# Cubesat_Potencia-rev1.net
KiCad netlist of a schematic drawn in EAGLE
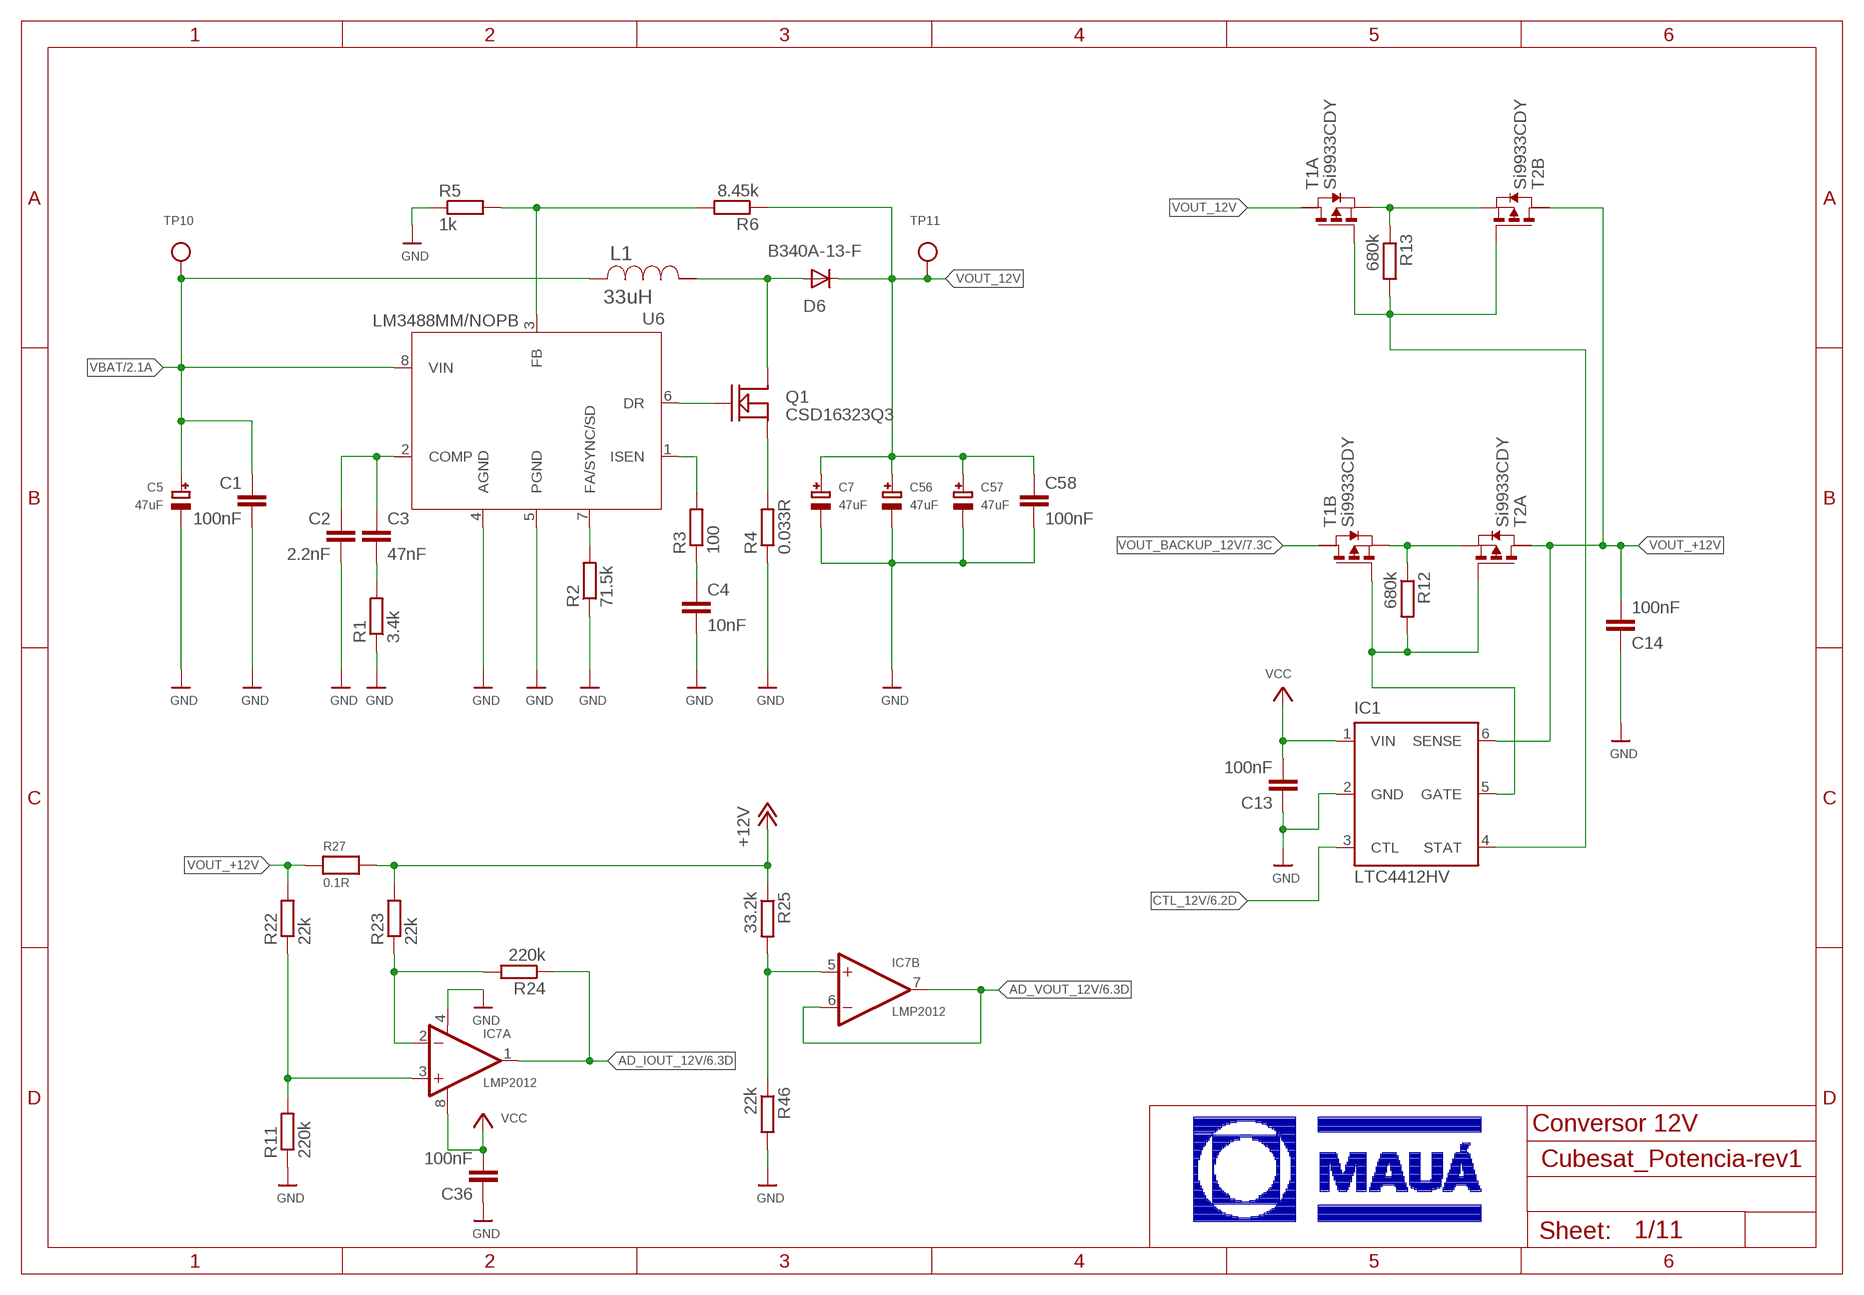
[diagram p0: schematic, sheet 1]
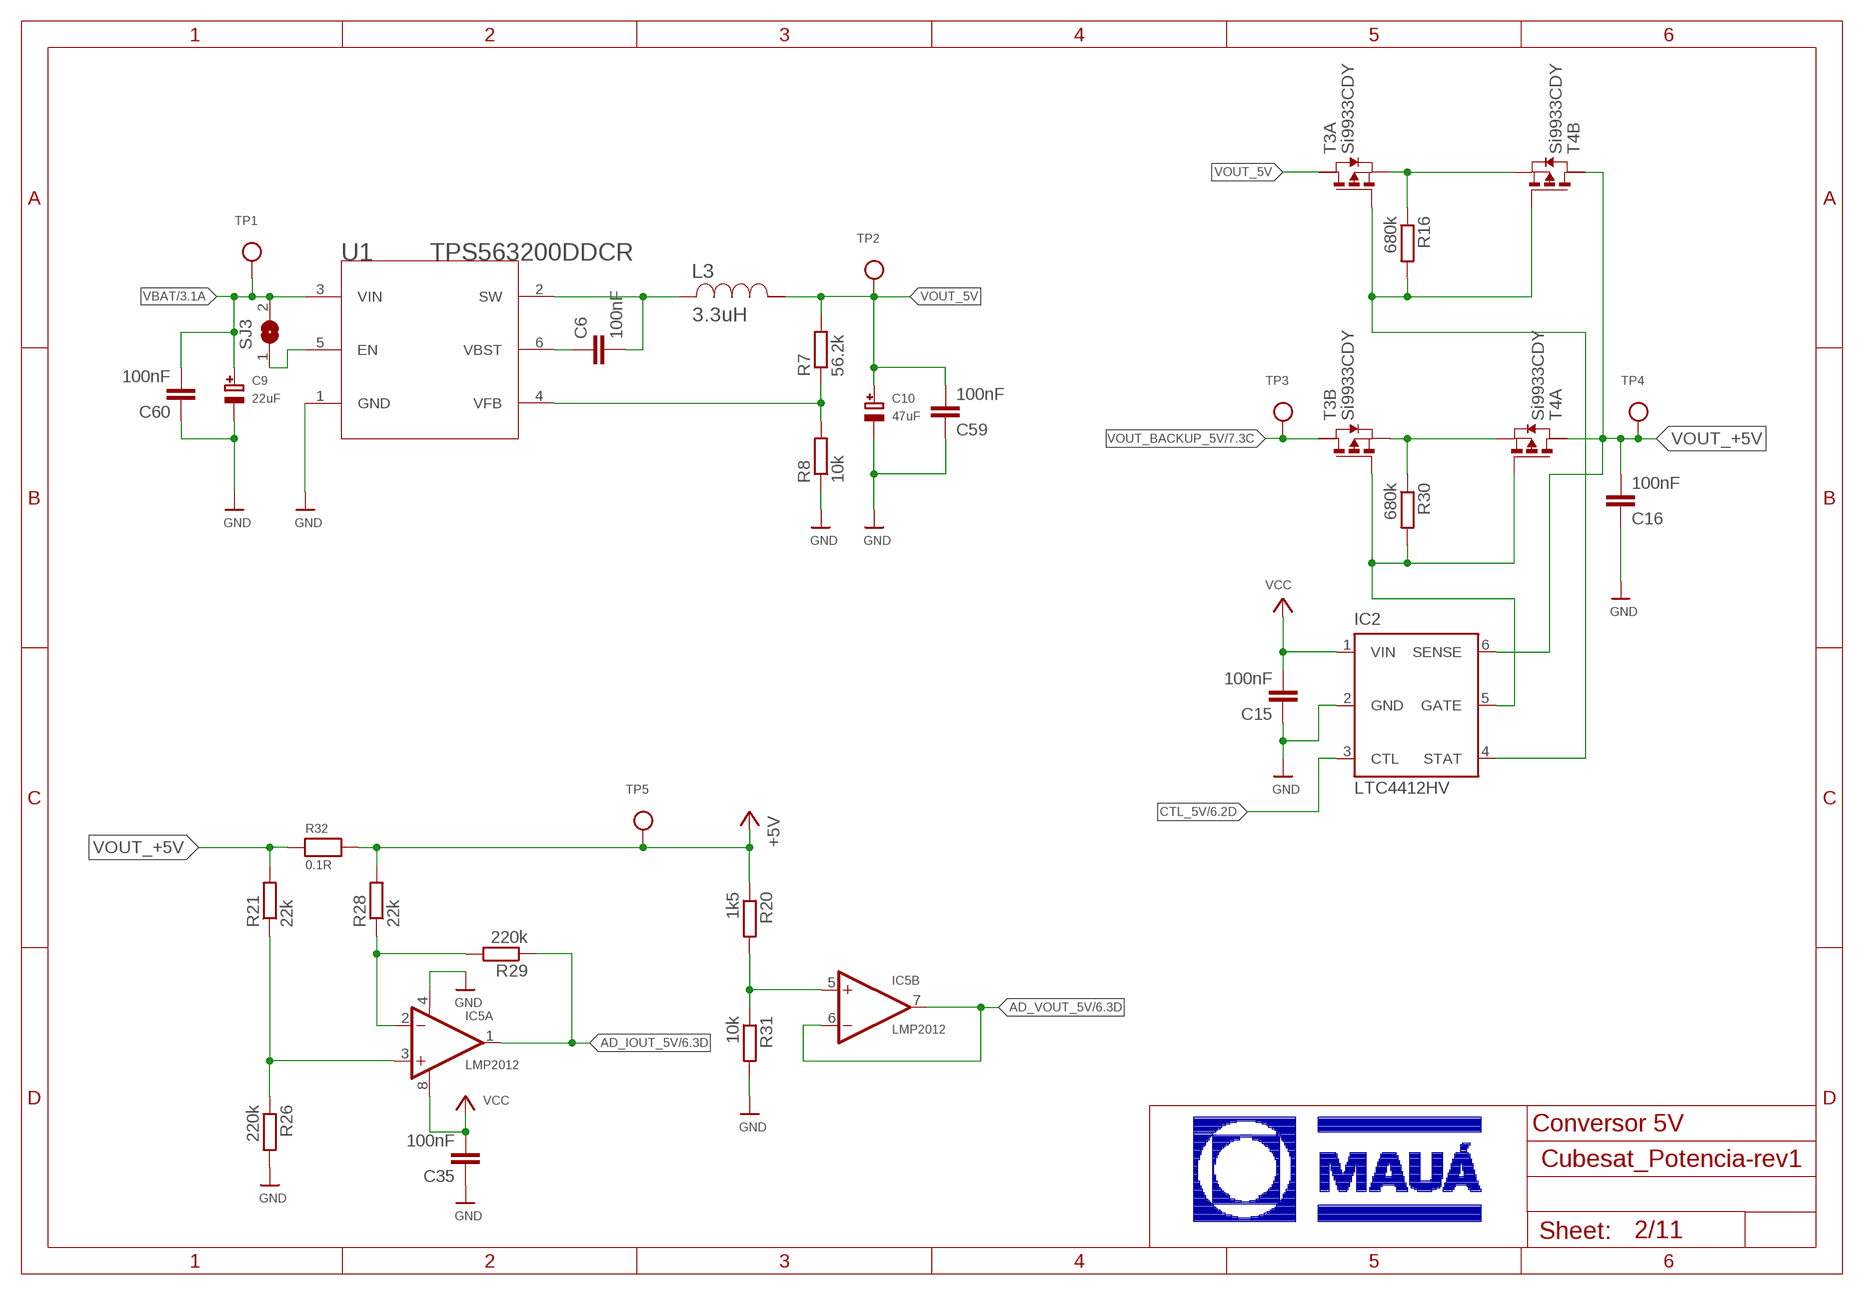
[diagram p1: schematic, sheet 2]
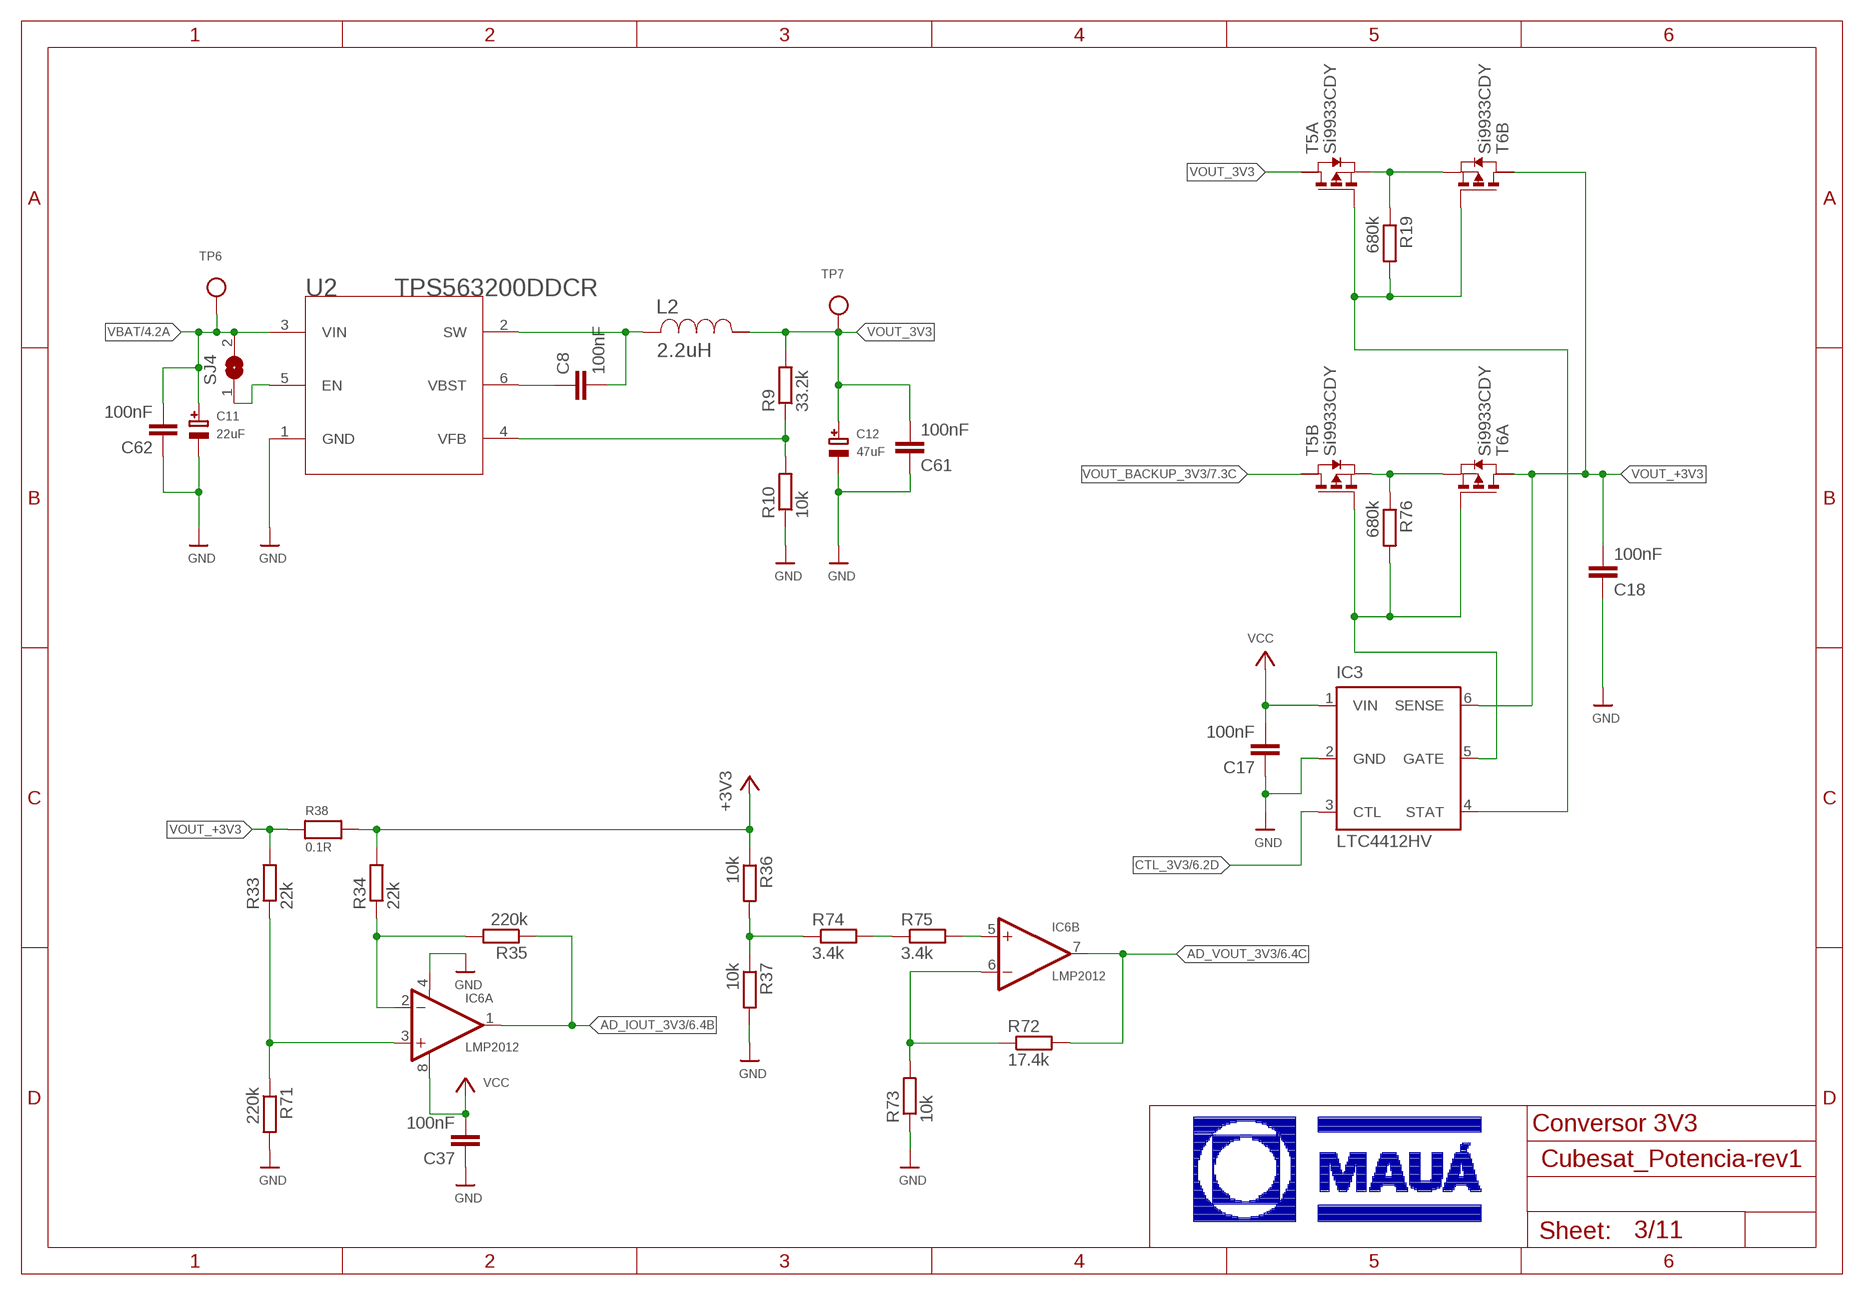
[diagram p2: schematic, sheet 3]
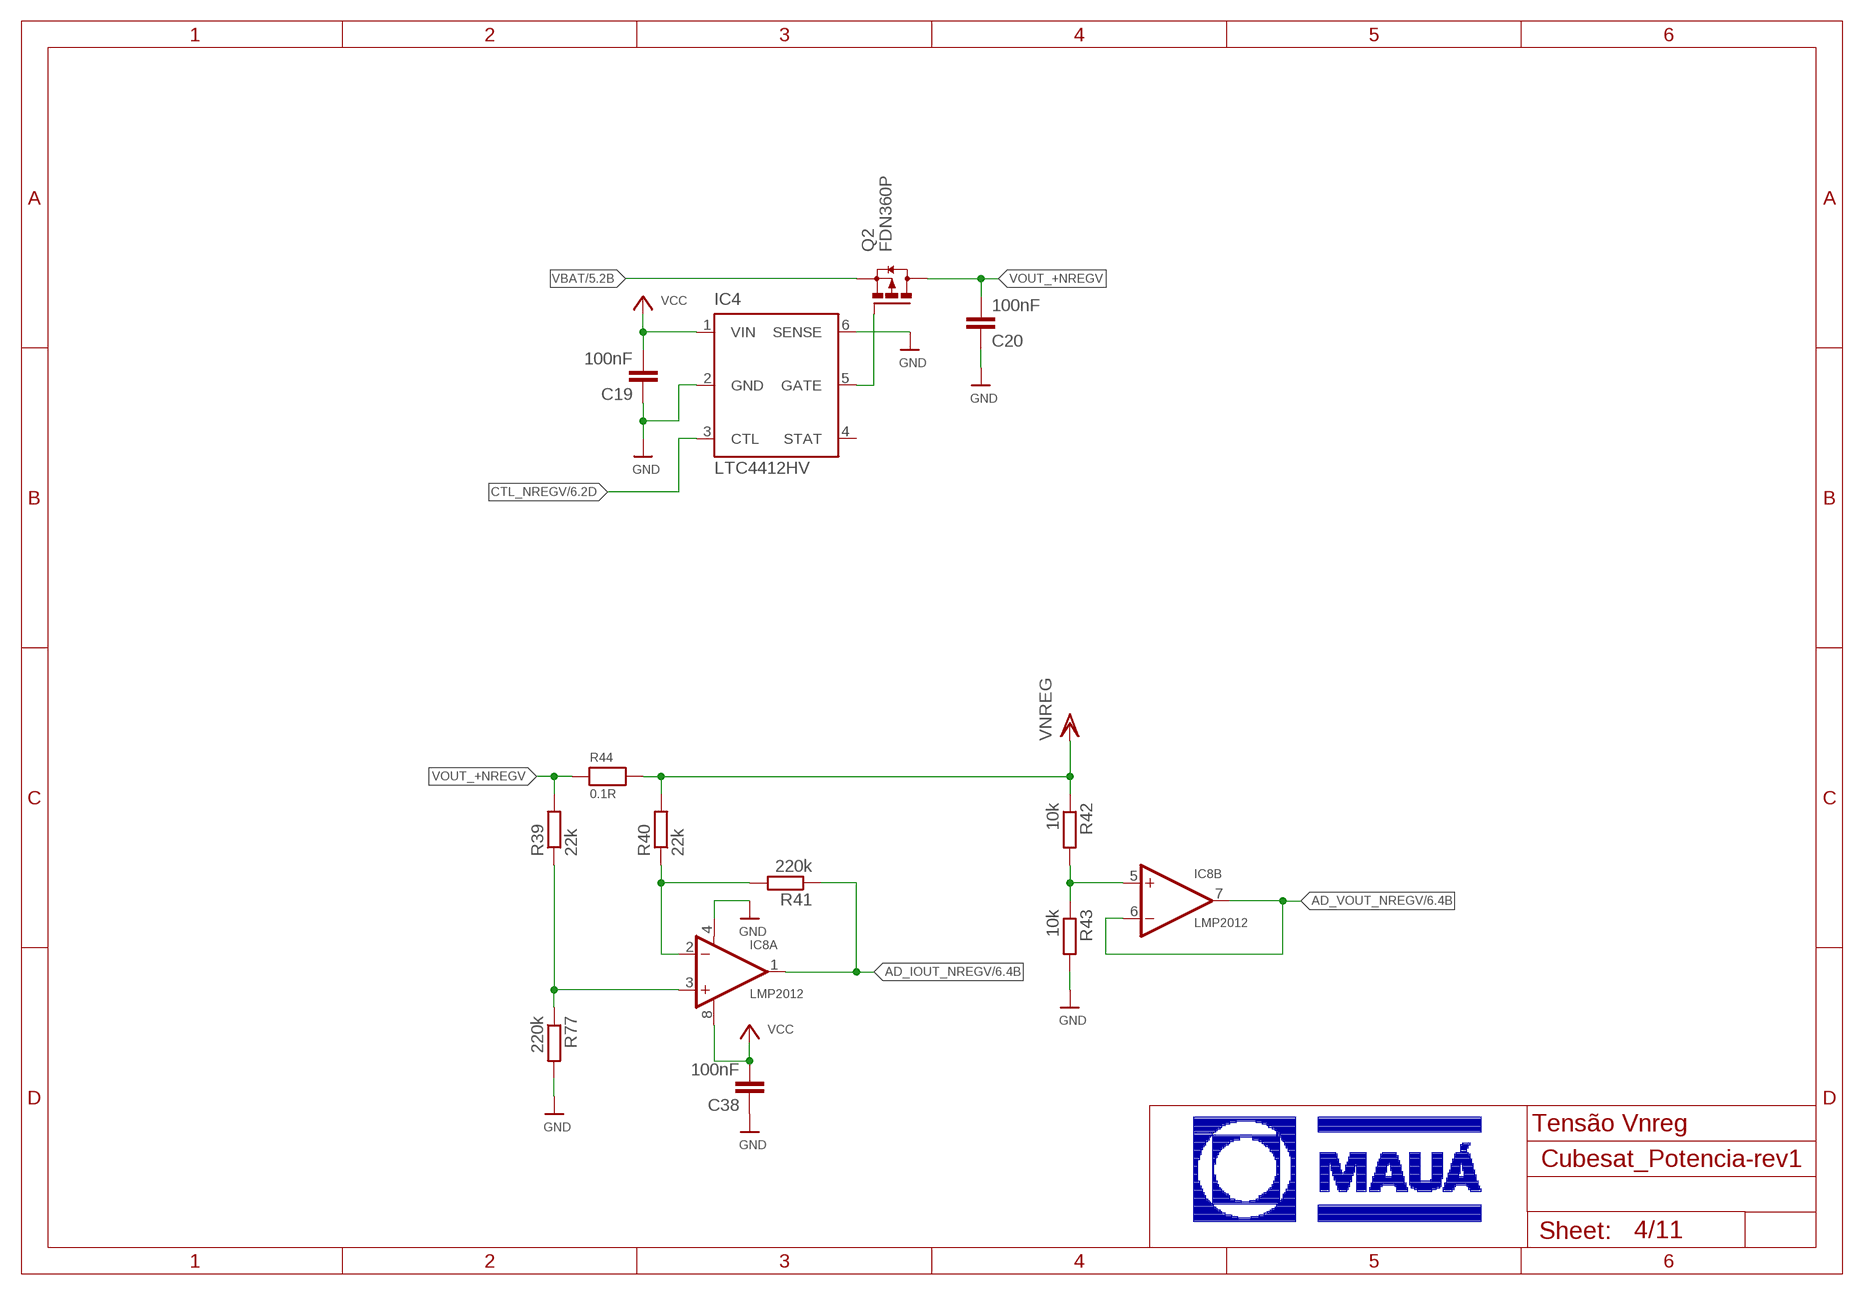
[diagram p3: schematic, sheet 4]
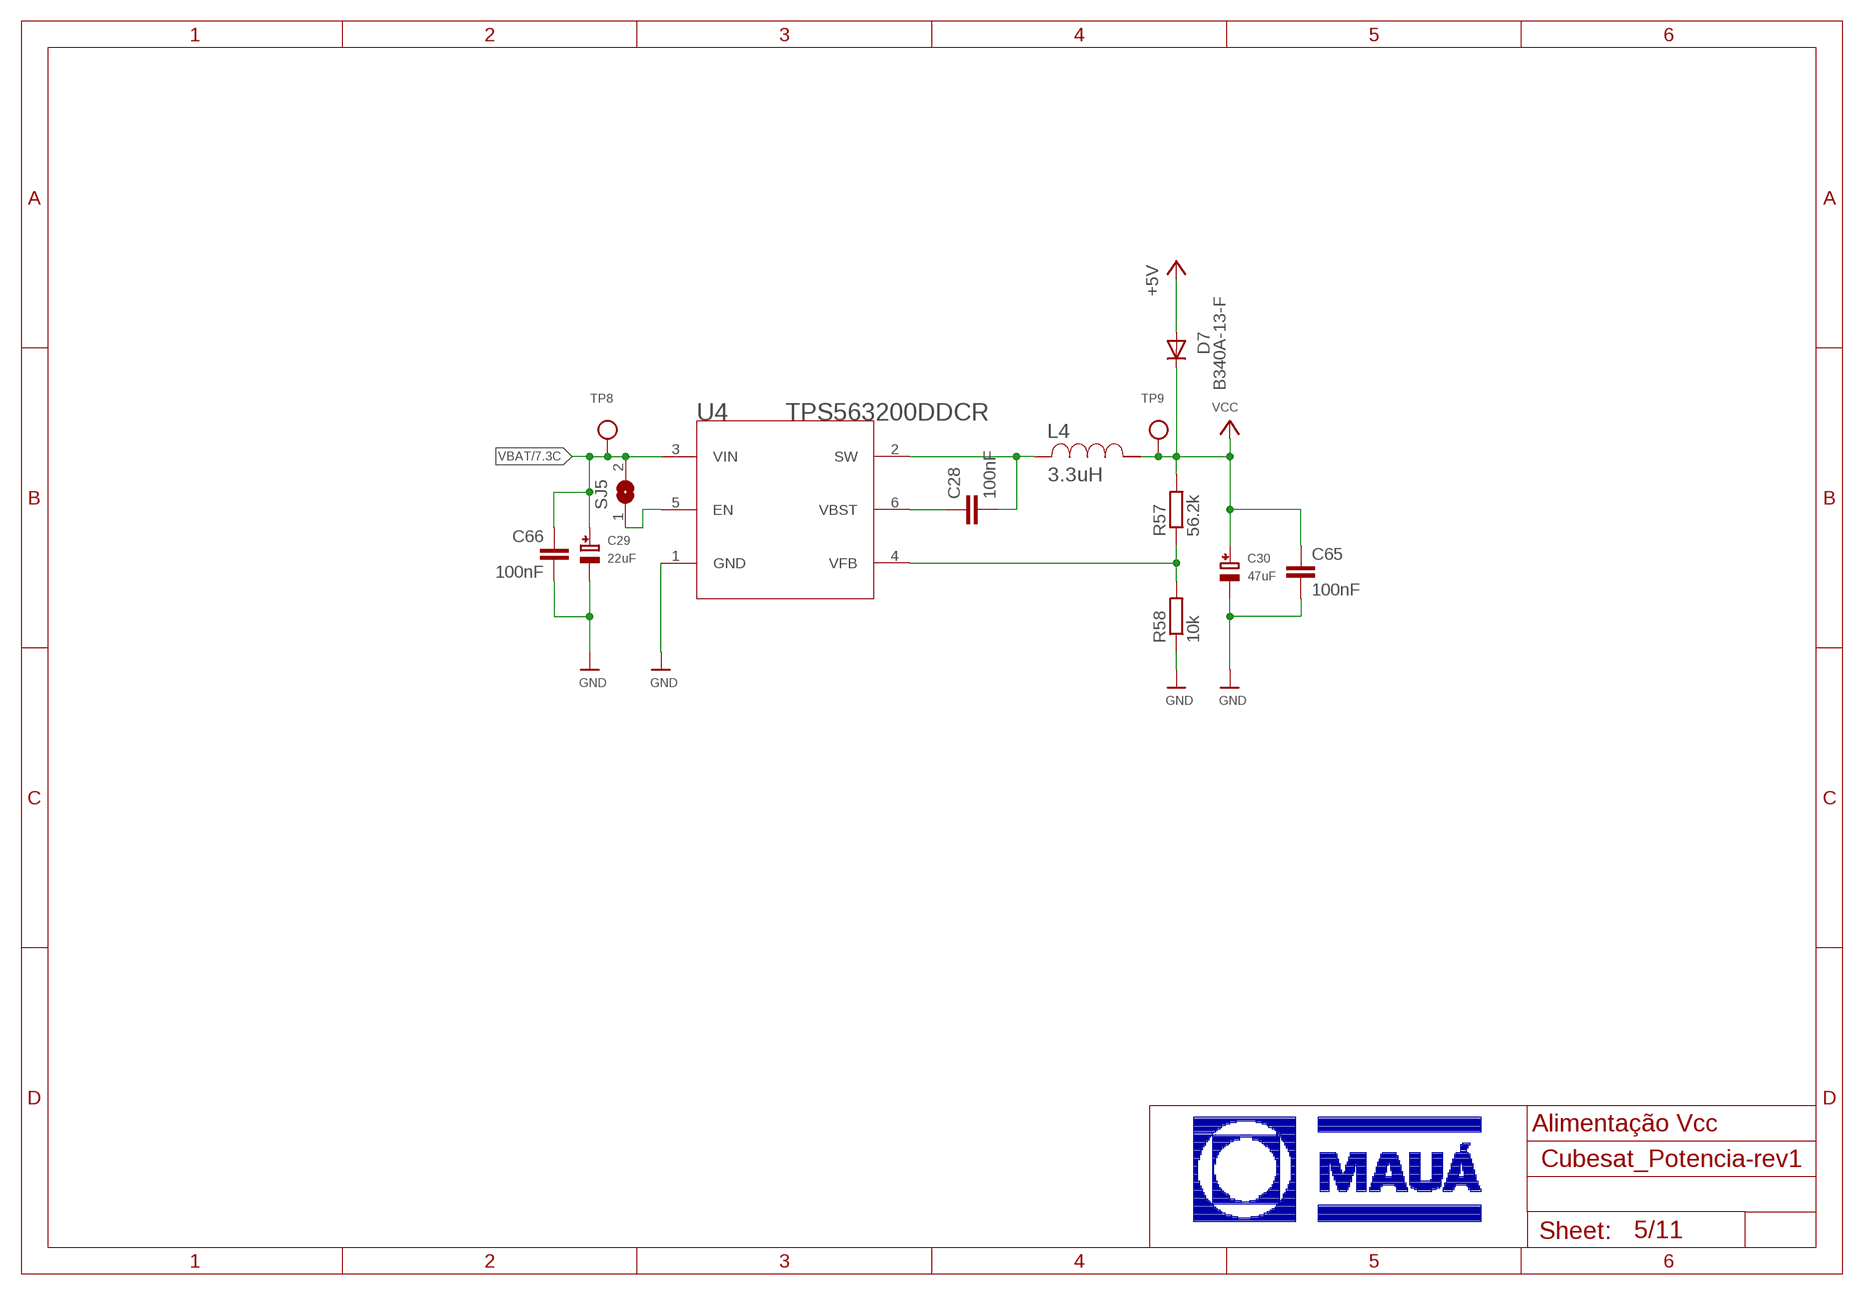
[diagram p4: schematic, sheet 5]
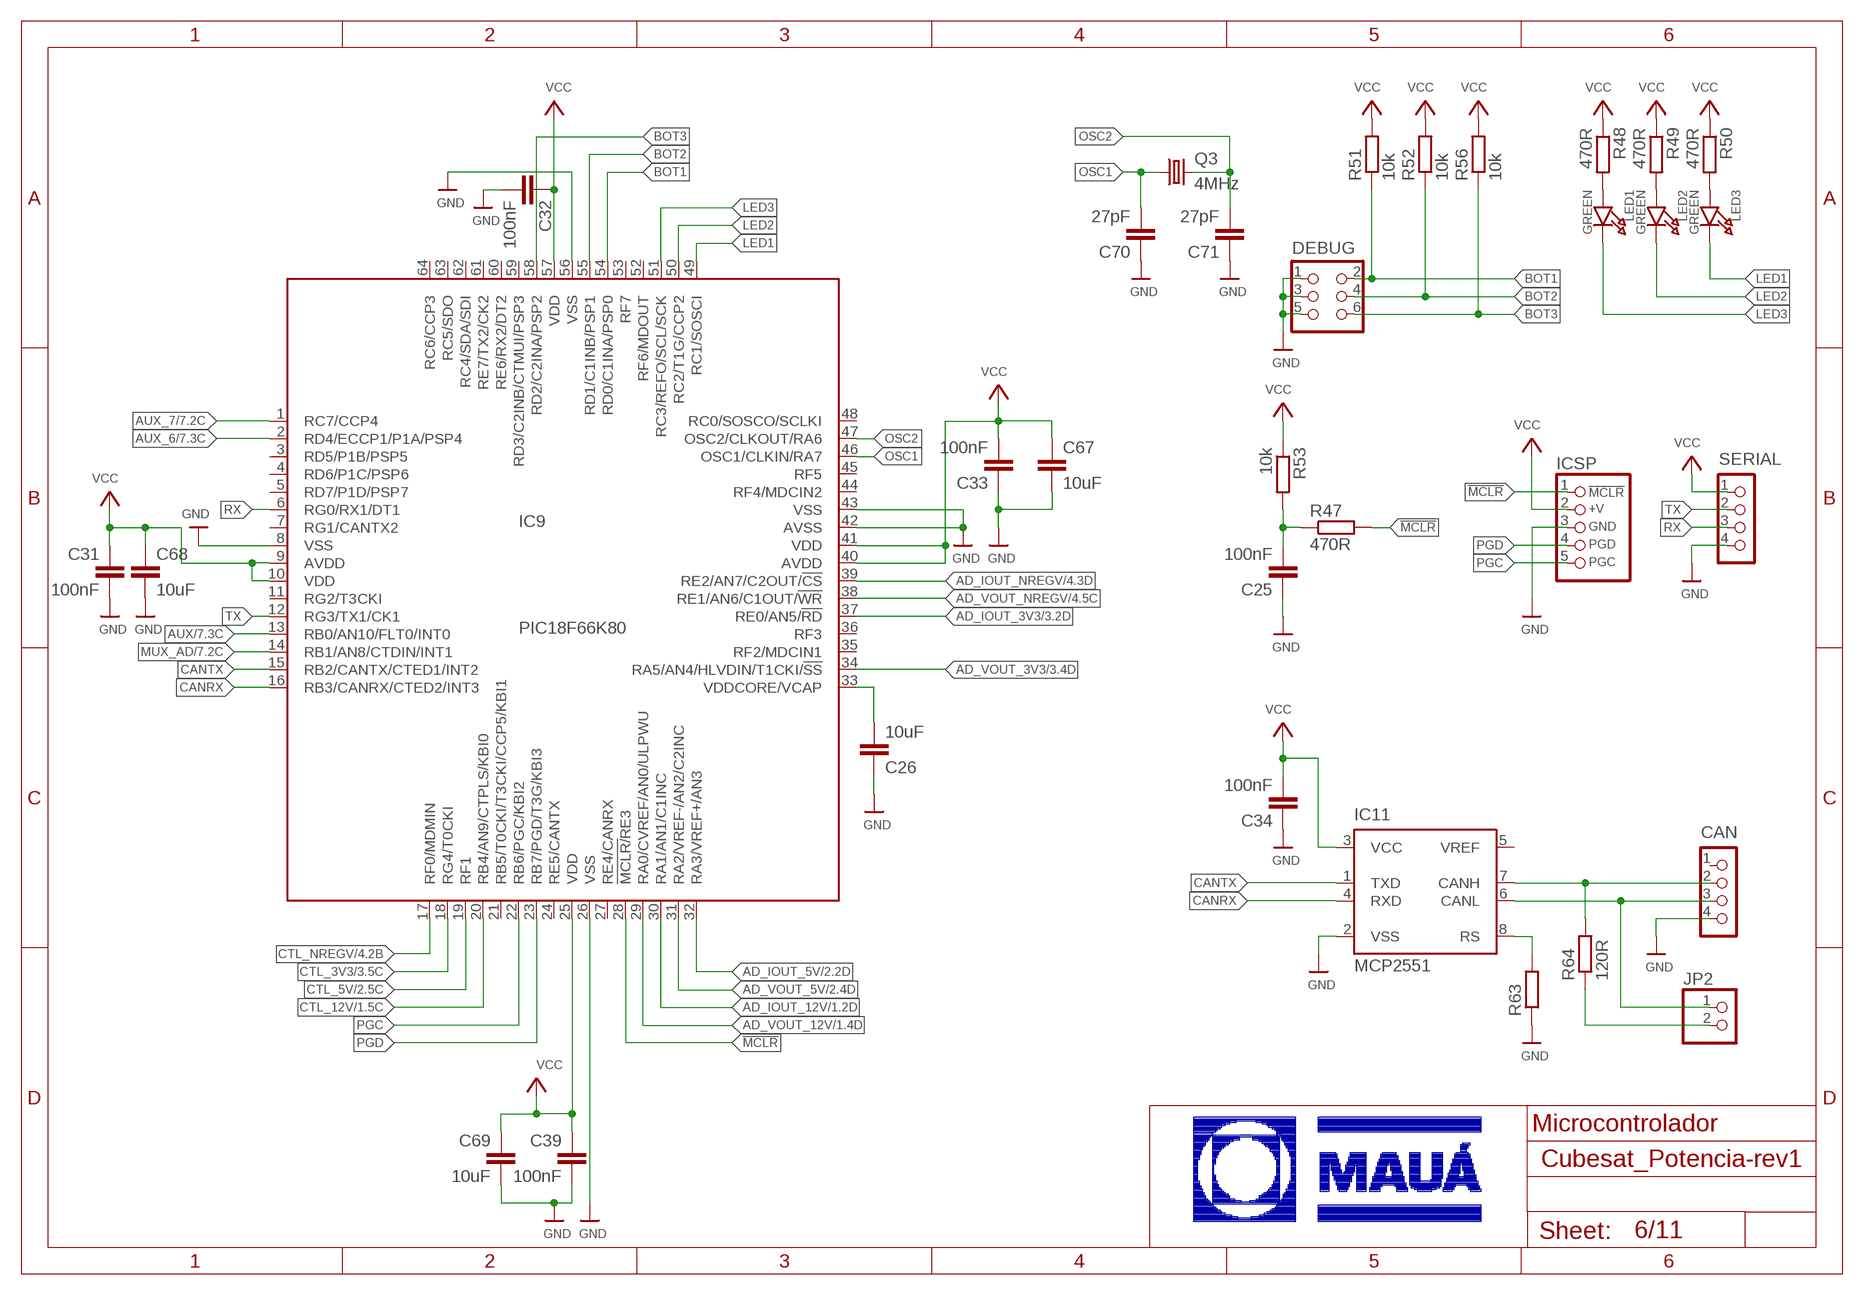
[diagram p5: schematic, sheet 6]
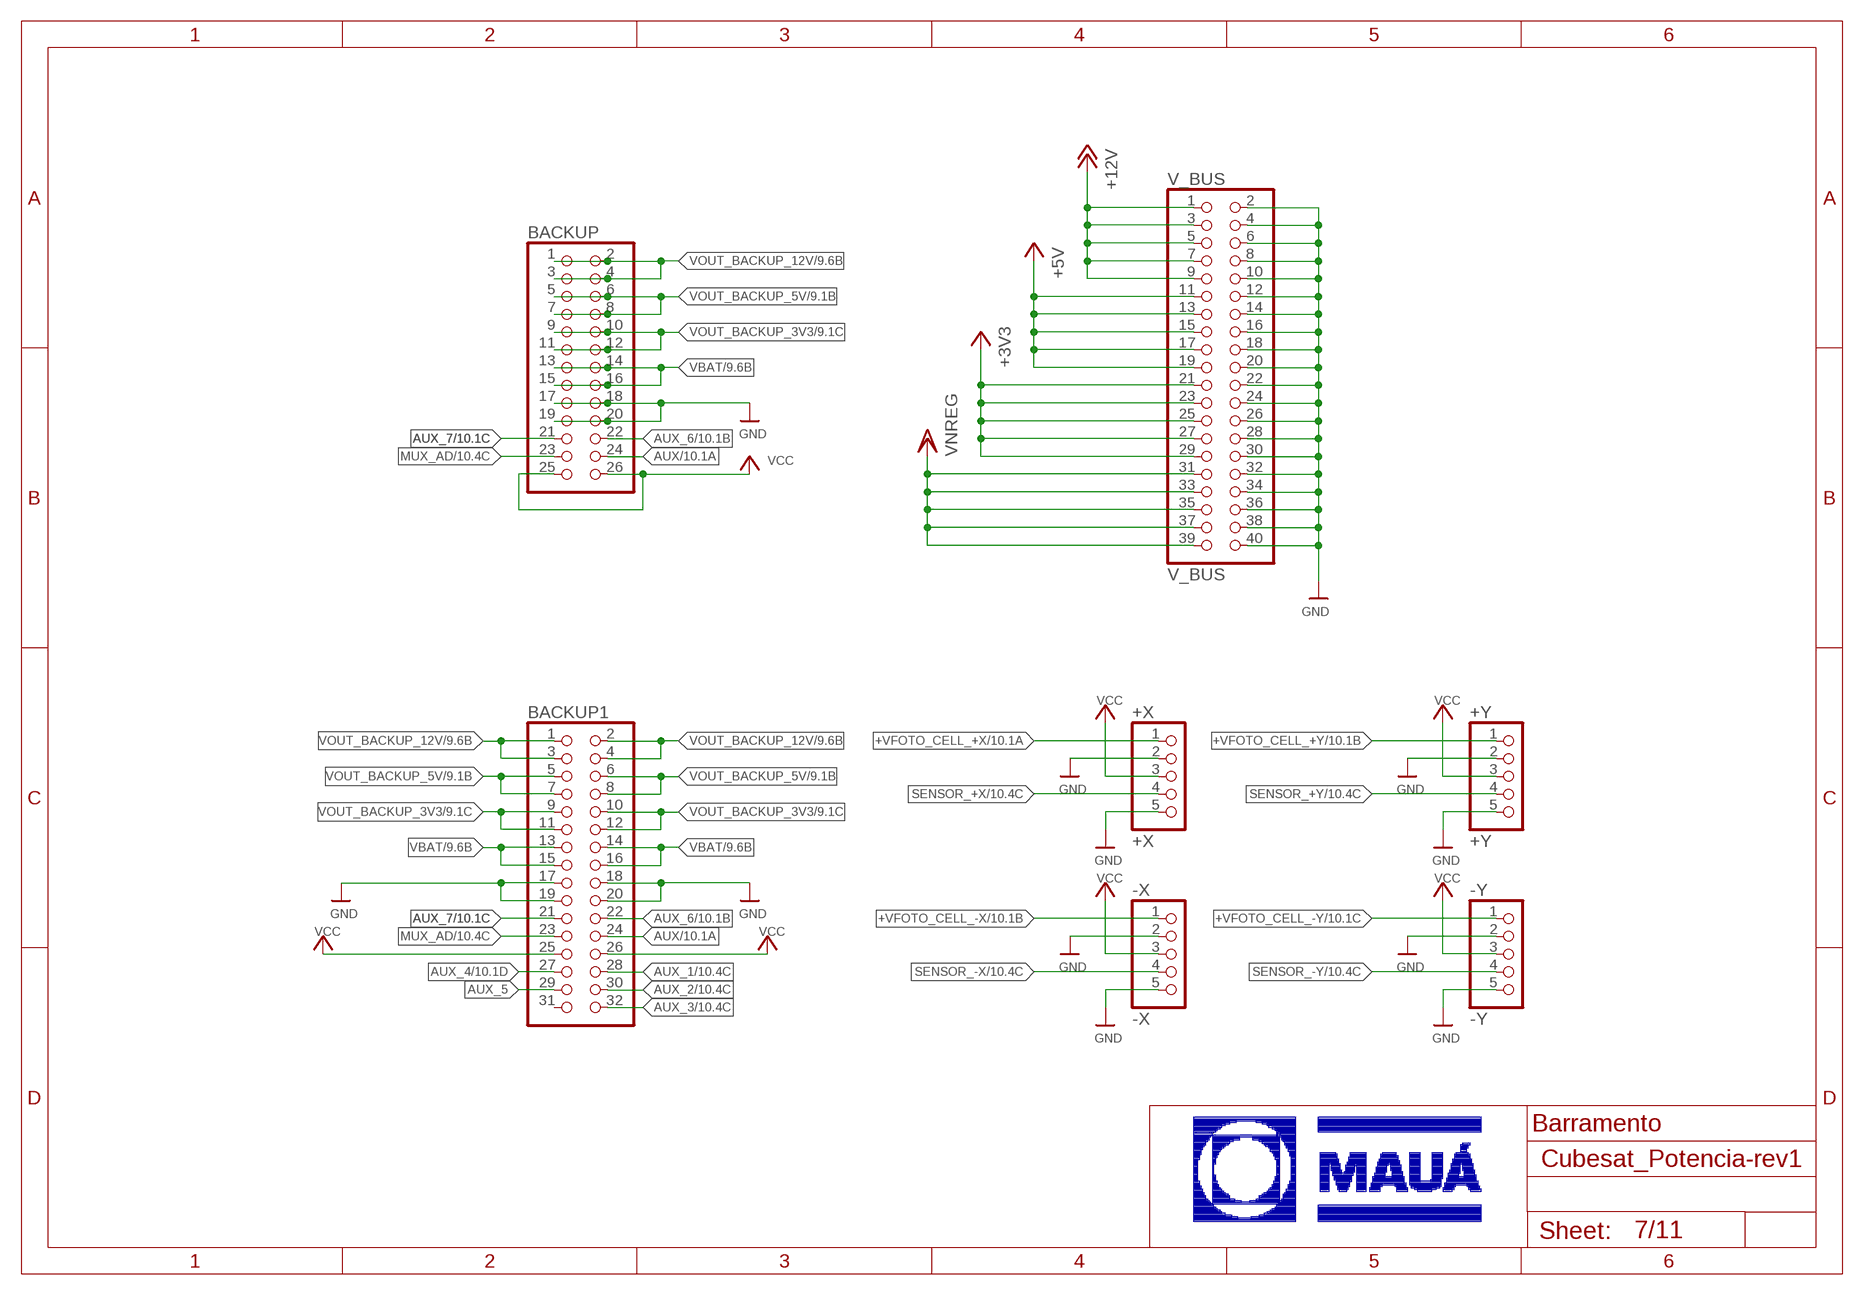
[diagram p6: schematic, sheet 7]
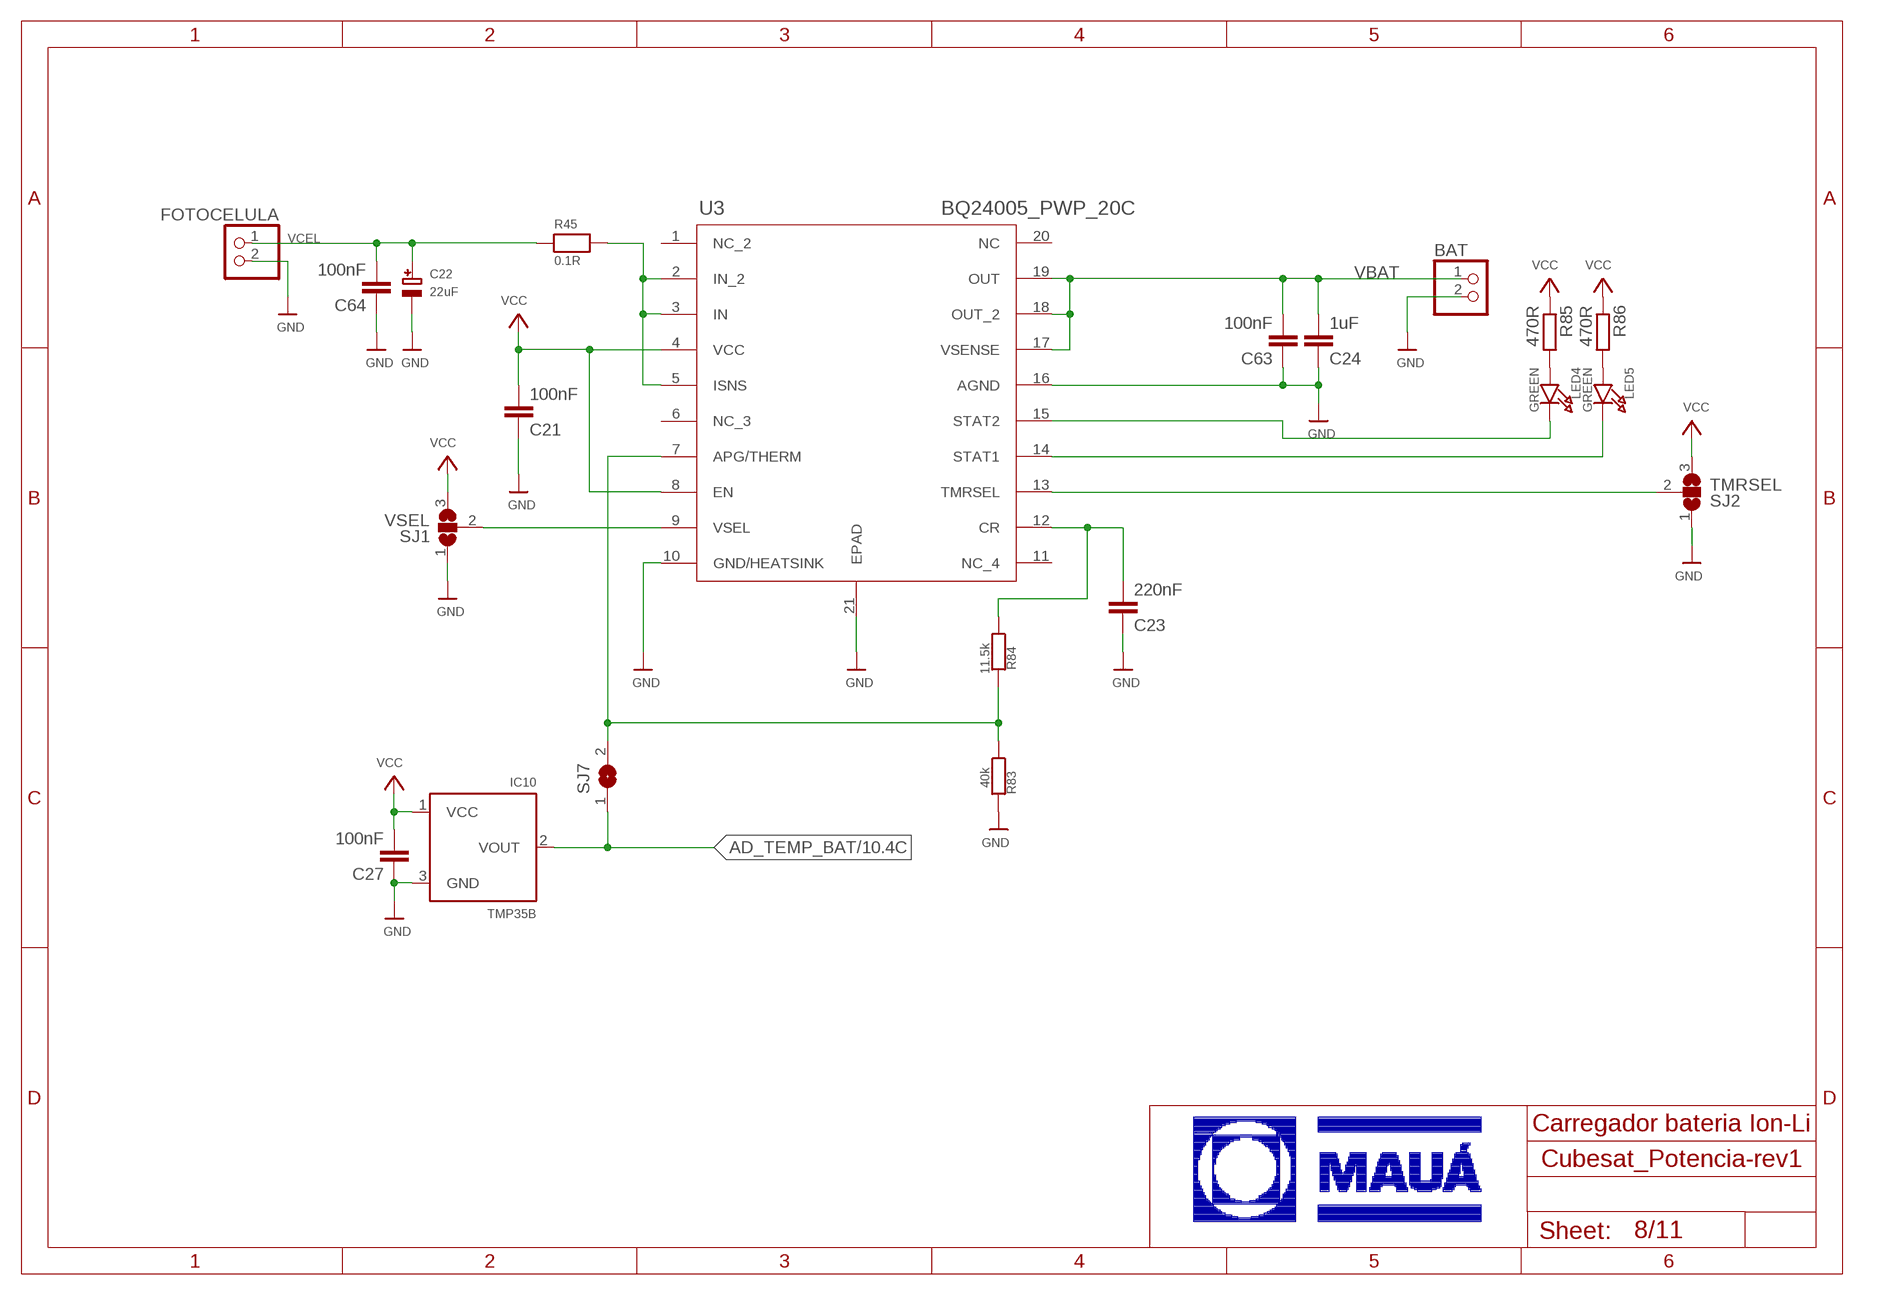
[diagram p7: schematic, sheet 8]
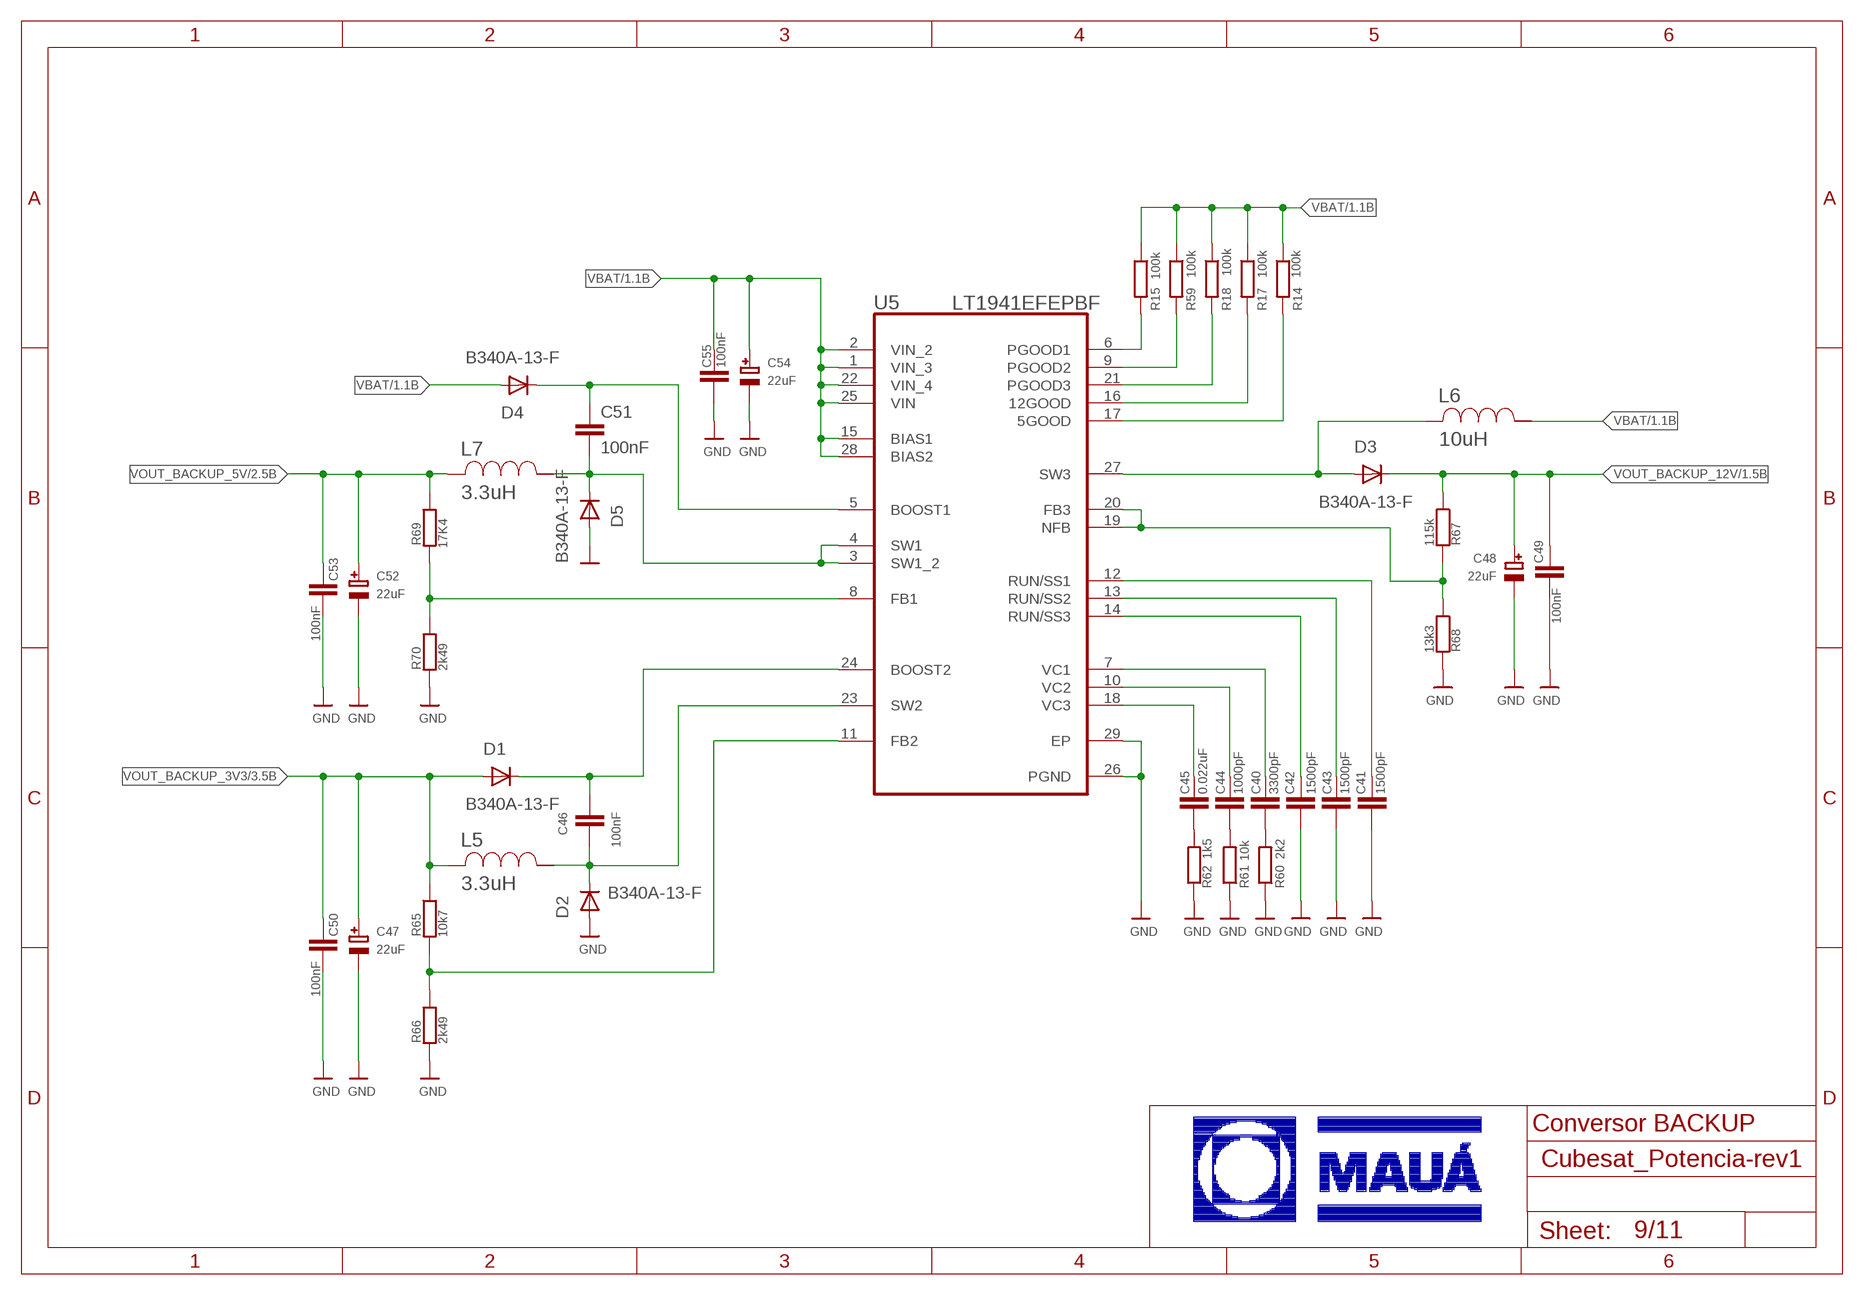
[diagram p8: schematic, sheet 9]
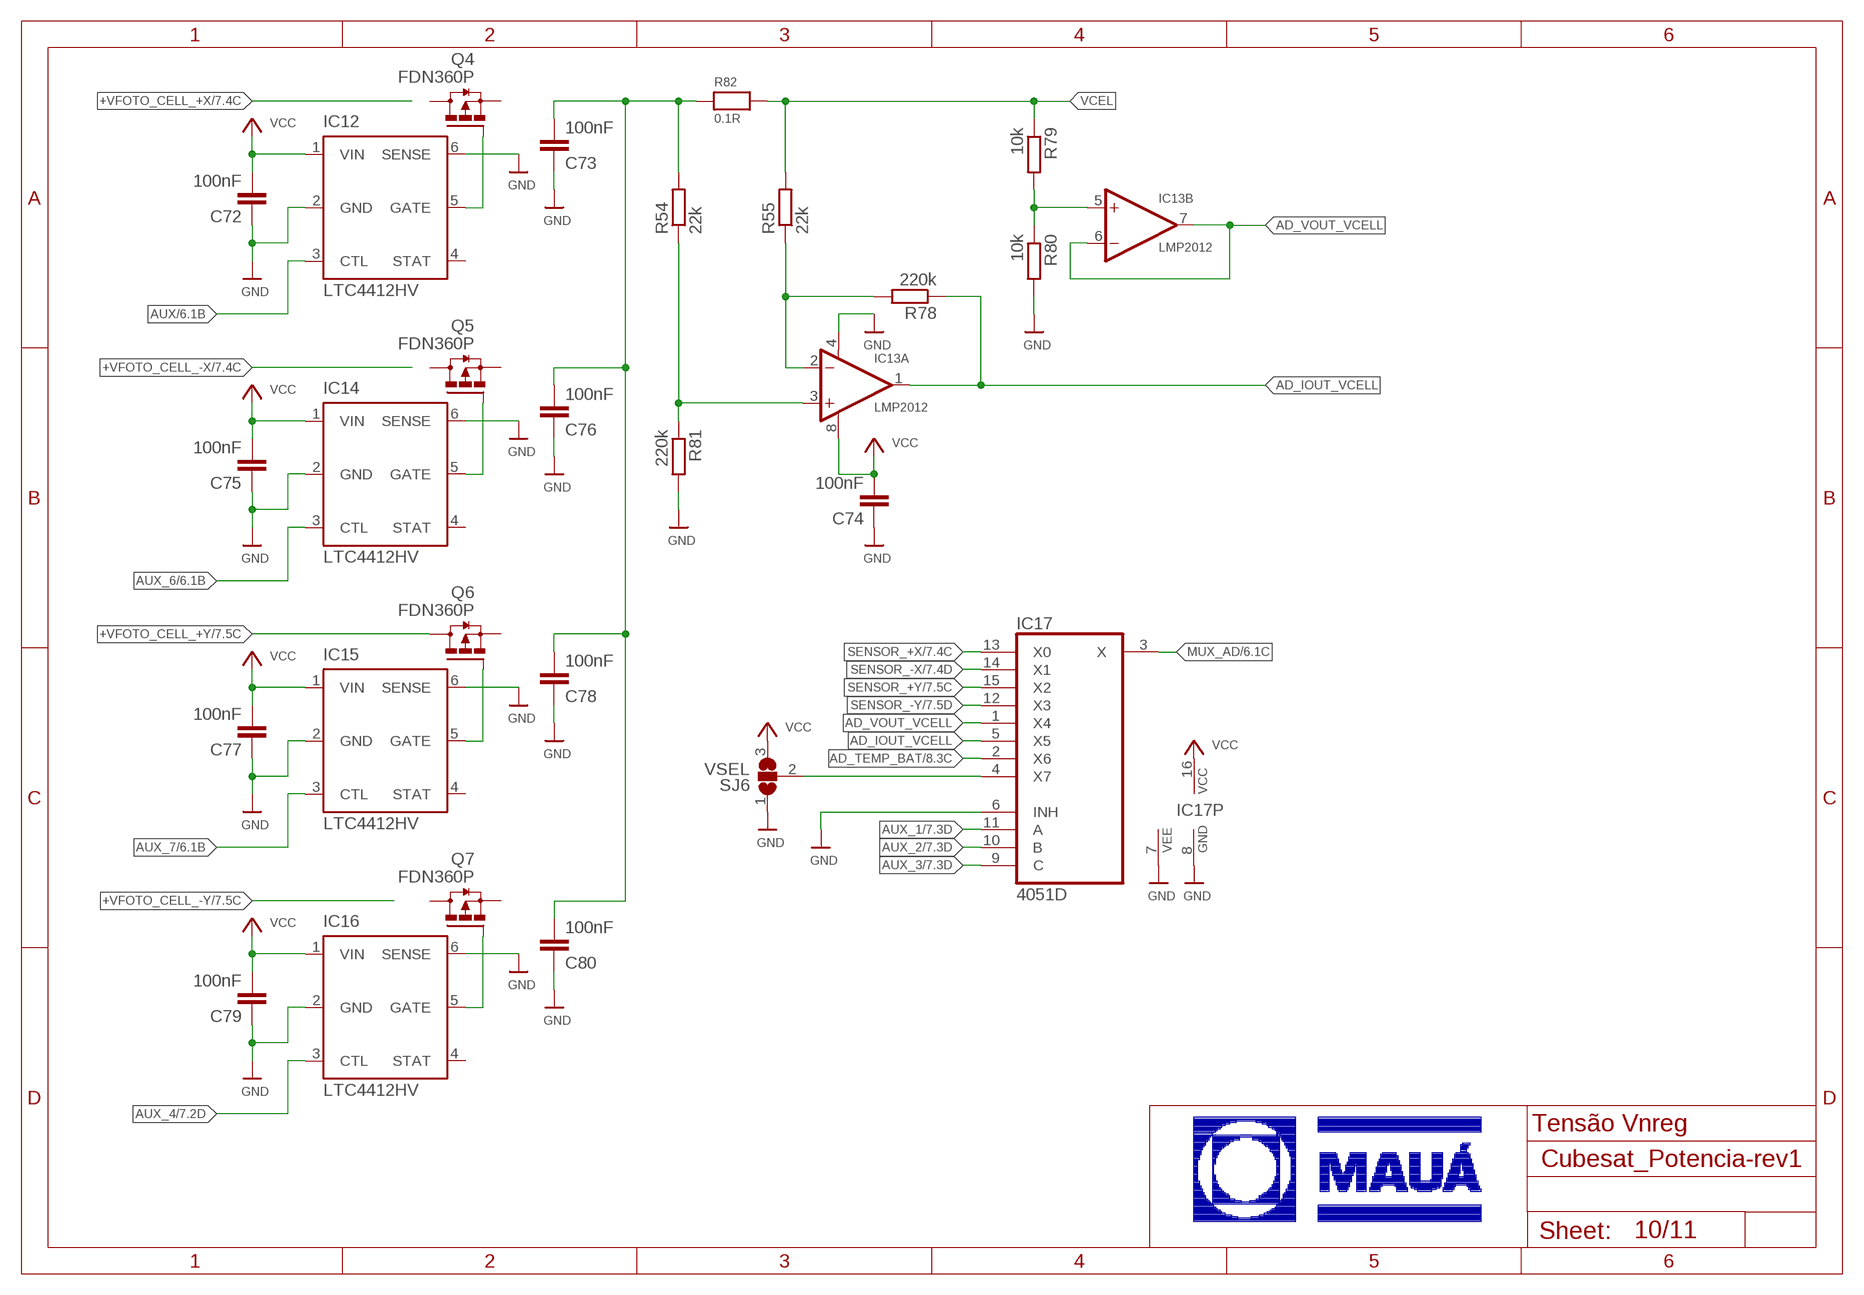
[diagram p9: schematic, sheet 10]
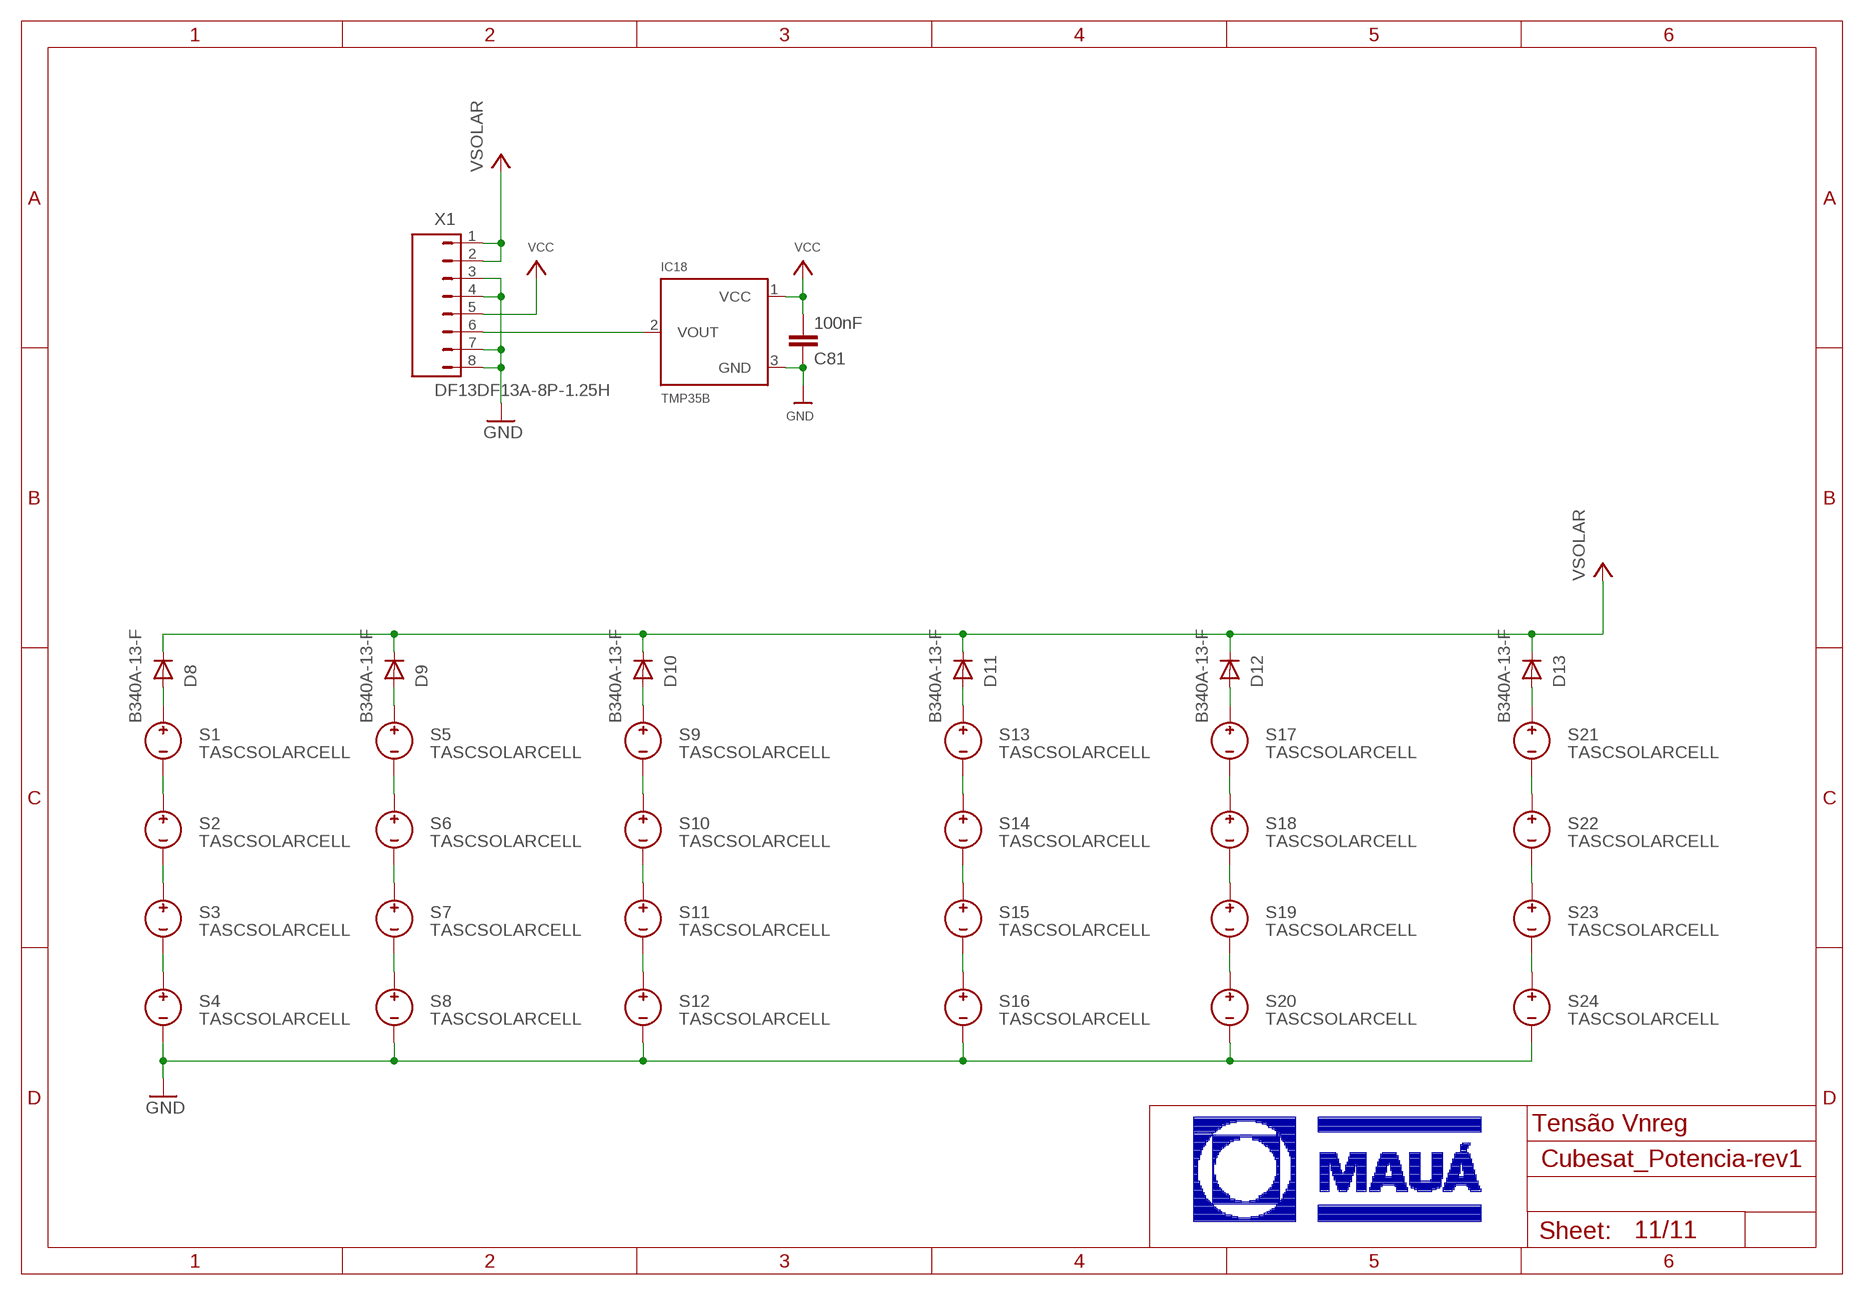
[diagram p10: schematic, sheet 11]

(export (version "E")
  (design (tool "Eeschema 10.0.6"))
  (components
    (comp (ref "BAT")
      (value "HEADER-1X2")
      (footprint "eagle-import:1X02_OVAL")
      (libsource (lib "eagle-import") (part "HEADER-1X2"))
    )
    (comp (ref "C21")
      (value "100nF")
      (footprint "eagle-import:C0805")
      (libsource (lib "eagle-import") (part "C-EUC0805"))
    )
    (comp (ref "C22")
      (value "22uF")
      (footprint "eagle-import:EIA6032-28_C-R")
      (libsource (lib "eagle-import") (part "CAP_TANTALUMC/6032_REFLOW"))
    )
    (comp (ref "C23")
      (value "220nF")
      (footprint "eagle-import:C0805")
      (libsource (lib "eagle-import") (part "C-EUC0805"))
    )
    (comp (ref "C24")
      (value "1uF")
      (footprint "eagle-import:C0805")
      (libsource (lib "eagle-import") (part "C-EUC0805"))
    )
    (comp (ref "C27")
      (value "100nF")
      (footprint "eagle-import:C0805")
      (libsource (lib "eagle-import") (part "C-EUC0805"))
    )
    (comp (ref "C63")
      (value "100nF")
      (footprint "eagle-import:C0805")
      (libsource (lib "eagle-import") (part "C-EUC0805"))
    )
    (comp (ref "C64")
      (value "100nF")
      (footprint "eagle-import:C0805")
      (libsource (lib "eagle-import") (part "C-EUC0805"))
    )
    (comp (ref "FOTOCELULA")
      (value "HEADER-1X2")
      (footprint "eagle-import:1X02_OVAL")
      (libsource (lib "eagle-import") (part "HEADER-1X2"))
    )
    (comp (ref "IC10")
      (value "TMP35B")
      (footprint "eagle-import:TO92-LINE")
      (libsource (lib "eagle-import") (part "TMP35B"))
    )
    (comp (ref "LED4")
      (value "GREEN")
      (footprint "eagle-import:CHIPLED_0805")
      (libsource (lib "eagle-import") (part "LED0805"))
    )
    (comp (ref "LED5")
      (value "GREEN")
      (footprint "eagle-import:CHIPLED_0805")
      (libsource (lib "eagle-import") (part "LED0805"))
    )
    (comp (ref "R45")
      (value "0.1R")
      (footprint "eagle-import:_2818")
      (libsource (lib "eagle-import") (part "RESISTOR2818"))
    )
    (comp (ref "R83")
      (value "40k")
      (footprint "eagle-import:M0805")
      (libsource (lib "eagle-import") (part "R-EU_M0805"))
    )
    (comp (ref "R84")
      (value "11.5k")
      (footprint "eagle-import:M0805")
      (libsource (lib "eagle-import") (part "R-EU_M0805"))
    )
    (comp (ref "R85")
      (value "470R")
      (footprint "eagle-import:M0805")
      (libsource (lib "eagle-import") (part "R-EU_M0805"))
    )
    (comp (ref "R86")
      (value "470R")
      (footprint "eagle-import:M0805")
      (libsource (lib "eagle-import") (part "R-EU_M0805"))
    )
    (comp (ref "SJ1")
      (value "VSEL")
      (footprint "eagle-import:SJ_2")
      (libsource (lib "eagle-import") (part "SJ2W"))
    )
    (comp (ref "SJ2")
      (value "TMRSEL")
      (footprint "eagle-import:SJ_2")
      (libsource (lib "eagle-import") (part "SJ2W"))
    )
    (comp (ref "SJ7")
      (value "SOLDERJUMPER")
      (footprint "eagle-import:SOLDERJUMPER_ARROW_NOPASTE")
      (libsource (lib "eagle-import") (part "SOLDERJUMPER"))
    )
    (comp (ref "U3")
      (value "BQ24005_PWP_20C")
      (footprint "eagle-import:PWP20_2P4X3P4-M")
      (libsource (lib "eagle-import") (part "BQ24005_PWP_20C"))
    )
    (comp (ref "C8")
      (value "100nF")
      (footprint "eagle-import:C0805")
      (libsource (lib "eagle-import") (part "C-EUC0805"))
    )
    (comp (ref "C11")
      (value "22uF")
      (footprint "eagle-import:EIA6032-28_C-R")
      (libsource (lib "eagle-import") (part "CAP_TANTALUMC/6032_REFLOW"))
    )
    (comp (ref "C12")
      (value "47uF")
      (footprint "eagle-import:EIA6032-28_C-R")
      (libsource (lib "eagle-import") (part "CAP_TANTALUMC/6032_REFLOW"))
    )
    (comp (ref "C17")
      (value "100nF")
      (footprint "eagle-import:C0805")
      (libsource (lib "eagle-import") (part "C-EUC0805"))
    )
    (comp (ref "C18")
      (value "100nF")
      (footprint "eagle-import:C0805")
      (libsource (lib "eagle-import") (part "C-EUC0805"))
    )
    (comp (ref "C37")
      (value "100nF")
      (footprint "eagle-import:C0805")
      (libsource (lib "eagle-import") (part "C-EUC0805"))
    )
    (comp (ref "C61")
      (value "100nF")
      (footprint "eagle-import:C0805")
      (libsource (lib "eagle-import") (part "C-EUC0805"))
    )
    (comp (ref "C62")
      (value "100nF")
      (footprint "eagle-import:C0805")
      (libsource (lib "eagle-import") (part "C-EUC0805"))
    )
    (comp (ref "IC3")
      (value "LTC4412HV")
      (footprint "eagle-import:TSOT23-6")
      (libsource (lib "eagle-import") (part "LTC4412HV"))
    )
    (comp (ref "IC6")
      (value "LMP2012")
      (footprint "eagle-import:MSOP08")
      (fields
        (field (name "MF") "TEXAS INSTRUMENTS")
        (field (name "MPN") "OPA2237EA/250")
        (field (name "MPN_1") "OPA2237EA/250")
        (field (name "OC_FARNELL") "1470365")
        (field (name "OC_NEWARK") "35C1853")
      )
      (libsource (lib "eagle-import") (part "OPA2237E"))
    )
    (comp (ref "L2")
      (value "2.2uH")
      (footprint "eagle-import:SRR6038")
      (fields (field (name "MANUFACTURER_PART_NUMBER") "SRR6038-3R3Y"))
      (libsource (lib "eagle-import") (part "SRR6038-3R3Y"))
    )
    (comp (ref "R9")
      (value "33.2k")
      (footprint "eagle-import:M0805")
      (libsource (lib "eagle-import") (part "R-EU_M0805"))
    )
    (comp (ref "R10")
      (value "10k")
      (footprint "eagle-import:M0805")
      (libsource (lib "eagle-import") (part "R-EU_M0805"))
    )
    (comp (ref "R19")
      (value "680k")
      (footprint "eagle-import:M0805")
      (libsource (lib "eagle-import") (part "R-EU_M0805"))
    )
    (comp (ref "R33")
      (value "22k")
      (footprint "eagle-import:M0805")
      (libsource (lib "eagle-import") (part "R-EU_M0805"))
    )
    (comp (ref "R34")
      (value "22k")
      (footprint "eagle-import:M0805")
      (libsource (lib "eagle-import") (part "R-EU_M0805"))
    )
    (comp (ref "R35")
      (value "220k")
      (footprint "eagle-import:M0805")
      (libsource (lib "eagle-import") (part "R-EU_M0805"))
    )
    (comp (ref "R36")
      (value "10k")
      (footprint "eagle-import:M0805")
      (libsource (lib "eagle-import") (part "R-EU_M0805"))
    )
    (comp (ref "R37")
      (value "10k")
      (footprint "eagle-import:M0805")
      (libsource (lib "eagle-import") (part "R-EU_M0805"))
    )
    (comp (ref "R38")
      (value "0.1R")
      (footprint "eagle-import:_2818")
      (libsource (lib "eagle-import") (part "RESISTOR2818"))
    )
    (comp (ref "R71")
      (value "220k")
      (footprint "eagle-import:M0805")
      (libsource (lib "eagle-import") (part "R-EU_M0805"))
    )
    (comp (ref "R72")
      (value "17.4k")
      (footprint "eagle-import:M0805")
      (libsource (lib "eagle-import") (part "R-EU_M0805"))
    )
    (comp (ref "R73")
      (value "10k")
      (footprint "eagle-import:M0805")
      (libsource (lib "eagle-import") (part "R-EU_M0805"))
    )
    (comp (ref "R74")
      (value "3.4k")
      (footprint "eagle-import:M0805")
      (libsource (lib "eagle-import") (part "R-EU_M0805"))
    )
    (comp (ref "R75")
      (value "3.4k")
      (footprint "eagle-import:M0805")
      (libsource (lib "eagle-import") (part "R-EU_M0805"))
    )
    (comp (ref "R76")
      (value "680k")
      (footprint "eagle-import:M0805")
      (libsource (lib "eagle-import") (part "R-EU_M0805"))
    )
    (comp (ref "SJ4")
      (value "SOLDERJUMPER")
      (footprint "eagle-import:SOLDERJUMPER_ARROW_NOPASTE")
      (libsource (lib "eagle-import") (part "SOLDERJUMPER"))
    )
    (comp (ref "T5")
      (value "Si9933CDY")
      (footprint "eagle-import:SO8")
      (libsource (lib "eagle-import") (part "PMOS2SO8"))
    )
    (comp (ref "T6")
      (value "Si9933CDY")
      (footprint "eagle-import:SO8")
      (libsource (lib "eagle-import") (part "PMOS2SO8"))
    )
    (comp (ref "TP6")
      (value "TESTPOINT0.1\"")
      (footprint "eagle-import:1X01_ROUND")
      (libsource (lib "eagle-import") (part "TESTPOINT0.1{dblquote}"))
    )
    (comp (ref "TP7")
      (value "TESTPOINT0.1\"")
      (footprint "eagle-import:1X01_ROUND")
      (fields (field (name "BOM") "EXCLUDE"))
      (libsource (lib "eagle-import") (part "TESTPOINT0.1{dblquote}"))
    )
    (comp (ref "U2")
      (value "TPS563200DDCR")
      (footprint "eagle-import:DDC0006A")
      (fields
        (field (name "MANUFACTURER") "Texas Instruments")
        (field (name "PARTNUMBER") "TPS563200DDC")
        (field (name "APPROVEDBY") "Not shown in title block")
        (field (name "AUTHOR") "Not shown in title block")
        (field (name "CHECKEDBY") "Not shown in title block")
        (field (name "ENGINEER") "Not shown in title block")
        (field (name "MODIFIEDDATE") "Not shown in title block")
        (field (name "PUBLISHER") "Texas Instruments")
        (field (name "SYMBOLCREATOR") "a0411947")
      )
      (libsource (lib "eagle-import") (part "TPS563200DDCR"))
    )
    (comp (ref "+X")
      (value "+X")
      (footprint "eagle-import:1X05")
      (libsource (lib "eagle-import") (part "PINHD-1X5"))
    )
    (comp (ref "+Y")
      (value "+Y")
      (footprint "eagle-import:1X05")
      (libsource (lib "eagle-import") (part "PINHD-1X5"))
    )
    (comp (ref "-X")
      (value "-X")
      (footprint "eagle-import:1X05")
      (libsource (lib "eagle-import") (part "PINHD-1X5"))
    )
    (comp (ref "-Y")
      (value "-Y")
      (footprint "eagle-import:1X05")
      (libsource (lib "eagle-import") (part "PINHD-1X5"))
    )
    (comp (ref "BACKUP")
      (value "HEADER-2X13")
      (footprint "eagle-import:2X13")
      (libsource (lib "eagle-import") (part "HEADER-2X13"))
    )
    (comp (ref "BACKUP1")
      (value "PINHD-2X16")
      (footprint "eagle-import:2X16")
      (libsource (lib "eagle-import") (part "PINHD-2X16"))
    )
    (comp (ref "V_BUS")
      (value "V_BUS")
      (footprint "eagle-import:2X20")
      (libsource (lib "eagle-import") (part "PINHD-2X20"))
    )
    (comp (ref "C40")
      (value "3300pF")
      (footprint "eagle-import:C0805")
      (libsource (lib "eagle-import") (part "C-EUC0805"))
    )
    (comp (ref "C41")
      (value "1500pF")
      (footprint "eagle-import:C0805")
      (libsource (lib "eagle-import") (part "C-EUC0805"))
    )
    (comp (ref "C42")
      (value "1500pF")
      (footprint "eagle-import:C0805")
      (libsource (lib "eagle-import") (part "C-EUC0805"))
    )
    (comp (ref "C43")
      (value "1500pF")
      (footprint "eagle-import:C0805")
      (libsource (lib "eagle-import") (part "C-EUC0805"))
    )
    (comp (ref "C44")
      (value "1000pF")
      (footprint "eagle-import:C0805")
      (libsource (lib "eagle-import") (part "C-EUC0805"))
    )
    (comp (ref "C45")
      (value "0.022uF")
      (footprint "eagle-import:C0805")
      (libsource (lib "eagle-import") (part "C-EUC0805"))
    )
    (comp (ref "C46")
      (value "100nF")
      (footprint "eagle-import:C0805")
      (libsource (lib "eagle-import") (part "C-EUC0805"))
    )
    (comp (ref "C47")
      (value "22uF")
      (footprint "eagle-import:EIA6032-28_C-R")
      (libsource (lib "eagle-import") (part "CAP_TANTALUMC/6032_REFLOW"))
    )
    (comp (ref "C48")
      (value "22uF")
      (footprint "eagle-import:EIA6032-28_C-R")
      (libsource (lib "eagle-import") (part "CAP_TANTALUMC/6032_REFLOW"))
    )
    (comp (ref "C49")
      (value "100nF")
      (footprint "eagle-import:C0805")
      (libsource (lib "eagle-import") (part "C-EUC0805"))
    )
    (comp (ref "C50")
      (value "100nF")
      (footprint "eagle-import:C0805")
      (libsource (lib "eagle-import") (part "C-EUC0805"))
    )
    (comp (ref "C51")
      (value "100nF")
      (footprint "eagle-import:C1210")
      (libsource (lib "eagle-import") (part "C-EUC1210"))
    )
    (comp (ref "C52")
      (value "22uF")
      (footprint "eagle-import:EIA6032-28_C-R")
      (libsource (lib "eagle-import") (part "CAP_TANTALUMC/6032_REFLOW"))
    )
    (comp (ref "C53")
      (value "100nF")
      (footprint "eagle-import:C0805")
      (libsource (lib "eagle-import") (part "C-EUC0805"))
    )
    (comp (ref "C54")
      (value "22uF")
      (footprint "eagle-import:EIA6032-28_C-R")
      (libsource (lib "eagle-import") (part "CAP_TANTALUMC/6032_REFLOW"))
    )
    (comp (ref "C55")
      (value "100nF")
      (footprint "eagle-import:C0805")
      (libsource (lib "eagle-import") (part "C-EUC0805"))
    )
    (comp (ref "D1")
      (value "B340A-13-F")
      (footprint "eagle-import:DO214AC")
      (libsource (lib "eagle-import") (part "DIODE-DO214AC"))
    )
    (comp (ref "D2")
      (value "B340A-13-F")
      (footprint "eagle-import:DO214AC")
      (libsource (lib "eagle-import") (part "DIODE-DO214AC"))
    )
    (comp (ref "D3")
      (value "B340A-13-F")
      (footprint "eagle-import:DO214AC")
      (libsource (lib "eagle-import") (part "DIODE-DO214AC"))
    )
    (comp (ref "D4")
      (value "B340A-13-F")
      (footprint "eagle-import:DO214AC")
      (libsource (lib "eagle-import") (part "DIODE-DO214AC"))
    )
    (comp (ref "D5")
      (value "B340A-13-F")
      (footprint "eagle-import:DO214AC")
      (libsource (lib "eagle-import") (part "DIODE-DO214AC"))
    )
    (comp (ref "L5")
      (value "3.3uH")
      (footprint "eagle-import:SRR6038")
      (fields (field (name "MANUFACTURER_PART_NUMBER") "SRR6038-3R3Y"))
      (libsource (lib "eagle-import") (part "SRR6038-3R3Y"))
    )
    (comp (ref "L6")
      (value "10uH")
      (footprint "eagle-import:SRR6038")
      (fields (field (name "MANUFACTURER_PART_NUMBER") "SRR6038-3R3Y"))
      (libsource (lib "eagle-import") (part "SRR6038-3R3Y"))
    )
    (comp (ref "L7")
      (value "3.3uH")
      (footprint "eagle-import:SRR6038")
      (fields (field (name "MANUFACTURER_PART_NUMBER") "SRR6038-3R3Y"))
      (libsource (lib "eagle-import") (part "SRR6038-3R3Y"))
    )
    (comp (ref "R14")
      (value "100k")
      (footprint "eagle-import:M0805")
      (libsource (lib "eagle-import") (part "R-EU_M0805"))
    )
    (comp (ref "R15")
      (value "100k")
      (footprint "eagle-import:M0805")
      (libsource (lib "eagle-import") (part "R-EU_M0805"))
    )
    (comp (ref "R17")
      (value "100k")
      (footprint "eagle-import:M0805")
      (libsource (lib "eagle-import") (part "R-EU_M0805"))
    )
    (comp (ref "R18")
      (value "100k")
      (footprint "eagle-import:M0805")
      (libsource (lib "eagle-import") (part "R-EU_M0805"))
    )
    (comp (ref "R59")
      (value "100k")
      (footprint "eagle-import:M0805")
      (libsource (lib "eagle-import") (part "R-EU_M0805"))
    )
    (comp (ref "R60")
      (value "2k2")
      (footprint "eagle-import:M0805")
      (libsource (lib "eagle-import") (part "R-EU_M0805"))
    )
    (comp (ref "R61")
      (value "10k")
      (footprint "eagle-import:M0805")
      (libsource (lib "eagle-import") (part "R-EU_M0805"))
    )
    (comp (ref "R62")
      (value "1k5")
      (footprint "eagle-import:M0805")
      (libsource (lib "eagle-import") (part "R-EU_M0805"))
    )
    (comp (ref "R65")
      (value "10k7")
      (footprint "eagle-import:M0805")
      (libsource (lib "eagle-import") (part "R-EU_M0805"))
    )
    (comp (ref "R66")
      (value "2k49")
      (footprint "eagle-import:M0805")
      (libsource (lib "eagle-import") (part "R-EU_M0805"))
    )
    (comp (ref "R67")
      (value "115k")
      (footprint "eagle-import:M0805")
      (libsource (lib "eagle-import") (part "R-EU_M0805"))
    )
    (comp (ref "R68")
      (value "13k3")
      (footprint "eagle-import:M0805")
      (libsource (lib "eagle-import") (part "R-EU_M0805"))
    )
    (comp (ref "R69")
      (value "17K4")
      (footprint "eagle-import:M0805")
      (libsource (lib "eagle-import") (part "R-EU_M0805"))
    )
    (comp (ref "R70")
      (value "2k49")
      (footprint "eagle-import:M0805")
      (libsource (lib "eagle-import") (part "R-EU_M0805"))
    )
    (comp (ref "U5")
      (value "LT1941EFEPBF")
      (footprint "eagle-import:SOP65P640X120-29N")
      (fields (field (name "MPN") "LT1941EFE#PBF"))
      (libsource (lib "eagle-import") (part "LT1941EFEPBF"))
    )
    (comp (ref "C25")
      (value "100nF")
      (footprint "eagle-import:C0805")
      (libsource (lib "eagle-import") (part "C-EUC0805"))
    )
    (comp (ref "C26")
      (value "10uF")
      (footprint "eagle-import:C0805")
      (libsource (lib "eagle-import") (part "C-EUC0805"))
    )
    (comp (ref "C31")
      (value "100nF")
      (footprint "eagle-import:C0805")
      (libsource (lib "eagle-import") (part "C-EUC0805"))
    )
    (comp (ref "C32")
      (value "100nF")
      (footprint "eagle-import:C0805")
      (libsource (lib "eagle-import") (part "C-EUC0805"))
    )
    (comp (ref "C33")
      (value "100nF")
      (footprint "eagle-import:C0805")
      (libsource (lib "eagle-import") (part "C-EUC0805"))
    )
    (comp (ref "C34")
      (value "100nF")
      (footprint "eagle-import:C0805")
      (libsource (lib "eagle-import") (part "C-EUC0805"))
    )
    (comp (ref "C39")
      (value "100nF")
      (footprint "eagle-import:C0805")
      (libsource (lib "eagle-import") (part "C-EUC0805"))
    )
    (comp (ref "C67")
      (value "10uF")
      (footprint "eagle-import:C0805")
      (libsource (lib "eagle-import") (part "C-EUC0805"))
    )
    (comp (ref "C68")
      (value "10uF")
      (footprint "eagle-import:C0805")
      (libsource (lib "eagle-import") (part "C-EUC0805"))
    )
    (comp (ref "C69")
      (value "10uF")
      (footprint "eagle-import:C0805")
      (libsource (lib "eagle-import") (part "C-EUC0805"))
    )
    (comp (ref "C70")
      (value "27pF")
      (footprint "eagle-import:C0805")
      (libsource (lib "eagle-import") (part "C-EUC0805"))
    )
    (comp (ref "C71")
      (value "27pF")
      (footprint "eagle-import:C0805")
      (libsource (lib "eagle-import") (part "C-EUC0805"))
    )
    (comp (ref "CAN")
      (value "CON_HEADER_1X04")
      (footprint "eagle-import:M1X4")
      (libsource (lib "eagle-import") (part "CON_HEADER_1X04"))
    )
    (comp (ref "DEBUG")
      (value "CON_HEADER_2X03-PTH")
      (footprint "eagle-import:M2X3")
      (libsource (lib "eagle-import") (part "CON_HEADER_2X03-PTH"))
    )
    (comp (ref "IC9")
      (value "PIC18F66K80")
      (footprint "eagle-import:TQFP64-10X10X1MM")
      (libsource (lib "eagle-import") (part "PIC18F66K80"))
    )
    (comp (ref "IC11")
      (value "MCP2551")
      (footprint "eagle-import:SO-08")
      (libsource (lib "eagle-import") (part "MCP2551"))
    )
    (comp (ref "ICSP")
      (value "CON_HEADER_PRG_PIC_ICSP0.1INCH_B")
      (footprint "eagle-import:HEADER_PRG_1X05_ICSP_B")
      (libsource (lib "eagle-import") (part "CON_HEADER_PRG_PIC_ICSP0.1INCH_B"))
    )
    (comp (ref "JP2")
      (value "HEADER-1X2ROUND")
      (footprint "eagle-import:1X02_ROUND")
      (libsource (lib "eagle-import") (part "HEADER-1X2ROUND"))
    )
    (comp (ref "LED1")
      (value "GREEN")
      (footprint "eagle-import:CHIPLED_0805")
      (libsource (lib "eagle-import") (part "LED0805"))
    )
    (comp (ref "LED2")
      (value "GREEN")
      (footprint "eagle-import:CHIPLED_0805")
      (libsource (lib "eagle-import") (part "LED0805"))
    )
    (comp (ref "LED3")
      (value "GREEN")
      (footprint "eagle-import:CHIPLED_0805")
      (libsource (lib "eagle-import") (part "LED0805"))
    )
    (comp (ref "Q3")
      (value "4MHz")
      (footprint "eagle-import:HC49_S")
      (libsource (lib "eagle-import") (part "CRYSTALHC49S"))
    )
    (comp (ref "R47")
      (value "470R")
      (footprint "eagle-import:M0805")
      (libsource (lib "eagle-import") (part "R-EU_M0805"))
    )
    (comp (ref "R48")
      (value "470R")
      (footprint "eagle-import:M0805")
      (libsource (lib "eagle-import") (part "R-EU_M0805"))
    )
    (comp (ref "R49")
      (value "470R")
      (footprint "eagle-import:M0805")
      (libsource (lib "eagle-import") (part "R-EU_M0805"))
    )
    (comp (ref "R50")
      (value "470R")
      (footprint "eagle-import:M0805")
      (libsource (lib "eagle-import") (part "R-EU_M0805"))
    )
    (comp (ref "R51")
      (value "10k")
      (footprint "eagle-import:M0805")
      (libsource (lib "eagle-import") (part "R-EU_M0805"))
    )
    (comp (ref "R52")
      (value "10k")
      (footprint "eagle-import:M0805")
      (libsource (lib "eagle-import") (part "R-EU_M0805"))
    )
    (comp (ref "R53")
      (value "10k")
      (footprint "eagle-import:M0805")
      (libsource (lib "eagle-import") (part "R-EU_M0805"))
    )
    (comp (ref "R56")
      (value "10k")
      (footprint "eagle-import:M0805")
      (libsource (lib "eagle-import") (part "R-EU_M0805"))
    )
    (comp (ref "R63")
      (value "R-EU_M0805")
      (footprint "eagle-import:M0805")
      (libsource (lib "eagle-import") (part "R-EU_M0805"))
    )
    (comp (ref "R64")
      (value "120R")
      (footprint "eagle-import:M0805")
      (libsource (lib "eagle-import") (part "R-EU_M0805"))
    )
    (comp (ref "SERIAL")
      (value "CON_HEADER_1X04")
      (footprint "eagle-import:M1X4")
      (libsource (lib "eagle-import") (part "CON_HEADER_1X04"))
    )
    (comp (ref "C72")
      (value "100nF")
      (footprint "eagle-import:C0805")
      (libsource (lib "eagle-import") (part "C-EUC0805"))
    )
    (comp (ref "C73")
      (value "100nF")
      (footprint "eagle-import:C0805")
      (libsource (lib "eagle-import") (part "C-EUC0805"))
    )
    (comp (ref "C74")
      (value "100nF")
      (footprint "eagle-import:C0805")
      (libsource (lib "eagle-import") (part "C-EUC0805"))
    )
    (comp (ref "C75")
      (value "100nF")
      (footprint "eagle-import:C0805")
      (libsource (lib "eagle-import") (part "C-EUC0805"))
    )
    (comp (ref "C76")
      (value "100nF")
      (footprint "eagle-import:C0805")
      (libsource (lib "eagle-import") (part "C-EUC0805"))
    )
    (comp (ref "C77")
      (value "100nF")
      (footprint "eagle-import:C0805")
      (libsource (lib "eagle-import") (part "C-EUC0805"))
    )
    (comp (ref "C78")
      (value "100nF")
      (footprint "eagle-import:C0805")
      (libsource (lib "eagle-import") (part "C-EUC0805"))
    )
    (comp (ref "C79")
      (value "100nF")
      (footprint "eagle-import:C0805")
      (libsource (lib "eagle-import") (part "C-EUC0805"))
    )
    (comp (ref "C80")
      (value "100nF")
      (footprint "eagle-import:C0805")
      (libsource (lib "eagle-import") (part "C-EUC0805"))
    )
    (comp (ref "IC12")
      (value "LTC4412HV")
      (footprint "eagle-import:TSOT23-6")
      (libsource (lib "eagle-import") (part "LTC4412HV"))
    )
    (comp (ref "IC13")
      (value "LMP2012")
      (footprint "eagle-import:MSOP08")
      (fields
        (field (name "MF") "TEXAS INSTRUMENTS")
        (field (name "MPN") "OPA2237EA/250")
        (field (name "MPN_1") "OPA2237EA/250")
        (field (name "OC_FARNELL") "1470365")
        (field (name "OC_NEWARK") "35C1853")
      )
      (libsource (lib "eagle-import") (part "OPA2237E"))
    )
    (comp (ref "IC14")
      (value "LTC4412HV")
      (footprint "eagle-import:TSOT23-6")
      (libsource (lib "eagle-import") (part "LTC4412HV"))
    )
    (comp (ref "IC15")
      (value "LTC4412HV")
      (footprint "eagle-import:TSOT23-6")
      (libsource (lib "eagle-import") (part "LTC4412HV"))
    )
    (comp (ref "IC16")
      (value "LTC4412HV")
      (footprint "eagle-import:TSOT23-6")
      (libsource (lib "eagle-import") (part "LTC4412HV"))
    )
    (comp (ref "IC17")
      (value "4051D")
      (footprint "eagle-import:SO16")
      (libsource (lib "eagle-import") (part "4051D"))
    )
    (comp (ref "Q4")
      (value "FDN360P")
      (footprint "eagle-import:SUPER-SOT3")
      (libsource (lib "eagle-import") (part "FDN360P"))
    )
    (comp (ref "Q5")
      (value "FDN360P")
      (footprint "eagle-import:SUPER-SOT3")
      (libsource (lib "eagle-import") (part "FDN360P"))
    )
    (comp (ref "Q6")
      (value "FDN360P")
      (footprint "eagle-import:SUPER-SOT3")
      (libsource (lib "eagle-import") (part "FDN360P"))
    )
    (comp (ref "Q7")
      (value "FDN360P")
      (footprint "eagle-import:SUPER-SOT3")
      (libsource (lib "eagle-import") (part "FDN360P"))
    )
    (comp (ref "R54")
      (value "22k")
      (footprint "eagle-import:M0805")
      (libsource (lib "eagle-import") (part "R-EU_M0805"))
    )
    (comp (ref "R55")
      (value "22k")
      (footprint "eagle-import:M0805")
      (libsource (lib "eagle-import") (part "R-EU_M0805"))
    )
    (comp (ref "R78")
      (value "220k")
      (footprint "eagle-import:M0805")
      (libsource (lib "eagle-import") (part "R-EU_M0805"))
    )
    (comp (ref "R79")
      (value "10k")
      (footprint "eagle-import:M0805")
      (libsource (lib "eagle-import") (part "R-EU_M0805"))
    )
    (comp (ref "R80")
      (value "10k")
      (footprint "eagle-import:M0805")
      (libsource (lib "eagle-import") (part "R-EU_M0805"))
    )
    (comp (ref "R81")
      (value "220k")
      (footprint "eagle-import:M0805")
      (libsource (lib "eagle-import") (part "R-EU_M0805"))
    )
    (comp (ref "R82")
      (value "0.1R")
      (footprint "eagle-import:_2818")
      (libsource (lib "eagle-import") (part "RESISTOR2818"))
    )
    (comp (ref "SJ6")
      (value "VSEL")
      (footprint "eagle-import:SJ_2")
      (libsource (lib "eagle-import") (part "SJ2W"))
    )
    (comp (ref "C1")
      (value "100nF")
      (footprint "eagle-import:C0805")
      (libsource (lib "eagle-import") (part "C-EUC0805"))
    )
    (comp (ref "C2")
      (value "2.2nF")
      (footprint "eagle-import:C0805")
      (libsource (lib "eagle-import") (part "C-EUC0805"))
    )
    (comp (ref "C3")
      (value "47nF")
      (footprint "eagle-import:C0805")
      (libsource (lib "eagle-import") (part "C-EUC0805"))
    )
    (comp (ref "C4")
      (value "10nF")
      (footprint "eagle-import:C0805")
      (libsource (lib "eagle-import") (part "C-EUC0805"))
    )
    (comp (ref "C5")
      (value "47uF")
      (footprint "eagle-import:EIA6032-28_C-R")
      (libsource (lib "eagle-import") (part "CAP_TANTALUMC/6032_REFLOW"))
    )
    (comp (ref "C7")
      (value "47uF")
      (footprint "eagle-import:EIA6032-28_C-R")
      (libsource (lib "eagle-import") (part "CAP_TANTALUMC/6032_REFLOW"))
    )
    (comp (ref "C13")
      (value "100nF")
      (footprint "eagle-import:C0805")
      (libsource (lib "eagle-import") (part "C-EUC0805"))
    )
    (comp (ref "C14")
      (value "100nF")
      (footprint "eagle-import:C0805")
      (libsource (lib "eagle-import") (part "C-EUC0805"))
    )
    (comp (ref "C36")
      (value "100nF")
      (footprint "eagle-import:C0805")
      (libsource (lib "eagle-import") (part "C-EUC0805"))
    )
    (comp (ref "C56")
      (value "47uF")
      (footprint "eagle-import:EIA6032-28_C-R")
      (libsource (lib "eagle-import") (part "CAP_TANTALUMC/6032_REFLOW"))
    )
    (comp (ref "C57")
      (value "47uF")
      (footprint "eagle-import:EIA6032-28_C-R")
      (libsource (lib "eagle-import") (part "CAP_TANTALUMC/6032_REFLOW"))
    )
    (comp (ref "C58")
      (value "100nF")
      (footprint "eagle-import:C0805")
      (libsource (lib "eagle-import") (part "C-EUC0805"))
    )
    (comp (ref "D6")
      (value "B340A-13-F")
      (footprint "eagle-import:DO214AC")
      (libsource (lib "eagle-import") (part "DIODE-DO214AC"))
    )
    (comp (ref "IC1")
      (value "LTC4412HV")
      (footprint "eagle-import:TSOT23-6")
      (libsource (lib "eagle-import") (part "LTC4412HV"))
    )
    (comp (ref "IC7")
      (value "LMP2012")
      (footprint "eagle-import:MSOP08")
      (fields
        (field (name "MF") "TEXAS INSTRUMENTS")
        (field (name "MPN") "OPA2237EA/250")
        (field (name "MPN_1") "OPA2237EA/250")
        (field (name "OC_FARNELL") "1470365")
        (field (name "OC_NEWARK") "35C1853")
      )
      (libsource (lib "eagle-import") (part "OPA2237E"))
    )
    (comp (ref "L1")
      (value "33uH")
      (footprint "eagle-import:SDR1307")
      (fields (field (name "MANUFACTURER_PART_NUMBER") "SDR1307-330KL"))
      (libsource (lib "eagle-import") (part "SDR1307-330KL"))
    )
    (comp (ref "Q1")
      (value "CSD16323Q3")
      (footprint "eagle-import:TRANS_NEXFET_Q3")
      (libsource (lib "eagle-import") (part "CSD16323Q3"))
    )
    (comp (ref "R1")
      (value "3.4k")
      (footprint "eagle-import:M0805")
      (libsource (lib "eagle-import") (part "R-EU_M0805"))
    )
    (comp (ref "R2")
      (value "71.5k")
      (footprint "eagle-import:M0805")
      (libsource (lib "eagle-import") (part "R-EU_M0805"))
    )
    (comp (ref "R3")
      (value "100")
      (footprint "eagle-import:M0805")
      (libsource (lib "eagle-import") (part "R-EU_M0805"))
    )
    (comp (ref "R4")
      (value "0.033R")
      (footprint "eagle-import:M1206")
      (libsource (lib "eagle-import") (part "R-EU_M1206"))
    )
    (comp (ref "R5")
      (value "1k")
      (footprint "eagle-import:M0805")
      (libsource (lib "eagle-import") (part "R-EU_M0805"))
    )
    (comp (ref "R6")
      (value "8.45k")
      (footprint "eagle-import:M0805")
      (libsource (lib "eagle-import") (part "R-EU_M0805"))
    )
    (comp (ref "R11")
      (value "220k")
      (footprint "eagle-import:M0805")
      (libsource (lib "eagle-import") (part "R-EU_M0805"))
    )
    (comp (ref "R12")
      (value "680k")
      (footprint "eagle-import:M0805")
      (libsource (lib "eagle-import") (part "R-EU_M0805"))
    )
    (comp (ref "R13")
      (value "680k")
      (footprint "eagle-import:M0805")
      (libsource (lib "eagle-import") (part "R-EU_M0805"))
    )
    (comp (ref "R22")
      (value "22k")
      (footprint "eagle-import:M0805")
      (libsource (lib "eagle-import") (part "R-EU_M0805"))
    )
    (comp (ref "R23")
      (value "22k")
      (footprint "eagle-import:M0805")
      (libsource (lib "eagle-import") (part "R-EU_M0805"))
    )
    (comp (ref "R24")
      (value "220k")
      (footprint "eagle-import:M0805")
      (libsource (lib "eagle-import") (part "R-EU_M0805"))
    )
    (comp (ref "R25")
      (value "33.2k")
      (footprint "eagle-import:M0805")
      (libsource (lib "eagle-import") (part "R-EU_M0805"))
    )
    (comp (ref "R27")
      (value "0.1R")
      (footprint "eagle-import:_2818")
      (libsource (lib "eagle-import") (part "RESISTOR2818"))
    )
    (comp (ref "R46")
      (value "22k")
      (footprint "eagle-import:M0805")
      (libsource (lib "eagle-import") (part "R-EU_M0805"))
    )
    (comp (ref "T1")
      (value "Si9933CDY")
      (footprint "eagle-import:SO8")
      (libsource (lib "eagle-import") (part "PMOS2SO8"))
    )
    (comp (ref "T2")
      (value "Si9933CDY")
      (footprint "eagle-import:SO8")
      (libsource (lib "eagle-import") (part "PMOS2SO8"))
    )
    (comp (ref "TP10")
      (value "TESTPOINT0.1\"")
      (footprint "eagle-import:1X01_ROUND")
      (libsource (lib "eagle-import") (part "TESTPOINT0.1{dblquote}"))
    )
    (comp (ref "TP11")
      (value "TESTPOINT0.1\"")
      (footprint "eagle-import:1X01_ROUND")
      (fields (field (name "BOM") "EXCLUDE"))
      (libsource (lib "eagle-import") (part "TESTPOINT0.1{dblquote}"))
    )
    (comp (ref "U6")
      (value "LM3488MM/NOPB")
      (footprint "eagle-import:MUA08A")
      (libsource (lib "eagle-import") (part "LM3488MM/NOPB"))
    )
    (comp (ref "C19")
      (value "100nF")
      (footprint "eagle-import:C0805")
      (libsource (lib "eagle-import") (part "C-EUC0805"))
    )
    (comp (ref "C20")
      (value "100nF")
      (footprint "eagle-import:C0805")
      (libsource (lib "eagle-import") (part "C-EUC0805"))
    )
    (comp (ref "C38")
      (value "100nF")
      (footprint "eagle-import:C0805")
      (libsource (lib "eagle-import") (part "C-EUC0805"))
    )
    (comp (ref "IC4")
      (value "LTC4412HV")
      (footprint "eagle-import:TSOT23-6")
      (libsource (lib "eagle-import") (part "LTC4412HV"))
    )
    (comp (ref "IC8")
      (value "LMP2012")
      (footprint "eagle-import:MSOP08")
      (fields
        (field (name "MF") "TEXAS INSTRUMENTS")
        (field (name "MPN") "OPA2237EA/250")
        (field (name "MPN_1") "OPA2237EA/250")
        (field (name "OC_FARNELL") "1470365")
        (field (name "OC_NEWARK") "35C1853")
      )
      (libsource (lib "eagle-import") (part "OPA2237E"))
    )
    (comp (ref "Q2")
      (value "FDN360P")
      (footprint "eagle-import:SUPER-SOT3")
      (libsource (lib "eagle-import") (part "FDN360P"))
    )
    (comp (ref "R39")
      (value "22k")
      (footprint "eagle-import:M0805")
      (libsource (lib "eagle-import") (part "R-EU_M0805"))
    )
    (comp (ref "R40")
      (value "22k")
      (footprint "eagle-import:M0805")
      (libsource (lib "eagle-import") (part "R-EU_M0805"))
    )
    (comp (ref "R41")
      (value "220k")
      (footprint "eagle-import:M0805")
      (libsource (lib "eagle-import") (part "R-EU_M0805"))
    )
    (comp (ref "R42")
      (value "10k")
      (footprint "eagle-import:M0805")
      (libsource (lib "eagle-import") (part "R-EU_M0805"))
    )
    (comp (ref "R43")
      (value "10k")
      (footprint "eagle-import:M0805")
      (libsource (lib "eagle-import") (part "R-EU_M0805"))
    )
    (comp (ref "R44")
      (value "0.1R")
      (footprint "eagle-import:_2818")
      (libsource (lib "eagle-import") (part "RESISTOR2818"))
    )
    (comp (ref "R77")
      (value "220k")
      (footprint "eagle-import:M0805")
      (libsource (lib "eagle-import") (part "R-EU_M0805"))
    )
    (comp (ref "C6")
      (value "100nF")
      (footprint "eagle-import:C0805")
      (libsource (lib "eagle-import") (part "C-EUC0805"))
    )
    (comp (ref "C9")
      (value "22uF")
      (footprint "eagle-import:EIA6032-28_C-R")
      (libsource (lib "eagle-import") (part "CAP_TANTALUMC/6032_REFLOW"))
    )
    (comp (ref "C10")
      (value "47uF")
      (footprint "eagle-import:EIA6032-28_C-R")
      (libsource (lib "eagle-import") (part "CAP_TANTALUMC/6032_REFLOW"))
    )
    (comp (ref "C15")
      (value "100nF")
      (footprint "eagle-import:C0805")
      (libsource (lib "eagle-import") (part "C-EUC0805"))
    )
    (comp (ref "C16")
      (value "100nF")
      (footprint "eagle-import:C0805")
      (libsource (lib "eagle-import") (part "C-EUC0805"))
    )
    (comp (ref "C35")
      (value "100nF")
      (footprint "eagle-import:C0805")
      (libsource (lib "eagle-import") (part "C-EUC0805"))
    )
    (comp (ref "C59")
      (value "100nF")
      (footprint "eagle-import:C0805")
      (libsource (lib "eagle-import") (part "C-EUC0805"))
    )
    (comp (ref "C60")
      (value "100nF")
      (footprint "eagle-import:C0805")
      (libsource (lib "eagle-import") (part "C-EUC0805"))
    )
    (comp (ref "IC2")
      (value "LTC4412HV")
      (footprint "eagle-import:TSOT23-6")
      (libsource (lib "eagle-import") (part "LTC4412HV"))
    )
    (comp (ref "IC5")
      (value "LMP2012")
      (footprint "eagle-import:MSOP08")
      (fields
        (field (name "MF") "TEXAS INSTRUMENTS")
        (field (name "MPN") "OPA2237EA/250")
        (field (name "MPN_1") "OPA2237EA/250")
        (field (name "OC_FARNELL") "1470365")
        (field (name "OC_NEWARK") "35C1853")
      )
      (libsource (lib "eagle-import") (part "OPA2237E"))
    )
    (comp (ref "L3")
      (value "3.3uH")
      (footprint "eagle-import:SRR6038")
      (fields (field (name "MANUFACTURER_PART_NUMBER") "SRR6038-3R3Y"))
      (libsource (lib "eagle-import") (part "SRR6038-3R3Y"))
    )
    (comp (ref "R7")
      (value "56.2k")
      (footprint "eagle-import:M0805")
      (libsource (lib "eagle-import") (part "R-EU_M0805"))
    )
    (comp (ref "R8")
      (value "10k")
      (footprint "eagle-import:M0805")
      (libsource (lib "eagle-import") (part "R-EU_M0805"))
    )
    (comp (ref "R16")
      (value "680k")
      (footprint "eagle-import:M0805")
      (libsource (lib "eagle-import") (part "R-EU_M0805"))
    )
    (comp (ref "R20")
      (value "1k5")
      (footprint "eagle-import:M0805")
      (libsource (lib "eagle-import") (part "R-EU_M0805"))
    )
    (comp (ref "R21")
      (value "22k")
      (footprint "eagle-import:M0805")
      (libsource (lib "eagle-import") (part "R-EU_M0805"))
    )
    (comp (ref "R26")
      (value "220k")
      (footprint "eagle-import:M0805")
      (libsource (lib "eagle-import") (part "R-EU_M0805"))
    )
    (comp (ref "R28")
      (value "22k")
      (footprint "eagle-import:M0805")
      (libsource (lib "eagle-import") (part "R-EU_M0805"))
    )
    (comp (ref "R29")
      (value "220k")
      (footprint "eagle-import:M0805")
      (libsource (lib "eagle-import") (part "R-EU_M0805"))
    )
    (comp (ref "R30")
      (value "680k")
      (footprint "eagle-import:M0805")
      (libsource (lib "eagle-import") (part "R-EU_M0805"))
    )
    (comp (ref "R31")
      (value "10k")
      (footprint "eagle-import:M0805")
      (libsource (lib "eagle-import") (part "R-EU_M0805"))
    )
    (comp (ref "R32")
      (value "0.1R")
      (footprint "eagle-import:_2818")
      (libsource (lib "eagle-import") (part "RESISTOR2818"))
    )
    (comp (ref "SJ3")
      (value "SOLDERJUMPER")
      (footprint "eagle-import:SOLDERJUMPER_ARROW_NOPASTE")
      (libsource (lib "eagle-import") (part "SOLDERJUMPER"))
    )
    (comp (ref "T3")
      (value "Si9933CDY")
      (footprint "eagle-import:SO8")
      (libsource (lib "eagle-import") (part "PMOS2SO8"))
    )
    (comp (ref "T4")
      (value "Si9933CDY")
      (footprint "eagle-import:SO8")
      (libsource (lib "eagle-import") (part "PMOS2SO8"))
    )
    (comp (ref "TP1")
      (value "TESTPOINT0.1\"")
      (footprint "eagle-import:1X01_ROUND")
      (libsource (lib "eagle-import") (part "TESTPOINT0.1{dblquote}"))
    )
    (comp (ref "TP2")
      (value "TESTPOINT0.1\"")
      (footprint "eagle-import:1X01_ROUND")
      (fields (field (name "BOM") "EXCLUDE"))
      (libsource (lib "eagle-import") (part "TESTPOINT0.1{dblquote}"))
    )
    (comp (ref "TP3")
      (value "TESTPOINT0.1\"")
      (footprint "eagle-import:1X01_ROUND")
      (fields (field (name "BOM") "EXCLUDE"))
      (libsource (lib "eagle-import") (part "TESTPOINT0.1{dblquote}"))
    )
    (comp (ref "TP4")
      (value "TESTPOINT0.1\"")
      (footprint "eagle-import:1X01_ROUND")
      (fields (field (name "BOM") "EXCLUDE"))
      (libsource (lib "eagle-import") (part "TESTPOINT0.1{dblquote}"))
    )
    (comp (ref "TP5")
      (value "TESTPOINT0.1\"")
      (footprint "eagle-import:1X01_ROUND")
      (fields (field (name "BOM") "EXCLUDE"))
      (libsource (lib "eagle-import") (part "TESTPOINT0.1{dblquote}"))
    )
    (comp (ref "U1")
      (value "TPS563200DDCR")
      (footprint "eagle-import:DDC0006A")
      (fields
        (field (name "MANUFACTURER") "Texas Instruments")
        (field (name "PARTNUMBER") "TPS563200DDC")
        (field (name "APPROVEDBY") "Not shown in title block")
        (field (name "AUTHOR") "Not shown in title block")
        (field (name "CHECKEDBY") "Not shown in title block")
        (field (name "ENGINEER") "Not shown in title block")
        (field (name "MODIFIEDDATE") "Not shown in title block")
        (field (name "PUBLISHER") "Texas Instruments")
        (field (name "SYMBOLCREATOR") "a0411947")
      )
      (libsource (lib "eagle-import") (part "TPS563200DDCR"))
    )
    (comp (ref "C28")
      (value "100nF")
      (footprint "eagle-import:C0805")
      (libsource (lib "eagle-import") (part "C-EUC0805"))
    )
    (comp (ref "C29")
      (value "22uF")
      (footprint "eagle-import:EIA6032-28_C-R")
      (libsource (lib "eagle-import") (part "CAP_TANTALUMC/6032_REFLOW"))
    )
    (comp (ref "C30")
      (value "47uF")
      (footprint "eagle-import:EIA6032-28_C-R")
      (libsource (lib "eagle-import") (part "CAP_TANTALUMC/6032_REFLOW"))
    )
    (comp (ref "C65")
      (value "100nF")
      (footprint "eagle-import:C0805")
      (libsource (lib "eagle-import") (part "C-EUC0805"))
    )
    (comp (ref "C66")
      (value "100nF")
      (footprint "eagle-import:C0805")
      (libsource (lib "eagle-import") (part "C-EUC0805"))
    )
    (comp (ref "D7")
      (value "B340A-13-F")
      (footprint "eagle-import:DO214AC")
      (libsource (lib "eagle-import") (part "DIODE-DO214AC"))
    )
    (comp (ref "L4")
      (value "3.3uH")
      (footprint "eagle-import:SRR6038")
      (fields (field (name "MANUFACTURER_PART_NUMBER") "SRR6038-3R3Y"))
      (libsource (lib "eagle-import") (part "SRR6038-3R3Y"))
    )
    (comp (ref "R57")
      (value "56.2k")
      (footprint "eagle-import:M0805")
      (libsource (lib "eagle-import") (part "R-EU_M0805"))
    )
    (comp (ref "R58")
      (value "10k")
      (footprint "eagle-import:M0805")
      (libsource (lib "eagle-import") (part "R-EU_M0805"))
    )
    (comp (ref "SJ5")
      (value "SOLDERJUMPER")
      (footprint "eagle-import:SOLDERJUMPER_ARROW_NOPASTE")
      (libsource (lib "eagle-import") (part "SOLDERJUMPER"))
    )
    (comp (ref "TP8")
      (value "TESTPOINT0.1\"")
      (footprint "eagle-import:1X01_ROUND")
      (libsource (lib "eagle-import") (part "TESTPOINT0.1{dblquote}"))
    )
    (comp (ref "TP9")
      (value "TESTPOINT0.1\"")
      (footprint "eagle-import:1X01_ROUND")
      (fields (field (name "BOM") "EXCLUDE"))
      (libsource (lib "eagle-import") (part "TESTPOINT0.1{dblquote}"))
    )
    (comp (ref "U4")
      (value "TPS563200DDCR")
      (footprint "eagle-import:DDC0006A")
      (fields
        (field (name "MANUFACTURER") "Texas Instruments")
        (field (name "PARTNUMBER") "TPS563200DDC")
        (field (name "APPROVEDBY") "Not shown in title block")
        (field (name "AUTHOR") "Not shown in title block")
        (field (name "CHECKEDBY") "Not shown in title block")
        (field (name "ENGINEER") "Not shown in title block")
        (field (name "MODIFIEDDATE") "Not shown in title block")
        (field (name "PUBLISHER") "Texas Instruments")
        (field (name "SYMBOLCREATOR") "a0411947")
      )
      (libsource (lib "eagle-import") (part "TPS563200DDCR"))
    )
    (comp (ref "C81")
      (value "100nF")
      (footprint "eagle-import:C0805")
      (libsource (lib "eagle-import") (part "C-EUC0805"))
    )
    (comp (ref "D8")
      (value "B340A-13-F")
      (footprint "eagle-import:DO214AC")
      (libsource (lib "eagle-import") (part "DIODE-DO214AC"))
    )
    (comp (ref "D9")
      (value "B340A-13-F")
      (footprint "eagle-import:DO214AC")
      (libsource (lib "eagle-import") (part "DIODE-DO214AC"))
    )
    (comp (ref "D10")
      (value "B340A-13-F")
      (footprint "eagle-import:DO214AC")
      (libsource (lib "eagle-import") (part "DIODE-DO214AC"))
    )
    (comp (ref "D11")
      (value "B340A-13-F")
      (footprint "eagle-import:DO214AC")
      (libsource (lib "eagle-import") (part "DIODE-DO214AC"))
    )
    (comp (ref "D12")
      (value "B340A-13-F")
      (footprint "eagle-import:DO214AC")
      (libsource (lib "eagle-import") (part "DIODE-DO214AC"))
    )
    (comp (ref "D13")
      (value "B340A-13-F")
      (footprint "eagle-import:DO214AC")
      (libsource (lib "eagle-import") (part "DIODE-DO214AC"))
    )
    (comp (ref "IC18")
      (value "TMP35B")
      (footprint "eagle-import:TO92-LINE")
      (libsource (lib "eagle-import") (part "TMP35B"))
    )
    (comp (ref "S1")
      (value "TASCSOLARCELL")
      (footprint "eagle-import:TASCSOLARCELL")
      (libsource (lib "eagle-import") (part "TASCSOLARCELL"))
    )
    (comp (ref "S2")
      (value "TASCSOLARCELL")
      (footprint "eagle-import:TASCSOLARCELL")
      (libsource (lib "eagle-import") (part "TASCSOLARCELL"))
    )
    (comp (ref "S3")
      (value "TASCSOLARCELL")
      (footprint "eagle-import:TASCSOLARCELL")
      (libsource (lib "eagle-import") (part "TASCSOLARCELL"))
    )
    (comp (ref "S4")
      (value "TASCSOLARCELL")
      (footprint "eagle-import:TASCSOLARCELL")
      (libsource (lib "eagle-import") (part "TASCSOLARCELL"))
    )
    (comp (ref "S5")
      (value "TASCSOLARCELL")
      (footprint "eagle-import:TASCSOLARCELL")
      (libsource (lib "eagle-import") (part "TASCSOLARCELL"))
    )
    (comp (ref "S6")
      (value "TASCSOLARCELL")
      (footprint "eagle-import:TASCSOLARCELL")
      (libsource (lib "eagle-import") (part "TASCSOLARCELL"))
    )
    (comp (ref "S7")
      (value "TASCSOLARCELL")
      (footprint "eagle-import:TASCSOLARCELL")
      (libsource (lib "eagle-import") (part "TASCSOLARCELL"))
    )
    (comp (ref "S8")
      (value "TASCSOLARCELL")
      (footprint "eagle-import:TASCSOLARCELL")
      (libsource (lib "eagle-import") (part "TASCSOLARCELL"))
    )
    (comp (ref "S9")
      (value "TASCSOLARCELL")
      (footprint "eagle-import:TASCSOLARCELL")
      (libsource (lib "eagle-import") (part "TASCSOLARCELL"))
    )
    (comp (ref "S10")
      (value "TASCSOLARCELL")
      (footprint "eagle-import:TASCSOLARCELL")
      (libsource (lib "eagle-import") (part "TASCSOLARCELL"))
    )
    (comp (ref "S11")
      (value "TASCSOLARCELL")
      (footprint "eagle-import:TASCSOLARCELL")
      (libsource (lib "eagle-import") (part "TASCSOLARCELL"))
    )
    (comp (ref "S12")
      (value "TASCSOLARCELL")
      (footprint "eagle-import:TASCSOLARCELL")
      (libsource (lib "eagle-import") (part "TASCSOLARCELL"))
    )
    (comp (ref "S13")
      (value "TASCSOLARCELL")
      (footprint "eagle-import:TASCSOLARCELL")
      (libsource (lib "eagle-import") (part "TASCSOLARCELL"))
    )
    (comp (ref "S14")
      (value "TASCSOLARCELL")
      (footprint "eagle-import:TASCSOLARCELL")
      (libsource (lib "eagle-import") (part "TASCSOLARCELL"))
    )
    (comp (ref "S15")
      (value "TASCSOLARCELL")
      (footprint "eagle-import:TASCSOLARCELL")
      (libsource (lib "eagle-import") (part "TASCSOLARCELL"))
    )
    (comp (ref "S16")
      (value "TASCSOLARCELL")
      (footprint "eagle-import:TASCSOLARCELL")
      (libsource (lib "eagle-import") (part "TASCSOLARCELL"))
    )
    (comp (ref "S17")
      (value "TASCSOLARCELL")
      (footprint "eagle-import:TASCSOLARCELL")
      (libsource (lib "eagle-import") (part "TASCSOLARCELL"))
    )
    (comp (ref "S18")
      (value "TASCSOLARCELL")
      (footprint "eagle-import:TASCSOLARCELL")
      (libsource (lib "eagle-import") (part "TASCSOLARCELL"))
    )
    (comp (ref "S19")
      (value "TASCSOLARCELL")
      (footprint "eagle-import:TASCSOLARCELL")
      (libsource (lib "eagle-import") (part "TASCSOLARCELL"))
    )
    (comp (ref "S20")
      (value "TASCSOLARCELL")
      (footprint "eagle-import:TASCSOLARCELL")
      (libsource (lib "eagle-import") (part "TASCSOLARCELL"))
    )
    (comp (ref "S21")
      (value "TASCSOLARCELL")
      (footprint "eagle-import:TASCSOLARCELL")
      (libsource (lib "eagle-import") (part "TASCSOLARCELL"))
    )
    (comp (ref "S22")
      (value "TASCSOLARCELL")
      (footprint "eagle-import:TASCSOLARCELL")
      (libsource (lib "eagle-import") (part "TASCSOLARCELL"))
    )
    (comp (ref "S23")
      (value "TASCSOLARCELL")
      (footprint "eagle-import:TASCSOLARCELL")
      (libsource (lib "eagle-import") (part "TASCSOLARCELL"))
    )
    (comp (ref "S24")
      (value "TASCSOLARCELL")
      (footprint "eagle-import:TASCSOLARCELL")
      (libsource (lib "eagle-import") (part "TASCSOLARCELL"))
    )
    (comp (ref "X1")
      (value "DF13DF13A-8P-1.25H")
      (footprint "eagle-import:DF13A-8P")
      (libsource (lib "eagle-import") (part "DF13DF13A-8P-1.25H"))
    )
  )
  (nets
    (net (code "1") (name "+3V3") (class "Default")
      (node (ref "R34") (pin "2") (pinfunction "2_2") (pintype "passive"))
      (node (ref "R36") (pin "1") (pinfunction "1_1") (pintype "passive"))
      (node (ref "R38") (pin "2") (pinfunction "2_2") (pintype "passive"))
      (node (ref "V_BUS") (pin "21") (pinfunction "21_21") (pintype "passive"))
      (node (ref "V_BUS") (pin "23") (pinfunction "23_23") (pintype "passive"))
      (node (ref "V_BUS") (pin "25") (pinfunction "25_25") (pintype "passive"))
      (node (ref "V_BUS") (pin "27") (pinfunction "27_27") (pintype "passive"))
      (node (ref "V_BUS") (pin "29") (pinfunction "29_29") (pintype "passive"))
    )
    (net (code "2") (name "+5V") (class "Default")
      (node (ref "D7") (pin "A") (pinfunction "A_A") (pintype "passive"))
      (node (ref "R20") (pin "1") (pinfunction "1_1") (pintype "passive"))
      (node (ref "R28") (pin "2") (pinfunction "2_2") (pintype "passive"))
      (node (ref "R32") (pin "2") (pinfunction "2_2") (pintype "passive"))
      (node (ref "TP5") (pin "1") (pinfunction "P$1_1") (pintype "bidirectional"))
      (node (ref "V_BUS") (pin "11") (pinfunction "11_11") (pintype "passive"))
      (node (ref "V_BUS") (pin "13") (pinfunction "13_13") (pintype "passive"))
      (node (ref "V_BUS") (pin "15") (pinfunction "15_15") (pintype "passive"))
      (node (ref "V_BUS") (pin "17") (pinfunction "17_17") (pintype "passive"))
      (node (ref "V_BUS") (pin "19") (pinfunction "19_19") (pintype "passive"))
    )
    (net (code "3") (name "+12V") (class "Default")
      (node (ref "R23") (pin "2") (pinfunction "2_2") (pintype "passive"))
      (node (ref "R25") (pin "1") (pinfunction "1_1") (pintype "passive"))
      (node (ref "R27") (pin "2") (pinfunction "2_2") (pintype "passive"))
      (node (ref "V_BUS") (pin "1") (pinfunction "1_1") (pintype "passive"))
      (node (ref "V_BUS") (pin "3") (pinfunction "3_3") (pintype "passive"))
      (node (ref "V_BUS") (pin "5") (pinfunction "5_5") (pintype "passive"))
      (node (ref "V_BUS") (pin "7") (pinfunction "7_7") (pintype "passive"))
      (node (ref "V_BUS") (pin "9") (pinfunction "9_9") (pintype "passive"))
    )
    (net (code "4") (name "+VFOTO_CELL_+X") (class "Default")
      (node (ref "+X") (pin "1") (pinfunction "1_1") (pintype "passive"))
    )
    (net (code "5") (name "+VFOTO_CELL_+Y") (class "Default")
      (node (ref "+Y") (pin "1") (pinfunction "1_1") (pintype "passive"))
      (node (ref "Q6") (pin "3") (pinfunction "D_3") (pintype "passive"))
    )
    (net (code "6") (name "+VFOTO_CELL_-X") (class "Default")
      (node (ref "-X") (pin "1") (pinfunction "1_1") (pintype "passive"))
    )
    (net (code "7") (name "+VFOTO_CELL_-Y") (class "Default")
      (node (ref "-Y") (pin "1") (pinfunction "1_1") (pintype "passive"))
    )
    (net (code "8") (name "AD_IOUT_3V3") (class "Default")
      (node (ref "IC6") (pin "1") (pinfunction "OUT_1") (pintype "output"))
      (node (ref "IC9") (pin "37") (pinfunction "RE0/AN5/~{RD}_37") (pintype "input"))
      (node (ref "R35") (pin "1") (pinfunction "1_1") (pintype "passive"))
    )
    (net (code "9") (name "AD_IOUT_5V") (class "Default")
      (node (ref "IC5") (pin "1") (pinfunction "OUT_1") (pintype "output"))
      (node (ref "IC9") (pin "32") (pinfunction "RA3/VREF+/AN3_32") (pintype "bidirectional"))
      (node (ref "R29") (pin "1") (pinfunction "1_1") (pintype "passive"))
    )
    (net (code "10") (name "AD_IOUT_12V") (class "Default")
      (node (ref "IC7") (pin "1") (pinfunction "OUT_1") (pintype "output"))
      (node (ref "IC9") (pin "30") (pinfunction "RA1/AN1/C1INC_30") (pintype "bidirectional"))
      (node (ref "R24") (pin "1") (pinfunction "1_1") (pintype "passive"))
    )
    (net (code "11") (name "AD_IOUT_NREGV") (class "Default")
      (node (ref "IC8") (pin "1") (pinfunction "OUT_1") (pintype "output"))
      (node (ref "IC9") (pin "39") (pinfunction "RE2/AN7/C2OUT/~{CS}_39") (pintype "bidirectional"))
      (node (ref "R41") (pin "1") (pinfunction "1_1") (pintype "passive"))
    )
    (net (code "12") (name "AD_IOUT_VCELL") (class "Default")
      (node (ref "IC13") (pin "1") (pinfunction "OUT_1") (pintype "output"))
      (node (ref "IC17") (pin "5") (pinfunction "X5_5") (pintype "bidirectional"))
      (node (ref "R78") (pin "1") (pinfunction "1_1") (pintype "passive"))
    )
    (net (code "13") (name "AD_TEMP_BAT") (class "Default")
      (node (ref "IC10") (pin "2") (pinfunction "VOUT_2") (pintype "bidirectional"))
      (node (ref "IC17") (pin "2") (pinfunction "X6_2") (pintype "bidirectional"))
      (node (ref "SJ7") (pin "1") (pinfunction "1_1") (pintype "passive"))
    )
    (net (code "14") (name "AD_VOUT_3V3") (class "Default")
      (node (ref "IC6") (pin "7") (pinfunction "OUT_7") (pintype "output"))
      (node (ref "IC9") (pin "34") (pinfunction "RA5/AN4/HLVDIN/T1CKI/~{SS}_34") (pintype "bidirectional"))
      (node (ref "R72") (pin "2") (pinfunction "2_2") (pintype "passive"))
    )
    (net (code "15") (name "AD_VOUT_5V") (class "Default")
      (node (ref "IC5") (pin "6") (pinfunction "-IN_6") (pintype "input"))
      (node (ref "IC5") (pin "7") (pinfunction "OUT_7") (pintype "output"))
      (node (ref "IC9") (pin "31") (pinfunction "RA2/VREF-/AN2/C2INC_31") (pintype "bidirectional"))
    )
    (net (code "16") (name "AD_VOUT_12V") (class "Default")
      (node (ref "IC7") (pin "6") (pinfunction "-IN_6") (pintype "input"))
      (node (ref "IC7") (pin "7") (pinfunction "OUT_7") (pintype "output"))
      (node (ref "IC9") (pin "29") (pinfunction "RA0/CVREF/AN0/ULPWU_29") (pintype "bidirectional"))
    )
    (net (code "17") (name "AD_VOUT_NREGV") (class "Default")
      (node (ref "IC8") (pin "6") (pinfunction "-IN_6") (pintype "input"))
      (node (ref "IC8") (pin "7") (pinfunction "OUT_7") (pintype "output"))
      (node (ref "IC9") (pin "38") (pinfunction "RE1/AN6/C1OUT/~{WR}_38") (pintype "bidirectional"))
    )
    (net (code "18") (name "AD_VOUT_VCELL") (class "Default")
      (node (ref "IC13") (pin "6") (pinfunction "-IN_6") (pintype "input"))
      (node (ref "IC13") (pin "7") (pinfunction "OUT_7") (pintype "output"))
      (node (ref "IC17") (pin "1") (pinfunction "X4_1") (pintype "bidirectional"))
    )
    (net (code "19") (name "AUX") (class "Default")
      (node (ref "BACKUP") (pin "24") (pinfunction "24_24") (pintype "passive"))
      (node (ref "BACKUP1") (pin "24") (pinfunction "24_24") (pintype "passive"))
      (node (ref "IC12") (pin "3") (pinfunction "CTL_3") (pintype "passive"))
      (node (ref "IC9") (pin "13") (pinfunction "RB0/AN10/FLT0/INT0_13") (pintype "bidirectional"))
    )
    (net (code "20") (name "AUX_1") (class "Default")
      (node (ref "BACKUP1") (pin "28") (pinfunction "28_28") (pintype "passive"))
      (node (ref "IC17") (pin "11") (pinfunction "A_11") (pintype "input"))
    )
    (net (code "21") (name "AUX_2") (class "Default")
      (node (ref "BACKUP1") (pin "30") (pinfunction "30_30") (pintype "passive"))
      (node (ref "IC17") (pin "10") (pinfunction "B_10") (pintype "input"))
    )
    (net (code "22") (name "AUX_3") (class "Default")
      (node (ref "BACKUP1") (pin "32") (pinfunction "32_32") (pintype "passive"))
      (node (ref "IC17") (pin "9") (pinfunction "C_9") (pintype "input"))
    )
    (net (code "23") (name "AUX_4") (class "Default")
      (node (ref "BACKUP1") (pin "27") (pinfunction "27_27") (pintype "passive"))
      (node (ref "IC16") (pin "3") (pinfunction "CTL_3") (pintype "passive"))
    )
    (net (code "24") (name "AUX_5") (class "Default")
      (node (ref "BACKUP1") (pin "29") (pinfunction "29_29") (pintype "passive"))
    )
    (net (code "25") (name "AUX_6") (class "Default")
      (node (ref "BACKUP") (pin "22") (pinfunction "22_22") (pintype "passive"))
      (node (ref "BACKUP1") (pin "22") (pinfunction "22_22") (pintype "passive"))
      (node (ref "IC14") (pin "3") (pinfunction "CTL_3") (pintype "passive"))
      (node (ref "IC9") (pin "2") (pinfunction "RD4/ECCP1/P1A/PSP4_2") (pintype "bidirectional"))
    )
    (net (code "26") (name "AUX_7") (class "Default")
      (node (ref "BACKUP") (pin "21") (pinfunction "21_21") (pintype "passive"))
      (node (ref "BACKUP1") (pin "21") (pinfunction "21_21") (pintype "passive"))
      (node (ref "IC15") (pin "3") (pinfunction "CTL_3") (pintype "passive"))
      (node (ref "IC9") (pin "1") (pinfunction "RC7/CCP4_1") (pintype "bidirectional"))
    )
    (net (code "27") (name "BOT1") (class "Default")
      (node (ref "DEBUG") (pin "2") (pinfunction "2_2") (pintype "passive"))
      (node (ref "IC9") (pin "54") (pinfunction "RD0/C1INA/PSP0_54") (pintype "bidirectional"))
      (node (ref "R51") (pin "1") (pinfunction "1_1") (pintype "passive"))
    )
    (net (code "28") (name "BOT2") (class "Default")
      (node (ref "DEBUG") (pin "4") (pinfunction "4_4") (pintype "passive"))
      (node (ref "IC9") (pin "55") (pinfunction "RD1/C1INB/PSP1_55") (pintype "bidirectional"))
      (node (ref "R52") (pin "1") (pinfunction "1_1") (pintype "passive"))
    )
    (net (code "29") (name "BOT3") (class "Default")
      (node (ref "DEBUG") (pin "6") (pinfunction "6_6") (pintype "passive"))
      (node (ref "IC9") (pin "58") (pinfunction "RD2/C2INA/PSP2_58") (pintype "bidirectional"))
      (node (ref "R56") (pin "1") (pinfunction "1_1") (pintype "passive"))
    )
    (net (code "30") (name "CANRX") (class "Default")
      (node (ref "IC11") (pin "4") (pinfunction "RXD_4") (pintype "bidirectional"))
      (node (ref "IC9") (pin "16") (pinfunction "RB3/CANRX/CTED2/INT3_16") (pintype "bidirectional"))
    )
    (net (code "31") (name "CANTX") (class "Default")
      (node (ref "IC11") (pin "1") (pinfunction "TXD_1") (pintype "bidirectional"))
      (node (ref "IC9") (pin "15") (pinfunction "RB2/CANTX/CTED1/INT2_15") (pintype "bidirectional"))
    )
    (net (code "32") (name "CTL_3V3") (class "Default")
      (node (ref "IC3") (pin "3") (pinfunction "CTL_3") (pintype "passive"))
      (node (ref "IC9") (pin "18") (pinfunction "RG4/T0CKI_18") (pintype "bidirectional"))
    )
    (net (code "33") (name "CTL_5V") (class "Default")
      (node (ref "IC2") (pin "3") (pinfunction "CTL_3") (pintype "passive"))
      (node (ref "IC9") (pin "19") (pinfunction "RF1_19") (pintype "bidirectional"))
    )
    (net (code "34") (name "CTL_12V") (class "Default")
      (node (ref "IC1") (pin "3") (pinfunction "CTL_3") (pintype "passive"))
      (node (ref "IC9") (pin "20") (pinfunction "RB4/AN9/CTPLS/KBI0_20") (pintype "input"))
    )
    (net (code "35") (name "CTL_NREGV") (class "Default")
      (node (ref "IC4") (pin "3") (pinfunction "CTL_3") (pintype "passive"))
      (node (ref "IC9") (pin "17") (pinfunction "RF0/MDMIN_17") (pintype "bidirectional"))
    )
    (net (code "36") (name "GND") (class "Default")
      (node (ref "+X") (pin "2") (pinfunction "2_2") (pintype "passive"))
      (node (ref "+X") (pin "5") (pinfunction "5_5") (pintype "passive"))
      (node (ref "+Y") (pin "2") (pinfunction "2_2") (pintype "passive"))
      (node (ref "+Y") (pin "5") (pinfunction "5_5") (pintype "passive"))
      (node (ref "-X") (pin "2") (pinfunction "2_2") (pintype "passive"))
      (node (ref "-X") (pin "5") (pinfunction "5_5") (pintype "passive"))
      (node (ref "-Y") (pin "2") (pinfunction "2_2") (pintype "passive"))
      (node (ref "-Y") (pin "5") (pinfunction "5_5") (pintype "passive"))
      (node (ref "BACKUP") (pin "17") (pinfunction "17_17") (pintype "passive"))
      (node (ref "BACKUP") (pin "18") (pinfunction "18_18") (pintype "passive"))
      (node (ref "BACKUP") (pin "19") (pinfunction "19_19") (pintype "passive"))
      (node (ref "BACKUP") (pin "20") (pinfunction "20_20") (pintype "passive"))
      (node (ref "BACKUP1") (pin "17") (pinfunction "17_17") (pintype "passive"))
      (node (ref "BACKUP1") (pin "18") (pinfunction "18_18") (pintype "passive"))
      (node (ref "BACKUP1") (pin "19") (pinfunction "19_19") (pintype "passive"))
      (node (ref "BACKUP1") (pin "20") (pinfunction "20_20") (pintype "passive"))
      (node (ref "BAT") (pin "2") (pinfunction "2_2") (pintype "passive"))
      (node (ref "C1") (pin "2") (pinfunction "2_2") (pintype "passive"))
      (node (ref "C10") (pin "-") (pinfunction "-_-") (pintype "passive"))
      (node (ref "C11") (pin "-") (pinfunction "-_-") (pintype "passive"))
      (node (ref "C12") (pin "-") (pinfunction "-_-") (pintype "passive"))
      (node (ref "C13") (pin "1") (pinfunction "1_1") (pintype "passive"))
      (node (ref "C14") (pin "1") (pinfunction "1_1") (pintype "passive"))
      (node (ref "C15") (pin "1") (pinfunction "1_1") (pintype "passive"))
      (node (ref "C16") (pin "1") (pinfunction "1_1") (pintype "passive"))
      (node (ref "C17") (pin "1") (pinfunction "1_1") (pintype "passive"))
      (node (ref "C18") (pin "1") (pinfunction "1_1") (pintype "passive"))
      (node (ref "C19") (pin "1") (pinfunction "1_1") (pintype "passive"))
      (node (ref "C2") (pin "2") (pinfunction "2_2") (pintype "passive"))
      (node (ref "C20") (pin "1") (pinfunction "1_1") (pintype "passive"))
      (node (ref "C21") (pin "1") (pinfunction "1_1") (pintype "passive"))
      (node (ref "C22") (pin "-") (pinfunction "-_-") (pintype "passive"))
      (node (ref "C23") (pin "1") (pinfunction "1_1") (pintype "passive"))
      (node (ref "C24") (pin "1") (pinfunction "1_1") (pintype "passive"))
      (node (ref "C25") (pin "1") (pinfunction "1_1") (pintype "passive"))
      (node (ref "C26") (pin "1") (pinfunction "1_1") (pintype "passive"))
      (node (ref "C27") (pin "1") (pinfunction "1_1") (pintype "passive"))
      (node (ref "C29") (pin "-") (pinfunction "-_-") (pintype "passive"))
      (node (ref "C30") (pin "-") (pinfunction "-_-") (pintype "passive"))
      (node (ref "C31") (pin "2") (pinfunction "2_2") (pintype "passive"))
      (node (ref "C32") (pin "2") (pinfunction "2_2") (pintype "passive"))
      (node (ref "C33") (pin "1") (pinfunction "1_1") (pintype "passive"))
      (node (ref "C34") (pin "1") (pinfunction "1_1") (pintype "passive"))
      (node (ref "C35") (pin "1") (pinfunction "1_1") (pintype "passive"))
      (node (ref "C36") (pin "1") (pinfunction "1_1") (pintype "passive"))
      (node (ref "C37") (pin "1") (pinfunction "1_1") (pintype "passive"))
      (node (ref "C38") (pin "1") (pinfunction "1_1") (pintype "passive"))
      (node (ref "C39") (pin "2") (pinfunction "2_2") (pintype "passive"))
      (node (ref "C4") (pin "2") (pinfunction "2_2") (pintype "passive"))
      (node (ref "C41") (pin "2") (pinfunction "2_2") (pintype "passive"))
      (node (ref "C42") (pin "2") (pinfunction "2_2") (pintype "passive"))
      (node (ref "C43") (pin "2") (pinfunction "2_2") (pintype "passive"))
      (node (ref "C47") (pin "-") (pinfunction "-_-") (pintype "passive"))
      (node (ref "C48") (pin "-") (pinfunction "-_-") (pintype "passive"))
      (node (ref "C49") (pin "2") (pinfunction "2_2") (pintype "passive"))
      (node (ref "C5") (pin "-") (pinfunction "-_-") (pintype "passive"))
      (node (ref "C50") (pin "2") (pinfunction "2_2") (pintype "passive"))
      (node (ref "C52") (pin "-") (pinfunction "-_-") (pintype "passive"))
      (node (ref "C53") (pin "2") (pinfunction "2_2") (pintype "passive"))
      (node (ref "C54") (pin "-") (pinfunction "-_-") (pintype "passive"))
      (node (ref "C55") (pin "2") (pinfunction "2_2") (pintype "passive"))
      (node (ref "C56") (pin "-") (pinfunction "-_-") (pintype "passive"))
      (node (ref "C57") (pin "-") (pinfunction "-_-") (pintype "passive"))
      (node (ref "C58") (pin "2") (pinfunction "2_2") (pintype "passive"))
      (node (ref "C59") (pin "1") (pinfunction "1_1") (pintype "passive"))
      (node (ref "C60") (pin "1") (pinfunction "1_1") (pintype "passive"))
      (node (ref "C61") (pin "1") (pinfunction "1_1") (pintype "passive"))
      (node (ref "C62") (pin "1") (pinfunction "1_1") (pintype "passive"))
      (node (ref "C63") (pin "1") (pinfunction "1_1") (pintype "passive"))
      (node (ref "C64") (pin "1") (pinfunction "1_1") (pintype "passive"))
      (node (ref "C65") (pin "2") (pinfunction "2_2") (pintype "passive"))
      (node (ref "C66") (pin "2") (pinfunction "2_2") (pintype "passive"))
      (node (ref "C67") (pin "2") (pinfunction "2_2") (pintype "passive"))
      (node (ref "C68") (pin "2") (pinfunction "2_2") (pintype "passive"))
      (node (ref "C69") (pin "2") (pinfunction "2_2") (pintype "passive"))
      (node (ref "C7") (pin "-") (pinfunction "-_-") (pintype "passive"))
      (node (ref "C70") (pin "1") (pinfunction "1_1") (pintype "passive"))
      (node (ref "C71") (pin "1") (pinfunction "1_1") (pintype "passive"))
      (node (ref "C72") (pin "1") (pinfunction "1_1") (pintype "passive"))
      (node (ref "C73") (pin "1") (pinfunction "1_1") (pintype "passive"))
      (node (ref "C74") (pin "1") (pinfunction "1_1") (pintype "passive"))
      (node (ref "C75") (pin "1") (pinfunction "1_1") (pintype "passive"))
      (node (ref "C76") (pin "1") (pinfunction "1_1") (pintype "passive"))
      (node (ref "C77") (pin "1") (pinfunction "1_1") (pintype "passive"))
      (node (ref "C78") (pin "1") (pinfunction "1_1") (pintype "passive"))
      (node (ref "C79") (pin "1") (pinfunction "1_1") (pintype "passive"))
      (node (ref "C80") (pin "1") (pinfunction "1_1") (pintype "passive"))
      (node (ref "C81") (pin "1") (pinfunction "1_1") (pintype "passive"))
      (node (ref "C9") (pin "-") (pinfunction "-_-") (pintype "passive"))
      (node (ref "CAN") (pin "4") (pinfunction "4_4") (pintype "bidirectional"))
      (node (ref "D2") (pin "A") (pinfunction "A_A") (pintype "passive"))
      (node (ref "D5") (pin "A") (pinfunction "A_A") (pintype "passive"))
      (node (ref "DEBUG") (pin "1") (pinfunction "1_1") (pintype "passive"))
      (node (ref "DEBUG") (pin "3") (pinfunction "3_3") (pintype "passive"))
      (node (ref "DEBUG") (pin "5") (pinfunction "5_5") (pintype "passive"))
      (node (ref "FOTOCELULA") (pin "2") (pinfunction "2_2") (pintype "passive"))
      (node (ref "IC1") (pin "2") (pinfunction "GND_2") (pintype "power_in"))
      (node (ref "IC10") (pin "3") (pinfunction "GND_3") (pintype "bidirectional"))
      (node (ref "IC11") (pin "2") (pinfunction "VSS_2") (pintype "power_in"))
      (node (ref "IC12") (pin "2") (pinfunction "GND_2") (pintype "power_in"))
      (node (ref "IC12") (pin "6") (pinfunction "SENSE_6") (pintype "passive"))
      (node (ref "IC13") (pin "4") (pinfunction "V-_4") (pintype "power_in"))
      (node (ref "IC14") (pin "2") (pinfunction "GND_2") (pintype "power_in"))
      (node (ref "IC14") (pin "6") (pinfunction "SENSE_6") (pintype "passive"))
      (node (ref "IC15") (pin "2") (pinfunction "GND_2") (pintype "power_in"))
      (node (ref "IC15") (pin "6") (pinfunction "SENSE_6") (pintype "passive"))
      (node (ref "IC16") (pin "2") (pinfunction "GND_2") (pintype "power_in"))
      (node (ref "IC16") (pin "6") (pinfunction "SENSE_6") (pintype "passive"))
      (node (ref "IC17") (pin "6") (pinfunction "INH_6") (pintype "input"))
      (node (ref "IC17") (pin "7") (pinfunction "VEE_7") (pintype "power_in"))
      (node (ref "IC17") (pin "8") (pinfunction "GND_8") (pintype "power_in"))
      (node (ref "IC18") (pin "3") (pinfunction "GND_3") (pintype "bidirectional"))
      (node (ref "IC2") (pin "2") (pinfunction "GND_2") (pintype "power_in"))
      (node (ref "IC3") (pin "2") (pinfunction "GND_2") (pintype "power_in"))
      (node (ref "IC4") (pin "2") (pinfunction "GND_2") (pintype "power_in"))
      (node (ref "IC4") (pin "6") (pinfunction "SENSE_6") (pintype "passive"))
      (node (ref "IC5") (pin "4") (pinfunction "V-_4") (pintype "power_in"))
      (node (ref "IC6") (pin "4") (pinfunction "V-_4") (pintype "power_in"))
      (node (ref "IC7") (pin "4") (pinfunction "V-_4") (pintype "power_in"))
      (node (ref "IC8") (pin "4") (pinfunction "V-_4") (pintype "power_in"))
      (node (ref "IC9") (pin "26") (pinfunction "VSS_26") (pintype "power_in"))
      (node (ref "IC9") (pin "42") (pinfunction "AVSS_42") (pintype "power_in"))
      (node (ref "IC9") (pin "43") (pinfunction "VSS_43") (pintype "power_in"))
      (node (ref "IC9") (pin "56") (pinfunction "VSS_56") (pintype "power_in"))
      (node (ref "IC9") (pin "8") (pinfunction "VSS_8") (pintype "power_in"))
      (node (ref "ICSP") (pin "3") (pinfunction "GND_3") (pintype "passive"))
      (node (ref "R1") (pin "1") (pinfunction "1_1") (pintype "passive"))
      (node (ref "R10") (pin "1") (pinfunction "1_1") (pintype "passive"))
      (node (ref "R11") (pin "1") (pinfunction "1_1") (pintype "passive"))
      (node (ref "R2") (pin "1") (pinfunction "1_1") (pintype "passive"))
      (node (ref "R26") (pin "2") (pinfunction "2_2") (pintype "passive"))
      (node (ref "R31") (pin "2") (pinfunction "2_2") (pintype "passive"))
      (node (ref "R37") (pin "2") (pinfunction "2_2") (pintype "passive"))
      (node (ref "R4") (pin "1") (pinfunction "1_1") (pintype "passive"))
      (node (ref "R43") (pin "2") (pinfunction "2_2") (pintype "passive"))
      (node (ref "R46") (pin "2") (pinfunction "2_2") (pintype "passive"))
      (node (ref "R5") (pin "1") (pinfunction "1_1") (pintype "passive"))
      (node (ref "R58") (pin "1") (pinfunction "1_1") (pintype "passive"))
      (node (ref "R60") (pin "1") (pinfunction "1_1") (pintype "passive"))
      (node (ref "R61") (pin "1") (pinfunction "1_1") (pintype "passive"))
      (node (ref "R62") (pin "1") (pinfunction "1_1") (pintype "passive"))
      (node (ref "R63") (pin "1") (pinfunction "1_1") (pintype "passive"))
      (node (ref "R66") (pin "2") (pinfunction "2_2") (pintype "passive"))
      (node (ref "R68") (pin "2") (pinfunction "2_2") (pintype "passive"))
      (node (ref "R70") (pin "2") (pinfunction "2_2") (pintype "passive"))
      (node (ref "R71") (pin "2") (pinfunction "2_2") (pintype "passive"))
      (node (ref "R73") (pin "1") (pinfunction "1_1") (pintype "passive"))
      (node (ref "R77") (pin "2") (pinfunction "2_2") (pintype "passive"))
      (node (ref "R8") (pin "1") (pinfunction "1_1") (pintype "passive"))
      (node (ref "R80") (pin "2") (pinfunction "2_2") (pintype "passive"))
      (node (ref "R81") (pin "2") (pinfunction "2_2") (pintype "passive"))
      (node (ref "R83") (pin "2") (pinfunction "2_2") (pintype "passive"))
      (node (ref "S12") (pin "N") (pinfunction "N_N") (pintype "power_in"))
      (node (ref "S16") (pin "N") (pinfunction "N_N") (pintype "power_in"))
      (node (ref "S20") (pin "N") (pinfunction "N_N") (pintype "power_in"))
      (node (ref "S24") (pin "N") (pinfunction "N_N") (pintype "power_in"))
      (node (ref "S4") (pin "N") (pinfunction "N_N") (pintype "power_in"))
      (node (ref "S8") (pin "N") (pinfunction "N_N") (pintype "power_in"))
      (node (ref "SERIAL") (pin "4") (pinfunction "4_4") (pintype "bidirectional"))
      (node (ref "SJ1") (pin "1") (pinfunction "1_1") (pintype "passive"))
      (node (ref "SJ2") (pin "1") (pinfunction "1_1") (pintype "passive"))
      (node (ref "SJ6") (pin "1") (pinfunction "1_1") (pintype "passive"))
      (node (ref "U1") (pin "1") (pinfunction "GND_1") (pintype "power_in"))
      (node (ref "U2") (pin "1") (pinfunction "GND_1") (pintype "power_in"))
      (node (ref "U3") (pin "10") (pinfunction "GND/HEATSINK_10") (pintype "power_in"))
      (node (ref "U3") (pin "16") (pinfunction "AGND_16") (pintype "power_in"))
      (node (ref "U3") (pin "21") (pinfunction "EPAD_21") (pintype "power_in"))
      (node (ref "U4") (pin "1") (pinfunction "GND_1") (pintype "power_in"))
      (node (ref "U5") (pin "26") (pinfunction "PGND_26") (pintype "passive"))
      (node (ref "U5") (pin "29") (pinfunction "EP_29") (pintype "passive"))
      (node (ref "U6") (pin "4") (pinfunction "AGND_4") (pintype "passive"))
      (node (ref "U6") (pin "5") (pinfunction "PGND_5") (pintype "passive"))
      (node (ref "V_BUS") (pin "10") (pinfunction "10_10") (pintype "passive"))
      (node (ref "V_BUS") (pin "12") (pinfunction "12_12") (pintype "passive"))
      (node (ref "V_BUS") (pin "14") (pinfunction "14_14") (pintype "passive"))
      (node (ref "V_BUS") (pin "16") (pinfunction "16_16") (pintype "passive"))
      (node (ref "V_BUS") (pin "18") (pinfunction "18_18") (pintype "passive"))
      (node (ref "V_BUS") (pin "2") (pinfunction "2_2") (pintype "passive"))
      (node (ref "V_BUS") (pin "20") (pinfunction "20_20") (pintype "passive"))
      (node (ref "V_BUS") (pin "22") (pinfunction "22_22") (pintype "passive"))
      (node (ref "V_BUS") (pin "24") (pinfunction "24_24") (pintype "passive"))
      (node (ref "V_BUS") (pin "26") (pinfunction "26_26") (pintype "passive"))
      (node (ref "V_BUS") (pin "28") (pinfunction "28_28") (pintype "passive"))
      (node (ref "V_BUS") (pin "30") (pinfunction "30_30") (pintype "passive"))
      (node (ref "V_BUS") (pin "32") (pinfunction "32_32") (pintype "passive"))
      (node (ref "V_BUS") (pin "34") (pinfunction "34_34") (pintype "passive"))
      (node (ref "V_BUS") (pin "36") (pinfunction "36_36") (pintype "passive"))
      (node (ref "V_BUS") (pin "38") (pinfunction "38_38") (pintype "passive"))
      (node (ref "V_BUS") (pin "4") (pinfunction "4_4") (pintype "passive"))
      (node (ref "V_BUS") (pin "40") (pinfunction "40_40") (pintype "passive"))
      (node (ref "V_BUS") (pin "6") (pinfunction "6_6") (pintype "passive"))
      (node (ref "V_BUS") (pin "8") (pinfunction "8_8") (pintype "passive"))
      (node (ref "X1") (pin "3") (pinfunction "3_3") (pintype "passive"))
      (node (ref "X1") (pin "4") (pinfunction "4_4") (pintype "passive"))
      (node (ref "X1") (pin "7") (pinfunction "7_7") (pintype "passive"))
      (node (ref "X1") (pin "8") (pinfunction "8_8") (pintype "passive"))
    )
    (net (code "37") (name "LED1") (class "Default")
      (node (ref "IC9") (pin "49") (pinfunction "RC1/SOSCI_49") (pintype "bidirectional"))
      (node (ref "LED3") (pin "C") (pinfunction "C_C") (pintype "passive"))
    )
    (net (code "38") (name "LED2") (class "Default")
      (node (ref "IC9") (pin "50") (pinfunction "RC2/T1G/CCP2_50") (pintype "bidirectional"))
      (node (ref "LED2") (pin "C") (pinfunction "C_C") (pintype "passive"))
    )
    (net (code "39") (name "LED3") (class "Default")
      (node (ref "IC9") (pin "51") (pinfunction "RC3/REFO/SCL/SCK_51") (pintype "bidirectional"))
      (node (ref "LED1") (pin "C") (pinfunction "C_C") (pintype "passive"))
    )
    (net (code "40") (name "MUX_AD") (class "Default")
      (node (ref "BACKUP") (pin "23") (pinfunction "23_23") (pintype "passive"))
      (node (ref "BACKUP1") (pin "23") (pinfunction "23_23") (pintype "passive"))
      (node (ref "IC17") (pin "3") (pinfunction "X_3") (pintype "bidirectional"))
      (node (ref "IC9") (pin "14") (pinfunction "RB1/AN8/CTDIN/INT1_14") (pintype "bidirectional"))
    )
    (net (code "41") (name "Net-(C3-Pad2)") (class "Default")
      (node (ref "C3") (pin "2") (pinfunction "2_2") (pintype "passive"))
      (node (ref "R1") (pin "2") (pinfunction "2_2") (pintype "passive"))
    )
    (net (code "42") (name "Net-(C4-Pad1)") (class "Default")
      (node (ref "C4") (pin "1") (pinfunction "1_1") (pintype "passive"))
      (node (ref "R3") (pin "1") (pinfunction "1_1") (pintype "passive"))
    )
    (net (code "43") (name "Net-(C25-Pad2)") (class "Default")
      (node (ref "C25") (pin "2") (pinfunction "2_2") (pintype "passive"))
      (node (ref "R47") (pin "1") (pinfunction "1_1") (pintype "passive"))
      (node (ref "R53") (pin "2") (pinfunction "2_2") (pintype "passive"))
    )
    (net (code "44") (name "Net-(C40-Pad1)") (class "Default")
      (node (ref "C40") (pin "1") (pinfunction "1_1") (pintype "passive"))
      (node (ref "R60") (pin "2") (pinfunction "2_2") (pintype "passive"))
    )
    (net (code "45") (name "Net-(C44-Pad1)") (class "Default")
      (node (ref "C44") (pin "1") (pinfunction "1_1") (pintype "passive"))
      (node (ref "R61") (pin "2") (pinfunction "2_2") (pintype "passive"))
    )
    (net (code "46") (name "Net-(C45-Pad1)") (class "Default")
      (node (ref "C45") (pin "1") (pinfunction "1_1") (pintype "passive"))
      (node (ref "R62") (pin "2") (pinfunction "2_2") (pintype "passive"))
    )
    (net (code "47") (name "Net-(C73-Pad2)") (class "Default")
      (node (ref "C73") (pin "2") (pinfunction "2_2") (pintype "passive"))
      (node (ref "C76") (pin "2") (pinfunction "2_2") (pintype "passive"))
      (node (ref "C78") (pin "2") (pinfunction "2_2") (pintype "passive"))
      (node (ref "C80") (pin "2") (pinfunction "2_2") (pintype "passive"))
      (node (ref "R54") (pin "2") (pinfunction "2_2") (pintype "passive"))
      (node (ref "R82") (pin "1") (pinfunction "1_1") (pintype "passive"))
    )
    (net (code "48") (name "Net-(D8-PadA)") (class "Default")
      (node (ref "D8") (pin "A") (pinfunction "A_A") (pintype "passive"))
      (node (ref "S1") (pin "P") (pinfunction "P_P") (pintype "power_in"))
    )
    (net (code "49") (name "Net-(D9-PadA)") (class "Default")
      (node (ref "D9") (pin "A") (pinfunction "A_A") (pintype "passive"))
      (node (ref "S5") (pin "P") (pinfunction "P_P") (pintype "power_in"))
    )
    (net (code "50") (name "Net-(D10-PadA)") (class "Default")
      (node (ref "D10") (pin "A") (pinfunction "A_A") (pintype "passive"))
      (node (ref "S9") (pin "P") (pinfunction "P_P") (pintype "power_in"))
    )
    (net (code "51") (name "Net-(D11-PadA)") (class "Default")
      (node (ref "D11") (pin "A") (pinfunction "A_A") (pintype "passive"))
      (node (ref "S13") (pin "P") (pinfunction "P_P") (pintype "power_in"))
    )
    (net (code "52") (name "Net-(D12-PadA)") (class "Default")
      (node (ref "D12") (pin "A") (pinfunction "A_A") (pintype "passive"))
      (node (ref "S17") (pin "P") (pinfunction "P_P") (pintype "power_in"))
    )
    (net (code "53") (name "Net-(D13-PadA)") (class "Default")
      (node (ref "D13") (pin "A") (pinfunction "A_A") (pintype "passive"))
      (node (ref "S21") (pin "P") (pinfunction "P_P") (pintype "power_in"))
    )
    (net (code "54") (name "Net-(IC1-GATE)") (class "Default")
      (node (ref "IC1") (pin "5") (pinfunction "GATE_5") (pintype "passive"))
      (node (ref "R12") (pin "2") (pinfunction "2_2") (pintype "passive"))
      (node (ref "T1") (pin "4") (pinfunction "G_4") (pintype "passive"))
      (node (ref "T2") (pin "2") (pinfunction "G_2") (pintype "passive"))
    )
    (net (code "55") (name "Net-(IC1-STAT)") (class "Default")
      (node (ref "IC1") (pin "4") (pinfunction "STAT_4") (pintype "passive"))
      (node (ref "R13") (pin "2") (pinfunction "2_2") (pintype "passive"))
      (node (ref "T1") (pin "2") (pinfunction "G_2") (pintype "passive"))
      (node (ref "T2") (pin "4") (pinfunction "G_4") (pintype "passive"))
    )
    (net (code "56") (name "Net-(IC2-GATE)") (class "Default")
      (node (ref "IC2") (pin "5") (pinfunction "GATE_5") (pintype "passive"))
      (node (ref "R30") (pin "2") (pinfunction "2_2") (pintype "passive"))
      (node (ref "T3") (pin "4") (pinfunction "G_4") (pintype "passive"))
      (node (ref "T4") (pin "2") (pinfunction "G_2") (pintype "passive"))
    )
    (net (code "57") (name "Net-(IC2-STAT)") (class "Default")
      (node (ref "IC2") (pin "4") (pinfunction "STAT_4") (pintype "passive"))
      (node (ref "R16") (pin "2") (pinfunction "2_2") (pintype "passive"))
      (node (ref "T3") (pin "2") (pinfunction "G_2") (pintype "passive"))
      (node (ref "T4") (pin "4") (pinfunction "G_4") (pintype "passive"))
    )
    (net (code "58") (name "Net-(IC3-GATE)") (class "Default")
      (node (ref "IC3") (pin "5") (pinfunction "GATE_5") (pintype "passive"))
      (node (ref "R76") (pin "2") (pinfunction "2_2") (pintype "passive"))
      (node (ref "T5") (pin "4") (pinfunction "G_4") (pintype "passive"))
      (node (ref "T6") (pin "2") (pinfunction "G_2") (pintype "passive"))
    )
    (net (code "59") (name "Net-(IC3-STAT)") (class "Default")
      (node (ref "IC3") (pin "4") (pinfunction "STAT_4") (pintype "passive"))
      (node (ref "R19") (pin "2") (pinfunction "2_2") (pintype "passive"))
      (node (ref "T5") (pin "2") (pinfunction "G_2") (pintype "passive"))
      (node (ref "T6") (pin "4") (pinfunction "G_4") (pintype "passive"))
    )
    (net (code "60") (name "Net-(IC4-GATE)") (class "Default")
      (node (ref "IC4") (pin "5") (pinfunction "GATE_5") (pintype "passive"))
      (node (ref "Q2") (pin "1") (pinfunction "G_1") (pintype "passive"))
    )
    (net (code "61") (name "Net-(IC5A-+IN)") (class "Default")
      (node (ref "IC5") (pin "3") (pinfunction "+IN_3") (pintype "input"))
      (node (ref "R21") (pin "1") (pinfunction "1_1") (pintype "passive"))
      (node (ref "R26") (pin "1") (pinfunction "1_1") (pintype "passive"))
    )
    (net (code "62") (name "Net-(IC5A--IN)") (class "Default")
      (node (ref "IC5") (pin "2") (pinfunction "-IN_2") (pintype "input"))
      (node (ref "R28") (pin "1") (pinfunction "1_1") (pintype "passive"))
      (node (ref "R29") (pin "2") (pinfunction "2_2") (pintype "passive"))
    )
    (net (code "63") (name "Net-(IC5B-+IN)") (class "Default")
      (node (ref "IC5") (pin "5") (pinfunction "+IN_5") (pintype "input"))
      (node (ref "R20") (pin "2") (pinfunction "2_2") (pintype "passive"))
      (node (ref "R31") (pin "1") (pinfunction "1_1") (pintype "passive"))
    )
    (net (code "64") (name "Net-(IC6A-+IN)") (class "Default")
      (node (ref "IC6") (pin "3") (pinfunction "+IN_3") (pintype "input"))
      (node (ref "R33") (pin "1") (pinfunction "1_1") (pintype "passive"))
      (node (ref "R71") (pin "1") (pinfunction "1_1") (pintype "passive"))
    )
    (net (code "65") (name "Net-(IC6A--IN)") (class "Default")
      (node (ref "IC6") (pin "2") (pinfunction "-IN_2") (pintype "input"))
      (node (ref "R34") (pin "1") (pinfunction "1_1") (pintype "passive"))
      (node (ref "R35") (pin "2") (pinfunction "2_2") (pintype "passive"))
    )
    (net (code "66") (name "Net-(IC6B-+IN)") (class "Default")
      (node (ref "IC6") (pin "5") (pinfunction "+IN_5") (pintype "input"))
      (node (ref "R75") (pin "2") (pinfunction "2_2") (pintype "passive"))
    )
    (net (code "67") (name "Net-(IC6B--IN)") (class "Default")
      (node (ref "IC6") (pin "6") (pinfunction "-IN_6") (pintype "input"))
      (node (ref "R72") (pin "1") (pinfunction "1_1") (pintype "passive"))
      (node (ref "R73") (pin "2") (pinfunction "2_2") (pintype "passive"))
    )
    (net (code "68") (name "Net-(IC7A-+IN)") (class "Default")
      (node (ref "IC7") (pin "3") (pinfunction "+IN_3") (pintype "input"))
      (node (ref "R11") (pin "2") (pinfunction "2_2") (pintype "passive"))
      (node (ref "R22") (pin "1") (pinfunction "1_1") (pintype "passive"))
    )
    (net (code "69") (name "Net-(IC7A--IN)") (class "Default")
      (node (ref "IC7") (pin "2") (pinfunction "-IN_2") (pintype "input"))
      (node (ref "R23") (pin "1") (pinfunction "1_1") (pintype "passive"))
      (node (ref "R24") (pin "2") (pinfunction "2_2") (pintype "passive"))
    )
    (net (code "70") (name "Net-(IC7B-+IN)") (class "Default")
      (node (ref "IC7") (pin "5") (pinfunction "+IN_5") (pintype "input"))
      (node (ref "R25") (pin "2") (pinfunction "2_2") (pintype "passive"))
      (node (ref "R46") (pin "1") (pinfunction "1_1") (pintype "passive"))
    )
    (net (code "71") (name "Net-(IC8A-+IN)") (class "Default")
      (node (ref "IC8") (pin "3") (pinfunction "+IN_3") (pintype "input"))
      (node (ref "R39") (pin "1") (pinfunction "1_1") (pintype "passive"))
      (node (ref "R77") (pin "1") (pinfunction "1_1") (pintype "passive"))
    )
    (net (code "72") (name "Net-(IC8A--IN)") (class "Default")
      (node (ref "IC8") (pin "2") (pinfunction "-IN_2") (pintype "input"))
      (node (ref "R40") (pin "1") (pinfunction "1_1") (pintype "passive"))
      (node (ref "R41") (pin "2") (pinfunction "2_2") (pintype "passive"))
    )
    (net (code "73") (name "Net-(IC8B-+IN)") (class "Default")
      (node (ref "IC8") (pin "5") (pinfunction "+IN_5") (pintype "input"))
      (node (ref "R42") (pin "2") (pinfunction "2_2") (pintype "passive"))
      (node (ref "R43") (pin "1") (pinfunction "1_1") (pintype "passive"))
    )
    (net (code "74") (name "Net-(IC9-VDDCORE{slash}VCAP)") (class "Default")
      (node (ref "C26") (pin "2") (pinfunction "2_2") (pintype "passive"))
      (node (ref "IC9") (pin "33") (pinfunction "VDDCORE/VCAP_33") (pintype "bidirectional"))
    )
    (net (code "75") (name "Net-(IC11-CANH)") (class "Default")
      (node (ref "CAN") (pin "2") (pinfunction "2_2") (pintype "bidirectional"))
      (node (ref "IC11") (pin "7") (pinfunction "CANH_7") (pintype "input"))
      (node (ref "R64") (pin "2") (pinfunction "2_2") (pintype "passive"))
    )
    (net (code "76") (name "Net-(IC11-CANL)") (class "Default")
      (node (ref "CAN") (pin "3") (pinfunction "3_3") (pintype "bidirectional"))
      (node (ref "IC11") (pin "6") (pinfunction "CANL_6") (pintype "input"))
      (node (ref "JP2") (pin "1") (pinfunction "1_1") (pintype "passive"))
    )
    (net (code "77") (name "Net-(IC11-RS)") (class "Default")
      (node (ref "IC11") (pin "8") (pinfunction "RS_8") (pintype "input"))
      (node (ref "R63") (pin "2") (pinfunction "2_2") (pintype "passive"))
    )
    (net (code "78") (name "Net-(IC12-GATE)") (class "Default")
      (node (ref "IC12") (pin "5") (pinfunction "GATE_5") (pintype "passive"))
      (node (ref "Q4") (pin "1") (pinfunction "G_1") (pintype "passive"))
    )
    (net (code "79") (name "Net-(IC13A-+IN)") (class "Default")
      (node (ref "IC13") (pin "3") (pinfunction "+IN_3") (pintype "input"))
      (node (ref "R54") (pin "1") (pinfunction "1_1") (pintype "passive"))
      (node (ref "R81") (pin "1") (pinfunction "1_1") (pintype "passive"))
    )
    (net (code "80") (name "Net-(IC13A--IN)") (class "Default")
      (node (ref "IC13") (pin "2") (pinfunction "-IN_2") (pintype "input"))
      (node (ref "R55") (pin "1") (pinfunction "1_1") (pintype "passive"))
      (node (ref "R78") (pin "2") (pinfunction "2_2") (pintype "passive"))
    )
    (net (code "81") (name "Net-(IC13B-+IN)") (class "Default")
      (node (ref "IC13") (pin "5") (pinfunction "+IN_5") (pintype "input"))
      (node (ref "R79") (pin "2") (pinfunction "2_2") (pintype "passive"))
      (node (ref "R80") (pin "1") (pinfunction "1_1") (pintype "passive"))
    )
    (net (code "82") (name "Net-(IC14-GATE)") (class "Default")
      (node (ref "IC14") (pin "5") (pinfunction "GATE_5") (pintype "passive"))
      (node (ref "Q5") (pin "1") (pinfunction "G_1") (pintype "passive"))
    )
    (net (code "83") (name "Net-(IC15-GATE)") (class "Default")
      (node (ref "IC15") (pin "5") (pinfunction "GATE_5") (pintype "passive"))
      (node (ref "Q6") (pin "1") (pinfunction "G_1") (pintype "passive"))
    )
    (net (code "84") (name "Net-(IC16-GATE)") (class "Default")
      (node (ref "IC16") (pin "5") (pinfunction "GATE_5") (pintype "passive"))
      (node (ref "Q7") (pin "1") (pinfunction "G_1") (pintype "passive"))
    )
    (net (code "85") (name "Net-(IC17A-X7)") (class "Default")
      (node (ref "IC17") (pin "4") (pinfunction "X7_4") (pintype "bidirectional"))
      (node (ref "SJ6") (pin "2") (pinfunction "2_2") (pintype "passive"))
    )
    (net (code "86") (name "Net-(IC18-VOUT)") (class "Default")
      (node (ref "IC18") (pin "2") (pinfunction "VOUT_2") (pintype "bidirectional"))
      (node (ref "X1") (pin "6") (pinfunction "6_6") (pintype "passive"))
    )
    (net (code "87") (name "Net-(JP2-Pad2)") (class "Default")
      (node (ref "JP2") (pin "2") (pinfunction "2_2") (pintype "passive"))
      (node (ref "R64") (pin "1") (pinfunction "1_1") (pintype "passive"))
    )
    (net (code "88") (name "Net-(LED1-PadA)") (class "Default")
      (node (ref "LED1") (pin "A") (pinfunction "A_A") (pintype "passive"))
      (node (ref "R48") (pin "2") (pinfunction "2_2") (pintype "passive"))
    )
    (net (code "89") (name "Net-(LED2-PadA)") (class "Default")
      (node (ref "LED2") (pin "A") (pinfunction "A_A") (pintype "passive"))
      (node (ref "R49") (pin "2") (pinfunction "2_2") (pintype "passive"))
    )
    (net (code "90") (name "Net-(LED3-PadA)") (class "Default")
      (node (ref "LED3") (pin "A") (pinfunction "A_A") (pintype "passive"))
      (node (ref "R50") (pin "2") (pinfunction "2_2") (pintype "passive"))
    )
    (net (code "91") (name "Net-(LED4-PadA)") (class "Default")
      (node (ref "LED4") (pin "A") (pinfunction "A_A") (pintype "passive"))
      (node (ref "R85") (pin "2") (pinfunction "2_2") (pintype "passive"))
    )
    (net (code "92") (name "Net-(LED5-PadA)") (class "Default")
      (node (ref "LED5") (pin "A") (pinfunction "A_A") (pintype "passive"))
      (node (ref "R86") (pin "2") (pinfunction "2_2") (pintype "passive"))
    )
    (net (code "93") (name "Net-(Q1-DRAIN)") (class "Default")
      (node (ref "D6") (pin "A") (pinfunction "A_A") (pintype "passive"))
      (node (ref "L1") (pin "2") (pinfunction "2_2") (pintype "passive"))
      (node (ref "Q1") (pin "5") (pinfunction "DRAIN_5") (pintype "passive"))
    )
    (net (code "94") (name "Net-(Q1-GATE)") (class "Default")
      (node (ref "Q1") (pin "4") (pinfunction "GATE_4") (pintype "passive"))
      (node (ref "U6") (pin "6") (pinfunction "DR_6") (pintype "passive"))
    )
    (net (code "95") (name "Net-(Q1-SOURCE)") (class "Default")
      (node (ref "Q1") (pin "1") (pinfunction "SOURCE_1") (pintype "passive"))
      (node (ref "R4") (pin "2") (pinfunction "2_2") (pintype "passive"))
    )
    (net (code "96") (name "Net-(R36-Pad2)") (class "Default")
      (node (ref "R36") (pin "2") (pinfunction "2_2") (pintype "passive"))
      (node (ref "R37") (pin "1") (pinfunction "1_1") (pintype "passive"))
      (node (ref "R74") (pin "1") (pinfunction "1_1") (pintype "passive"))
    )
    (net (code "97") (name "Net-(R74-Pad2)") (class "Default")
      (node (ref "R74") (pin "2") (pinfunction "2_2") (pintype "passive"))
      (node (ref "R75") (pin "1") (pinfunction "1_1") (pintype "passive"))
    )
    (net (code "98") (name "Net-(S1-PadN)") (class "Default")
      (node (ref "S1") (pin "N") (pinfunction "N_N") (pintype "power_in"))
      (node (ref "S2") (pin "P") (pinfunction "P_P") (pintype "power_in"))
    )
    (net (code "99") (name "Net-(S2-PadN)") (class "Default")
      (node (ref "S2") (pin "N") (pinfunction "N_N") (pintype "power_in"))
      (node (ref "S3") (pin "P") (pinfunction "P_P") (pintype "power_in"))
    )
    (net (code "100") (name "Net-(S3-PadN)") (class "Default")
      (node (ref "S3") (pin "N") (pinfunction "N_N") (pintype "power_in"))
      (node (ref "S4") (pin "P") (pinfunction "P_P") (pintype "power_in"))
    )
    (net (code "101") (name "Net-(S5-PadN)") (class "Default")
      (node (ref "S5") (pin "N") (pinfunction "N_N") (pintype "power_in"))
      (node (ref "S6") (pin "P") (pinfunction "P_P") (pintype "power_in"))
    )
    (net (code "102") (name "Net-(S6-PadN)") (class "Default")
      (node (ref "S6") (pin "N") (pinfunction "N_N") (pintype "power_in"))
      (node (ref "S7") (pin "P") (pinfunction "P_P") (pintype "power_in"))
    )
    (net (code "103") (name "Net-(S7-PadN)") (class "Default")
      (node (ref "S7") (pin "N") (pinfunction "N_N") (pintype "power_in"))
      (node (ref "S8") (pin "P") (pinfunction "P_P") (pintype "power_in"))
    )
    (net (code "104") (name "Net-(S10-PadN)") (class "Default")
      (node (ref "S10") (pin "N") (pinfunction "N_N") (pintype "power_in"))
      (node (ref "S11") (pin "P") (pinfunction "P_P") (pintype "power_in"))
    )
    (net (code "105") (name "Net-(S10-PadP)") (class "Default")
      (node (ref "S10") (pin "P") (pinfunction "P_P") (pintype "power_in"))
      (node (ref "S9") (pin "N") (pinfunction "N_N") (pintype "power_in"))
    )
    (net (code "106") (name "Net-(S11-PadN)") (class "Default")
      (node (ref "S11") (pin "N") (pinfunction "N_N") (pintype "power_in"))
      (node (ref "S12") (pin "P") (pinfunction "P_P") (pintype "power_in"))
    )
    (net (code "107") (name "Net-(S13-PadN)") (class "Default")
      (node (ref "S13") (pin "N") (pinfunction "N_N") (pintype "power_in"))
      (node (ref "S14") (pin "P") (pinfunction "P_P") (pintype "power_in"))
    )
    (net (code "108") (name "Net-(S14-PadN)") (class "Default")
      (node (ref "S14") (pin "N") (pinfunction "N_N") (pintype "power_in"))
      (node (ref "S15") (pin "P") (pinfunction "P_P") (pintype "power_in"))
    )
    (net (code "109") (name "Net-(S15-PadN)") (class "Default")
      (node (ref "S15") (pin "N") (pinfunction "N_N") (pintype "power_in"))
      (node (ref "S16") (pin "P") (pinfunction "P_P") (pintype "power_in"))
    )
    (net (code "110") (name "Net-(S17-PadN)") (class "Default")
      (node (ref "S17") (pin "N") (pinfunction "N_N") (pintype "power_in"))
      (node (ref "S18") (pin "P") (pinfunction "P_P") (pintype "power_in"))
    )
    (net (code "111") (name "Net-(S18-PadN)") (class "Default")
      (node (ref "S18") (pin "N") (pinfunction "N_N") (pintype "power_in"))
      (node (ref "S19") (pin "P") (pinfunction "P_P") (pintype "power_in"))
    )
    (net (code "112") (name "Net-(S19-PadN)") (class "Default")
      (node (ref "S19") (pin "N") (pinfunction "N_N") (pintype "power_in"))
      (node (ref "S20") (pin "P") (pinfunction "P_P") (pintype "power_in"))
    )
    (net (code "113") (name "Net-(S21-PadN)") (class "Default")
      (node (ref "S21") (pin "N") (pinfunction "N_N") (pintype "power_in"))
      (node (ref "S22") (pin "P") (pinfunction "P_P") (pintype "power_in"))
    )
    (net (code "114") (name "Net-(S22-PadN)") (class "Default")
      (node (ref "S22") (pin "N") (pinfunction "N_N") (pintype "power_in"))
      (node (ref "S23") (pin "P") (pinfunction "P_P") (pintype "power_in"))
    )
    (net (code "115") (name "Net-(S23-PadN)") (class "Default")
      (node (ref "S23") (pin "N") (pinfunction "N_N") (pintype "power_in"))
      (node (ref "S24") (pin "P") (pinfunction "P_P") (pintype "power_in"))
    )
    (net (code "116") (name "Net-(T1A-S)") (class "Default")
      (node (ref "R13") (pin "1") (pinfunction "1_1") (pintype "passive"))
      (node (ref "T1") (pin "1") (pinfunction "S_1") (pintype "passive"))
      (node (ref "T2") (pin "3") (pinfunction "S_3") (pintype "passive"))
    )
    (net (code "117") (name "Net-(T1B-S)") (class "Default")
      (node (ref "R12") (pin "1") (pinfunction "1_1") (pintype "passive"))
      (node (ref "T1") (pin "3") (pinfunction "S_3") (pintype "passive"))
      (node (ref "T2") (pin "1") (pinfunction "S_1") (pintype "passive"))
    )
    (net (code "118") (name "Net-(T3A-S)") (class "Default")
      (node (ref "R16") (pin "1") (pinfunction "1_1") (pintype "passive"))
      (node (ref "T3") (pin "1") (pinfunction "S_1") (pintype "passive"))
      (node (ref "T4") (pin "3") (pinfunction "S_3") (pintype "passive"))
    )
    (net (code "119") (name "Net-(T3B-S)") (class "Default")
      (node (ref "R30") (pin "1") (pinfunction "1_1") (pintype "passive"))
      (node (ref "T3") (pin "3") (pinfunction "S_3") (pintype "passive"))
      (node (ref "T4") (pin "1") (pinfunction "S_1") (pintype "passive"))
    )
    (net (code "120") (name "Net-(T5A-S)") (class "Default")
      (node (ref "R19") (pin "1") (pinfunction "1_1") (pintype "passive"))
      (node (ref "T5") (pin "1") (pinfunction "S_1") (pintype "passive"))
      (node (ref "T6") (pin "3") (pinfunction "S_3") (pintype "passive"))
    )
    (net (code "121") (name "Net-(T5B-S)") (class "Default")
      (node (ref "R76") (pin "1") (pinfunction "1_1") (pintype "passive"))
      (node (ref "T5") (pin "3") (pinfunction "S_3") (pintype "passive"))
      (node (ref "T6") (pin "1") (pinfunction "S_1") (pintype "passive"))
    )
    (net (code "122") (name "Net-(U1-EN)") (class "Default")
      (node (ref "SJ3") (pin "1") (pinfunction "1_1") (pintype "passive"))
      (node (ref "U1") (pin "5") (pinfunction "EN_5") (pintype "input"))
    )
    (net (code "123") (name "Net-(U1-SW)") (class "Default")
      (node (ref "C6") (pin "2") (pinfunction "2_2") (pintype "passive"))
      (node (ref "L3") (pin "1") (pinfunction "1_1") (pintype "passive"))
      (node (ref "U1") (pin "2") (pinfunction "SW_2") (pintype "power_in"))
    )
    (net (code "124") (name "Net-(U1-VBST)") (class "Default")
      (node (ref "C6") (pin "1") (pinfunction "1_1") (pintype "passive"))
      (node (ref "U1") (pin "6") (pinfunction "VBST_6") (pintype "power_in"))
    )
    (net (code "125") (name "Net-(U1-VFB)") (class "Default")
      (node (ref "R7") (pin "1") (pinfunction "1_1") (pintype "passive"))
      (node (ref "R8") (pin "2") (pinfunction "2_2") (pintype "passive"))
      (node (ref "U1") (pin "4") (pinfunction "VFB_4") (pintype "input"))
    )
    (net (code "126") (name "Net-(U2-EN)") (class "Default")
      (node (ref "SJ4") (pin "1") (pinfunction "1_1") (pintype "passive"))
      (node (ref "U2") (pin "5") (pinfunction "EN_5") (pintype "input"))
    )
    (net (code "127") (name "Net-(U2-SW)") (class "Default")
      (node (ref "C8") (pin "2") (pinfunction "2_2") (pintype "passive"))
      (node (ref "L2") (pin "1") (pinfunction "1_1") (pintype "passive"))
      (node (ref "U2") (pin "2") (pinfunction "SW_2") (pintype "power_in"))
    )
    (net (code "128") (name "Net-(U2-VBST)") (class "Default")
      (node (ref "C8") (pin "1") (pinfunction "1_1") (pintype "passive"))
      (node (ref "U2") (pin "6") (pinfunction "VBST_6") (pintype "power_in"))
    )
    (net (code "129") (name "Net-(U2-VFB)") (class "Default")
      (node (ref "R10") (pin "2") (pinfunction "2_2") (pintype "passive"))
      (node (ref "R9") (pin "1") (pinfunction "1_1") (pintype "passive"))
      (node (ref "U2") (pin "4") (pinfunction "VFB_4") (pintype "input"))
    )
    (net (code "130") (name "Net-(U3-APG{slash}THERM)") (class "Default")
      (node (ref "R83") (pin "1") (pinfunction "1_1") (pintype "passive"))
      (node (ref "R84") (pin "2") (pinfunction "2_2") (pintype "passive"))
      (node (ref "SJ7") (pin "2") (pinfunction "2_2") (pintype "passive"))
      (node (ref "U3") (pin "7") (pinfunction "APG/THERM_7") (pintype "input"))
    )
    (net (code "131") (name "Net-(U3-CR)") (class "Default")
      (node (ref "C23") (pin "2") (pinfunction "2_2") (pintype "passive"))
      (node (ref "R84") (pin "1") (pinfunction "1_1") (pintype "passive"))
      (node (ref "U3") (pin "12") (pinfunction "CR_12") (pintype "input"))
    )
    (net (code "132") (name "Net-(U3-IN)") (class "Default")
      (node (ref "R45") (pin "2") (pinfunction "2_2") (pintype "passive"))
      (node (ref "U3") (pin "2") (pinfunction "IN_2_2") (pintype "input"))
      (node (ref "U3") (pin "3") (pinfunction "IN_3") (pintype "input"))
      (node (ref "U3") (pin "5") (pinfunction "ISNS_5") (pintype "input"))
    )
    (net (code "133") (name "Net-(U3-STAT1)") (class "Default")
      (node (ref "LED5") (pin "C") (pinfunction "C_C") (pintype "passive"))
      (node (ref "U3") (pin "14") (pinfunction "STAT1_14") (pintype "output"))
    )
    (net (code "134") (name "Net-(U3-STAT2)") (class "Default")
      (node (ref "LED4") (pin "C") (pinfunction "C_C") (pintype "passive"))
      (node (ref "U3") (pin "15") (pinfunction "STAT2_15") (pintype "output"))
    )
    (net (code "135") (name "Net-(U3-TMRSEL)") (class "Default")
      (node (ref "SJ2") (pin "2") (pinfunction "2_2") (pintype "passive"))
      (node (ref "U3") (pin "13") (pinfunction "TMRSEL_13") (pintype "input"))
    )
    (net (code "136") (name "Net-(U3-VSEL)") (class "Default")
      (node (ref "SJ1") (pin "2") (pinfunction "2_2") (pintype "passive"))
      (node (ref "U3") (pin "9") (pinfunction "VSEL_9") (pintype "input"))
    )
    (net (code "137") (name "Net-(U4-EN)") (class "Default")
      (node (ref "SJ5") (pin "1") (pinfunction "1_1") (pintype "passive"))
      (node (ref "U4") (pin "5") (pinfunction "EN_5") (pintype "input"))
    )
    (net (code "138") (name "Net-(U4-SW)") (class "Default")
      (node (ref "C28") (pin "2") (pinfunction "2_2") (pintype "passive"))
      (node (ref "L4") (pin "1") (pinfunction "1_1") (pintype "passive"))
      (node (ref "U4") (pin "2") (pinfunction "SW_2") (pintype "power_in"))
    )
    (net (code "139") (name "Net-(U4-VBST)") (class "Default")
      (node (ref "C28") (pin "1") (pinfunction "1_1") (pintype "passive"))
      (node (ref "U4") (pin "6") (pinfunction "VBST_6") (pintype "power_in"))
    )
    (net (code "140") (name "Net-(U4-VFB)") (class "Default")
      (node (ref "R57") (pin "1") (pinfunction "1_1") (pintype "passive"))
      (node (ref "R58") (pin "2") (pinfunction "2_2") (pintype "passive"))
      (node (ref "U4") (pin "4") (pinfunction "VFB_4") (pintype "input"))
    )
    (net (code "141") (name "Net-(U5-5GOOD)") (class "Default")
      (node (ref "R14") (pin "2") (pinfunction "2_2") (pintype "passive"))
      (node (ref "U5") (pin "17") (pinfunction "5GOOD_17") (pintype "output"))
    )
    (net (code "142") (name "Net-(U5-12GOOD)") (class "Default")
      (node (ref "R17") (pin "2") (pinfunction "2_2") (pintype "passive"))
      (node (ref "U5") (pin "16") (pinfunction "12GOOD_16") (pintype "output"))
    )
    (net (code "143") (name "Net-(U5-BOOST1)") (class "Default")
      (node (ref "C51") (pin "1") (pinfunction "1_1") (pintype "passive"))
      (node (ref "D4") (pin "C") (pinfunction "C_C") (pintype "passive"))
      (node (ref "U5") (pin "5") (pinfunction "BOOST1_5") (pintype "input"))
    )
    (net (code "144") (name "Net-(U5-BOOST2)") (class "Default")
      (node (ref "C46") (pin "1") (pinfunction "1_1") (pintype "passive"))
      (node (ref "D1") (pin "C") (pinfunction "C_C") (pintype "passive"))
      (node (ref "U5") (pin "24") (pinfunction "BOOST2_24") (pintype "input"))
    )
    (net (code "145") (name "Net-(U5-FB1)") (class "Default")
      (node (ref "R69") (pin "2") (pinfunction "2_2") (pintype "passive"))
      (node (ref "R70") (pin "1") (pinfunction "1_1") (pintype "passive"))
      (node (ref "U5") (pin "8") (pinfunction "FB1_8") (pintype "input"))
    )
    (net (code "146") (name "Net-(U5-FB2)") (class "Default")
      (node (ref "R65") (pin "2") (pinfunction "2_2") (pintype "passive"))
      (node (ref "R66") (pin "1") (pinfunction "1_1") (pintype "passive"))
      (node (ref "U5") (pin "11") (pinfunction "FB2_11") (pintype "input"))
    )
    (net (code "147") (name "Net-(U5-FB3)") (class "Default")
      (node (ref "R67") (pin "2") (pinfunction "2_2") (pintype "passive"))
      (node (ref "R68") (pin "1") (pinfunction "1_1") (pintype "passive"))
      (node (ref "U5") (pin "19") (pinfunction "NFB_19") (pintype "input"))
      (node (ref "U5") (pin "20") (pinfunction "FB3_20") (pintype "input"))
    )
    (net (code "148") (name "Net-(U5-PGOOD1)") (class "Default")
      (node (ref "R15") (pin "2") (pinfunction "2_2") (pintype "passive"))
      (node (ref "U5") (pin "6") (pinfunction "PGOOD1_6") (pintype "output"))
    )
    (net (code "149") (name "Net-(U5-PGOOD2)") (class "Default")
      (node (ref "R59") (pin "2") (pinfunction "2_2") (pintype "passive"))
      (node (ref "U5") (pin "9") (pinfunction "PGOOD2_9") (pintype "output"))
    )
    (net (code "150") (name "Net-(U5-PGOOD3)") (class "Default")
      (node (ref "R18") (pin "2") (pinfunction "2_2") (pintype "passive"))
      (node (ref "U5") (pin "21") (pinfunction "PGOOD3_21") (pintype "output"))
    )
    (net (code "151") (name "Net-(U5-RUN{slash}SS1)") (class "Default")
      (node (ref "C41") (pin "1") (pinfunction "1_1") (pintype "passive"))
      (node (ref "U5") (pin "12") (pinfunction "RUN/SS1_12") (pintype "input"))
    )
    (net (code "152") (name "Net-(U5-RUN{slash}SS2)") (class "Default")
      (node (ref "C43") (pin "1") (pinfunction "1_1") (pintype "passive"))
      (node (ref "U5") (pin "13") (pinfunction "RUN/SS2_13") (pintype "input"))
    )
    (net (code "153") (name "Net-(U5-RUN{slash}SS3)") (class "Default")
      (node (ref "C42") (pin "1") (pinfunction "1_1") (pintype "passive"))
      (node (ref "U5") (pin "14") (pinfunction "RUN/SS3_14") (pintype "input"))
    )
    (net (code "154") (name "Net-(U5-SW1)") (class "Default")
      (node (ref "C51") (pin "2") (pinfunction "2_2") (pintype "passive"))
      (node (ref "D5") (pin "C") (pinfunction "C_C") (pintype "passive"))
      (node (ref "L7") (pin "2") (pinfunction "2_2") (pintype "passive"))
      (node (ref "U5") (pin "3") (pinfunction "SW1_2_3") (pintype "output"))
      (node (ref "U5") (pin "4") (pinfunction "SW1_4") (pintype "output"))
    )
    (net (code "155") (name "Net-(U5-SW2)") (class "Default")
      (node (ref "C46") (pin "2") (pinfunction "2_2") (pintype "passive"))
      (node (ref "D2") (pin "C") (pinfunction "C_C") (pintype "passive"))
      (node (ref "L5") (pin "2") (pinfunction "2_2") (pintype "passive"))
      (node (ref "U5") (pin "23") (pinfunction "SW2_23") (pintype "output"))
    )
    (net (code "156") (name "Net-(U5-SW3)") (class "Default")
      (node (ref "D3") (pin "A") (pinfunction "A_A") (pintype "passive"))
      (node (ref "L6") (pin "1") (pinfunction "1_1") (pintype "passive"))
      (node (ref "U5") (pin "27") (pinfunction "SW3_27") (pintype "output"))
    )
    (net (code "157") (name "Net-(U5-VC1)") (class "Default")
      (node (ref "C40") (pin "2") (pinfunction "2_2") (pintype "passive"))
      (node (ref "U5") (pin "7") (pinfunction "VC1_7") (pintype "output"))
    )
    (net (code "158") (name "Net-(U5-VC2)") (class "Default")
      (node (ref "C44") (pin "2") (pinfunction "2_2") (pintype "passive"))
      (node (ref "U5") (pin "10") (pinfunction "VC2_10") (pintype "output"))
    )
    (net (code "159") (name "Net-(U5-VC3)") (class "Default")
      (node (ref "C45") (pin "2") (pinfunction "2_2") (pintype "passive"))
      (node (ref "U5") (pin "18") (pinfunction "VC3_18") (pintype "output"))
    )
    (net (code "160") (name "Net-(U6-COMP)") (class "Default")
      (node (ref "C2") (pin "1") (pinfunction "1_1") (pintype "passive"))
      (node (ref "C3") (pin "1") (pinfunction "1_1") (pintype "passive"))
      (node (ref "U6") (pin "2") (pinfunction "COMP_2") (pintype "passive"))
    )
    (net (code "161") (name "Net-(U6-FA{slash}SYNC{slash}SD)") (class "Default")
      (node (ref "R2") (pin "2") (pinfunction "2_2") (pintype "passive"))
      (node (ref "U6") (pin "7") (pinfunction "FA/SYNC/SD_7") (pintype "passive"))
    )
    (net (code "162") (name "Net-(U6-FB)") (class "Default")
      (node (ref "R5") (pin "2") (pinfunction "2_2") (pintype "passive"))
      (node (ref "R6") (pin "2") (pinfunction "2_2") (pintype "passive"))
      (node (ref "U6") (pin "3") (pinfunction "FB_3") (pintype "passive"))
    )
    (net (code "163") (name "Net-(U6-ISEN)") (class "Default")
      (node (ref "R3") (pin "2") (pinfunction "2_2") (pintype "passive"))
      (node (ref "U6") (pin "1") (pinfunction "ISEN_1") (pintype "passive"))
    )
    (net (code "164") (name "OSC1") (class "Default")
      (node (ref "C70") (pin "2") (pinfunction "2_2") (pintype "passive"))
      (node (ref "IC9") (pin "46") (pinfunction "OSC1/CLKIN/RA7_46") (pintype "bidirectional"))
      (node (ref "Q3") (pin "1") (pinfunction "1_1") (pintype "passive"))
    )
    (net (code "165") (name "OSC2") (class "Default")
      (node (ref "C71") (pin "2") (pinfunction "2_2") (pintype "passive"))
      (node (ref "IC9") (pin "47") (pinfunction "OSC2/CLKOUT/RA6_47") (pintype "bidirectional"))
      (node (ref "Q3") (pin "2") (pinfunction "2_2") (pintype "passive"))
    )
    (net (code "166") (name "PGC") (class "Default")
      (node (ref "IC9") (pin "22") (pinfunction "RB6/PGC/KBI2_22") (pintype "bidirectional"))
      (node (ref "ICSP") (pin "5") (pinfunction "PGC_5") (pintype "passive"))
    )
    (net (code "167") (name "PGD") (class "Default")
      (node (ref "IC9") (pin "23") (pinfunction "RB7/PGD/T3G/KBI3_23") (pintype "bidirectional"))
      (node (ref "ICSP") (pin "4") (pinfunction "PGD_4") (pintype "passive"))
    )
    (net (code "168") (name "RX") (class "Default")
      (node (ref "IC9") (pin "6") (pinfunction "RG0/RX1/DT1_6") (pintype "bidirectional"))
      (node (ref "SERIAL") (pin "3") (pinfunction "3_3") (pintype "bidirectional"))
    )
    (net (code "169") (name "SENSOR_+X") (class "Default")
      (node (ref "+X") (pin "4") (pinfunction "4_4") (pintype "passive"))
      (node (ref "IC17") (pin "13") (pinfunction "X0_13") (pintype "bidirectional"))
    )
    (net (code "170") (name "SENSOR_+Y") (class "Default")
      (node (ref "+Y") (pin "4") (pinfunction "4_4") (pintype "passive"))
      (node (ref "IC17") (pin "15") (pinfunction "X2_15") (pintype "bidirectional"))
    )
    (net (code "171") (name "SENSOR_-X") (class "Default")
      (node (ref "-X") (pin "4") (pinfunction "4_4") (pintype "passive"))
      (node (ref "IC17") (pin "14") (pinfunction "X1_14") (pintype "bidirectional"))
    )
    (net (code "172") (name "SENSOR_-Y") (class "Default")
      (node (ref "-Y") (pin "4") (pinfunction "4_4") (pintype "passive"))
      (node (ref "IC17") (pin "12") (pinfunction "X3_12") (pintype "bidirectional"))
    )
    (net (code "173") (name "TX") (class "Default")
      (node (ref "IC9") (pin "12") (pinfunction "RG3/TX1/CK1_12") (pintype "bidirectional"))
      (node (ref "SERIAL") (pin "2") (pinfunction "2_2") (pintype "bidirectional"))
    )
    (net (code "174") (name "VBAT") (class "Default")
      (node (ref "BACKUP") (pin "13") (pinfunction "13_13") (pintype "passive"))
      (node (ref "BACKUP") (pin "14") (pinfunction "14_14") (pintype "passive"))
      (node (ref "BACKUP") (pin "15") (pinfunction "15_15") (pintype "passive"))
      (node (ref "BACKUP") (pin "16") (pinfunction "16_16") (pintype "passive"))
      (node (ref "BACKUP1") (pin "13") (pinfunction "13_13") (pintype "passive"))
      (node (ref "BACKUP1") (pin "14") (pinfunction "14_14") (pintype "passive"))
      (node (ref "BACKUP1") (pin "15") (pinfunction "15_15") (pintype "passive"))
      (node (ref "BACKUP1") (pin "16") (pinfunction "16_16") (pintype "passive"))
      (node (ref "BAT") (pin "1") (pinfunction "1_1") (pintype "passive"))
      (node (ref "C1") (pin "1") (pinfunction "1_1") (pintype "passive"))
      (node (ref "C11") (pin "+") (pinfunction "+_+") (pintype "passive"))
      (node (ref "C24") (pin "2") (pinfunction "2_2") (pintype "passive"))
      (node (ref "C29") (pin "+") (pinfunction "+_+") (pintype "passive"))
      (node (ref "C5") (pin "+") (pinfunction "+_+") (pintype "passive"))
      (node (ref "C54") (pin "+") (pinfunction "+_+") (pintype "passive"))
      (node (ref "C55") (pin "1") (pinfunction "1_1") (pintype "passive"))
      (node (ref "C60") (pin "2") (pinfunction "2_2") (pintype "passive"))
      (node (ref "C62") (pin "2") (pinfunction "2_2") (pintype "passive"))
      (node (ref "C63") (pin "2") (pinfunction "2_2") (pintype "passive"))
      (node (ref "C66") (pin "1") (pinfunction "1_1") (pintype "passive"))
      (node (ref "C9") (pin "+") (pinfunction "+_+") (pintype "passive"))
      (node (ref "D4") (pin "A") (pinfunction "A_A") (pintype "passive"))
      (node (ref "L1") (pin "1") (pinfunction "1_1") (pintype "passive"))
      (node (ref "L6") (pin "2") (pinfunction "2_2") (pintype "passive"))
      (node (ref "Q2") (pin "2") (pinfunction "S_2") (pintype "passive"))
      (node (ref "R14") (pin "1") (pinfunction "1_1") (pintype "passive"))
      (node (ref "R15") (pin "1") (pinfunction "1_1") (pintype "passive"))
      (node (ref "R17") (pin "1") (pinfunction "1_1") (pintype "passive"))
      (node (ref "R18") (pin "1") (pinfunction "1_1") (pintype "passive"))
      (node (ref "R59") (pin "1") (pinfunction "1_1") (pintype "passive"))
      (node (ref "SJ3") (pin "2") (pinfunction "2_2") (pintype "passive"))
      (node (ref "SJ4") (pin "2") (pinfunction "2_2") (pintype "passive"))
      (node (ref "SJ5") (pin "2") (pinfunction "2_2") (pintype "passive"))
      (node (ref "TP1") (pin "1") (pinfunction "P$1_1") (pintype "bidirectional"))
      (node (ref "TP10") (pin "1") (pinfunction "P$1_1") (pintype "bidirectional"))
      (node (ref "TP6") (pin "1") (pinfunction "P$1_1") (pintype "bidirectional"))
      (node (ref "TP8") (pin "1") (pinfunction "P$1_1") (pintype "bidirectional"))
      (node (ref "U1") (pin "3") (pinfunction "VIN_3") (pintype "power_in"))
      (node (ref "U2") (pin "3") (pinfunction "VIN_3") (pintype "power_in"))
      (node (ref "U3") (pin "17") (pinfunction "VSENSE_17") (pintype "input"))
      (node (ref "U3") (pin "18") (pinfunction "OUT_2_18") (pintype "output"))
      (node (ref "U3") (pin "19") (pinfunction "OUT_19") (pintype "output"))
      (node (ref "U4") (pin "3") (pinfunction "VIN_3") (pintype "power_in"))
      (node (ref "U5") (pin "1") (pinfunction "VIN_3_1") (pintype "power_in"))
      (node (ref "U5") (pin "15") (pinfunction "BIAS1_15") (pintype "power_in"))
      (node (ref "U5") (pin "2") (pinfunction "VIN_2_2") (pintype "power_in"))
      (node (ref "U5") (pin "22") (pinfunction "VIN_4_22") (pintype "power_in"))
      (node (ref "U5") (pin "25") (pinfunction "VIN_25") (pintype "power_in"))
      (node (ref "U5") (pin "28") (pinfunction "BIAS2_28") (pintype "power_in"))
      (node (ref "U6") (pin "8") (pinfunction "VIN_8") (pintype "passive"))
    )
    (net (code "175") (name "VCC") (class "Default")
      (node (ref "+X") (pin "3") (pinfunction "3_3") (pintype "passive"))
      (node (ref "+Y") (pin "3") (pinfunction "3_3") (pintype "passive"))
      (node (ref "-X") (pin "3") (pinfunction "3_3") (pintype "passive"))
      (node (ref "-Y") (pin "3") (pinfunction "3_3") (pintype "passive"))
      (node (ref "BACKUP") (pin "25") (pinfunction "25_25") (pintype "passive"))
      (node (ref "BACKUP") (pin "26") (pinfunction "26_26") (pintype "passive"))
      (node (ref "BACKUP1") (pin "25") (pinfunction "25_25") (pintype "passive"))
      (node (ref "BACKUP1") (pin "26") (pinfunction "26_26") (pintype "passive"))
      (node (ref "C13") (pin "2") (pinfunction "2_2") (pintype "passive"))
      (node (ref "C15") (pin "2") (pinfunction "2_2") (pintype "passive"))
      (node (ref "C17") (pin "2") (pinfunction "2_2") (pintype "passive"))
      (node (ref "C19") (pin "2") (pinfunction "2_2") (pintype "passive"))
      (node (ref "C21") (pin "2") (pinfunction "2_2") (pintype "passive"))
      (node (ref "C27") (pin "2") (pinfunction "2_2") (pintype "passive"))
      (node (ref "C30") (pin "+") (pinfunction "+_+") (pintype "passive"))
      (node (ref "C31") (pin "1") (pinfunction "1_1") (pintype "passive"))
      (node (ref "C32") (pin "1") (pinfunction "1_1") (pintype "passive"))
      (node (ref "C33") (pin "2") (pinfunction "2_2") (pintype "passive"))
      (node (ref "C34") (pin "2") (pinfunction "2_2") (pintype "passive"))
      (node (ref "C35") (pin "2") (pinfunction "2_2") (pintype "passive"))
      (node (ref "C36") (pin "2") (pinfunction "2_2") (pintype "passive"))
      (node (ref "C37") (pin "2") (pinfunction "2_2") (pintype "passive"))
      (node (ref "C38") (pin "2") (pinfunction "2_2") (pintype "passive"))
      (node (ref "C39") (pin "1") (pinfunction "1_1") (pintype "passive"))
      (node (ref "C65") (pin "1") (pinfunction "1_1") (pintype "passive"))
      (node (ref "C67") (pin "1") (pinfunction "1_1") (pintype "passive"))
      (node (ref "C68") (pin "1") (pinfunction "1_1") (pintype "passive"))
      (node (ref "C69") (pin "1") (pinfunction "1_1") (pintype "passive"))
      (node (ref "C72") (pin "2") (pinfunction "2_2") (pintype "passive"))
      (node (ref "C74") (pin "2") (pinfunction "2_2") (pintype "passive"))
      (node (ref "C75") (pin "2") (pinfunction "2_2") (pintype "passive"))
      (node (ref "C77") (pin "2") (pinfunction "2_2") (pintype "passive"))
      (node (ref "C79") (pin "2") (pinfunction "2_2") (pintype "passive"))
      (node (ref "C81") (pin "2") (pinfunction "2_2") (pintype "passive"))
      (node (ref "D7") (pin "C") (pinfunction "C_C") (pintype "passive"))
      (node (ref "IC1") (pin "1") (pinfunction "VIN_1") (pintype "power_in"))
      (node (ref "IC10") (pin "1") (pinfunction "VCC_1") (pintype "bidirectional"))
      (node (ref "IC11") (pin "3") (pinfunction "VCC_3") (pintype "power_in"))
      (node (ref "IC12") (pin "1") (pinfunction "VIN_1") (pintype "power_in"))
      (node (ref "IC13") (pin "8") (pinfunction "V+_8") (pintype "power_in"))
      (node (ref "IC14") (pin "1") (pinfunction "VIN_1") (pintype "power_in"))
      (node (ref "IC15") (pin "1") (pinfunction "VIN_1") (pintype "power_in"))
      (node (ref "IC16") (pin "1") (pinfunction "VIN_1") (pintype "power_in"))
      (node (ref "IC17") (pin "16") (pinfunction "VCC_16") (pintype "power_in"))
      (node (ref "IC18") (pin "1") (pinfunction "VCC_1") (pintype "bidirectional"))
      (node (ref "IC2") (pin "1") (pinfunction "VIN_1") (pintype "power_in"))
      (node (ref "IC3") (pin "1") (pinfunction "VIN_1") (pintype "power_in"))
      (node (ref "IC4") (pin "1") (pinfunction "VIN_1") (pintype "power_in"))
      (node (ref "IC5") (pin "8") (pinfunction "V+_8") (pintype "power_in"))
      (node (ref "IC6") (pin "8") (pinfunction "V+_8") (pintype "power_in"))
      (node (ref "IC7") (pin "8") (pinfunction "V+_8") (pintype "power_in"))
      (node (ref "IC8") (pin "8") (pinfunction "V+_8") (pintype "power_in"))
      (node (ref "IC9") (pin "10") (pinfunction "VDD_10") (pintype "power_in"))
      (node (ref "IC9") (pin "25") (pinfunction "VDD_25") (pintype "power_in"))
      (node (ref "IC9") (pin "40") (pinfunction "AVDD_40") (pintype "power_in"))
      (node (ref "IC9") (pin "41") (pinfunction "VDD_41") (pintype "power_in"))
      (node (ref "IC9") (pin "57") (pinfunction "VDD_57") (pintype "power_in"))
      (node (ref "IC9") (pin "9") (pinfunction "AVDD_9") (pintype "power_in"))
      (node (ref "ICSP") (pin "2") (pinfunction "+V_2") (pintype "passive"))
      (node (ref "L4") (pin "2") (pinfunction "2_2") (pintype "passive"))
      (node (ref "R48") (pin "1") (pinfunction "1_1") (pintype "passive"))
      (node (ref "R49") (pin "1") (pinfunction "1_1") (pintype "passive"))
      (node (ref "R50") (pin "1") (pinfunction "1_1") (pintype "passive"))
      (node (ref "R51") (pin "2") (pinfunction "2_2") (pintype "passive"))
      (node (ref "R52") (pin "2") (pinfunction "2_2") (pintype "passive"))
      (node (ref "R53") (pin "1") (pinfunction "1_1") (pintype "passive"))
      (node (ref "R56") (pin "2") (pinfunction "2_2") (pintype "passive"))
      (node (ref "R57") (pin "2") (pinfunction "2_2") (pintype "passive"))
      (node (ref "R85") (pin "1") (pinfunction "1_1") (pintype "passive"))
      (node (ref "R86") (pin "1") (pinfunction "1_1") (pintype "passive"))
      (node (ref "SERIAL") (pin "1") (pinfunction "1_1") (pintype "bidirectional"))
      (node (ref "SJ1") (pin "3") (pinfunction "3_3") (pintype "passive"))
      (node (ref "SJ2") (pin "3") (pinfunction "3_3") (pintype "passive"))
      (node (ref "SJ6") (pin "3") (pinfunction "3_3") (pintype "passive"))
      (node (ref "TP9") (pin "1") (pinfunction "P$1_1") (pintype "bidirectional"))
      (node (ref "U3") (pin "4") (pinfunction "VCC_4") (pintype "power_in"))
      (node (ref "U3") (pin "8") (pinfunction "EN_8") (pintype "input"))
      (node (ref "X1") (pin "5") (pinfunction "5_5") (pintype "passive"))
    )
    (net (code "176") (name "VCEL") (class "Default")
      (node (ref "C22") (pin "+") (pinfunction "+_+") (pintype "passive"))
      (node (ref "C64") (pin "2") (pinfunction "2_2") (pintype "passive"))
      (node (ref "FOTOCELULA") (pin "1") (pinfunction "1_1") (pintype "passive"))
      (node (ref "R45") (pin "1") (pinfunction "1_1") (pintype "passive"))
      (node (ref "R55") (pin "2") (pinfunction "2_2") (pintype "passive"))
      (node (ref "R79") (pin "1") (pinfunction "1_1") (pintype "passive"))
      (node (ref "R82") (pin "2") (pinfunction "2_2") (pintype "passive"))
    )
    (net (code "177") (name "VNREG") (class "Default")
      (node (ref "R40") (pin "2") (pinfunction "2_2") (pintype "passive"))
      (node (ref "R42") (pin "1") (pinfunction "1_1") (pintype "passive"))
      (node (ref "R44") (pin "2") (pinfunction "2_2") (pintype "passive"))
      (node (ref "V_BUS") (pin "31") (pinfunction "31_31") (pintype "passive"))
      (node (ref "V_BUS") (pin "33") (pinfunction "33_33") (pintype "passive"))
      (node (ref "V_BUS") (pin "35") (pinfunction "35_35") (pintype "passive"))
      (node (ref "V_BUS") (pin "37") (pinfunction "37_37") (pintype "passive"))
      (node (ref "V_BUS") (pin "39") (pinfunction "39_39") (pintype "passive"))
    )
    (net (code "178") (name "VOUT_+3V3") (class "Default")
      (node (ref "C18") (pin "2") (pinfunction "2_2") (pintype "passive"))
      (node (ref "IC3") (pin "6") (pinfunction "SENSE_6") (pintype "passive"))
      (node (ref "R33") (pin "2") (pinfunction "2_2") (pintype "passive"))
      (node (ref "R38") (pin "1") (pinfunction "1_1") (pintype "passive"))
      (node (ref "T6") (pin "6") (pinfunction "D_6") (pintype "passive"))
      (node (ref "T6") (pin "7") (pinfunction "D_7") (pintype "passive"))
    )
    (net (code "179") (name "VOUT_+5V") (class "Default")
      (node (ref "C16") (pin "2") (pinfunction "2_2") (pintype "passive"))
      (node (ref "IC2") (pin "6") (pinfunction "SENSE_6") (pintype "passive"))
      (node (ref "R21") (pin "2") (pinfunction "2_2") (pintype "passive"))
      (node (ref "R32") (pin "1") (pinfunction "1_1") (pintype "passive"))
      (node (ref "T4") (pin "6") (pinfunction "D_6") (pintype "passive"))
      (node (ref "T4") (pin "7") (pinfunction "D_7") (pintype "passive"))
      (node (ref "TP4") (pin "1") (pinfunction "P$1_1") (pintype "bidirectional"))
    )
    (net (code "180") (name "VOUT_+12V") (class "Default")
      (node (ref "C14") (pin "2") (pinfunction "2_2") (pintype "passive"))
      (node (ref "IC1") (pin "6") (pinfunction "SENSE_6") (pintype "passive"))
      (node (ref "R22") (pin "2") (pinfunction "2_2") (pintype "passive"))
      (node (ref "R27") (pin "1") (pinfunction "1_1") (pintype "passive"))
      (node (ref "T2") (pin "6") (pinfunction "D_6") (pintype "passive"))
      (node (ref "T2") (pin "7") (pinfunction "D_7") (pintype "passive"))
    )
    (net (code "181") (name "VOUT_+NREGV") (class "Default")
      (node (ref "C20") (pin "2") (pinfunction "2_2") (pintype "passive"))
      (node (ref "Q2") (pin "3") (pinfunction "D_3") (pintype "passive"))
      (node (ref "R39") (pin "2") (pinfunction "2_2") (pintype "passive"))
      (node (ref "R44") (pin "1") (pinfunction "1_1") (pintype "passive"))
    )
    (net (code "182") (name "VOUT_3V3") (class "Default")
      (node (ref "C12") (pin "+") (pinfunction "+_+") (pintype "passive"))
      (node (ref "C61") (pin "2") (pinfunction "2_2") (pintype "passive"))
      (node (ref "L2") (pin "2") (pinfunction "2_2") (pintype "passive"))
      (node (ref "R9") (pin "2") (pinfunction "2_2") (pintype "passive"))
      (node (ref "T5") (pin "7") (pinfunction "D_7") (pintype "passive"))
      (node (ref "TP7") (pin "1") (pinfunction "P$1_1") (pintype "bidirectional"))
    )
    (net (code "183") (name "VOUT_5V") (class "Default")
      (node (ref "C10") (pin "+") (pinfunction "+_+") (pintype "passive"))
      (node (ref "C59") (pin "2") (pinfunction "2_2") (pintype "passive"))
      (node (ref "L3") (pin "2") (pinfunction "2_2") (pintype "passive"))
      (node (ref "R7") (pin "2") (pinfunction "2_2") (pintype "passive"))
      (node (ref "T3") (pin "7") (pinfunction "D_7") (pintype "passive"))
      (node (ref "TP2") (pin "1") (pinfunction "P$1_1") (pintype "bidirectional"))
    )
    (net (code "184") (name "VOUT_12V") (class "Default")
      (node (ref "C56") (pin "+") (pinfunction "+_+") (pintype "passive"))
      (node (ref "C57") (pin "+") (pinfunction "+_+") (pintype "passive"))
      (node (ref "C58") (pin "1") (pinfunction "1_1") (pintype "passive"))
      (node (ref "C7") (pin "+") (pinfunction "+_+") (pintype "passive"))
      (node (ref "D6") (pin "C") (pinfunction "C_C") (pintype "passive"))
      (node (ref "R6") (pin "1") (pinfunction "1_1") (pintype "passive"))
      (node (ref "T1") (pin "7") (pinfunction "D_7") (pintype "passive"))
      (node (ref "TP11") (pin "1") (pinfunction "P$1_1") (pintype "bidirectional"))
    )
    (net (code "185") (name "VOUT_BACKUP_3V3") (class "Default")
      (node (ref "BACKUP") (pin "10") (pinfunction "10_10") (pintype "passive"))
      (node (ref "BACKUP") (pin "11") (pinfunction "11_11") (pintype "passive"))
      (node (ref "BACKUP") (pin "12") (pinfunction "12_12") (pintype "passive"))
      (node (ref "BACKUP") (pin "9") (pinfunction "9_9") (pintype "passive"))
      (node (ref "BACKUP1") (pin "10") (pinfunction "10_10") (pintype "passive"))
      (node (ref "BACKUP1") (pin "11") (pinfunction "11_11") (pintype "passive"))
      (node (ref "BACKUP1") (pin "12") (pinfunction "12_12") (pintype "passive"))
      (node (ref "BACKUP1") (pin "9") (pinfunction "9_9") (pintype "passive"))
      (node (ref "C47") (pin "+") (pinfunction "+_+") (pintype "passive"))
      (node (ref "C50") (pin "1") (pinfunction "1_1") (pintype "passive"))
      (node (ref "D1") (pin "A") (pinfunction "A_A") (pintype "passive"))
      (node (ref "L5") (pin "1") (pinfunction "1_1") (pintype "passive"))
      (node (ref "R65") (pin "1") (pinfunction "1_1") (pintype "passive"))
      (node (ref "T5") (pin "6") (pinfunction "D_6") (pintype "passive"))
    )
    (net (code "186") (name "VOUT_BACKUP_5V") (class "Default")
      (node (ref "BACKUP") (pin "5") (pinfunction "5_5") (pintype "passive"))
      (node (ref "BACKUP") (pin "6") (pinfunction "6_6") (pintype "passive"))
      (node (ref "BACKUP") (pin "7") (pinfunction "7_7") (pintype "passive"))
      (node (ref "BACKUP") (pin "8") (pinfunction "8_8") (pintype "passive"))
      (node (ref "BACKUP1") (pin "5") (pinfunction "5_5") (pintype "passive"))
      (node (ref "BACKUP1") (pin "6") (pinfunction "6_6") (pintype "passive"))
      (node (ref "BACKUP1") (pin "7") (pinfunction "7_7") (pintype "passive"))
      (node (ref "BACKUP1") (pin "8") (pinfunction "8_8") (pintype "passive"))
      (node (ref "C52") (pin "+") (pinfunction "+_+") (pintype "passive"))
      (node (ref "C53") (pin "1") (pinfunction "1_1") (pintype "passive"))
      (node (ref "L7") (pin "1") (pinfunction "1_1") (pintype "passive"))
      (node (ref "R69") (pin "1") (pinfunction "1_1") (pintype "passive"))
      (node (ref "T3") (pin "6") (pinfunction "D_6") (pintype "passive"))
      (node (ref "TP3") (pin "1") (pinfunction "P$1_1") (pintype "bidirectional"))
    )
    (net (code "187") (name "VOUT_BACKUP_12V") (class "Default")
      (node (ref "BACKUP") (pin "1") (pinfunction "1_1") (pintype "passive"))
      (node (ref "BACKUP") (pin "2") (pinfunction "2_2") (pintype "passive"))
      (node (ref "BACKUP") (pin "3") (pinfunction "3_3") (pintype "passive"))
      (node (ref "BACKUP") (pin "4") (pinfunction "4_4") (pintype "passive"))
      (node (ref "BACKUP1") (pin "1") (pinfunction "1_1") (pintype "passive"))
      (node (ref "BACKUP1") (pin "2") (pinfunction "2_2") (pintype "passive"))
      (node (ref "BACKUP1") (pin "3") (pinfunction "3_3") (pintype "passive"))
      (node (ref "BACKUP1") (pin "4") (pinfunction "4_4") (pintype "passive"))
      (node (ref "C48") (pin "+") (pinfunction "+_+") (pintype "passive"))
      (node (ref "C49") (pin "1") (pinfunction "1_1") (pintype "passive"))
      (node (ref "D3") (pin "C") (pinfunction "C_C") (pintype "passive"))
      (node (ref "R67") (pin "1") (pinfunction "1_1") (pintype "passive"))
      (node (ref "T1") (pin "6") (pinfunction "D_6") (pintype "passive"))
    )
    (net (code "188") (name "VSOLAR") (class "Default")
      (node (ref "D10") (pin "C") (pinfunction "C_C") (pintype "passive"))
      (node (ref "D11") (pin "C") (pinfunction "C_C") (pintype "passive"))
      (node (ref "D12") (pin "C") (pinfunction "C_C") (pintype "passive"))
      (node (ref "D13") (pin "C") (pinfunction "C_C") (pintype "passive"))
      (node (ref "D8") (pin "C") (pinfunction "C_C") (pintype "passive"))
      (node (ref "D9") (pin "C") (pinfunction "C_C") (pintype "passive"))
      (node (ref "X1") (pin "1") (pinfunction "1_1") (pintype "passive"))
      (node (ref "X1") (pin "2") (pinfunction "2_2") (pintype "passive"))
    )
    (net (code "189") (name "unconnected-(BACKUP1-Pad31)") (class "Default")
      (node (ref "BACKUP1") (pin "31") (pinfunction "31_31") (pintype "passive"))
    )
    (net (code "190") (name "unconnected-(CAN-Pad1)") (class "Default")
      (node (ref "CAN") (pin "1") (pinfunction "1_1") (pintype "bidirectional"))
    )
    (net (code "191") (name "unconnected-(IC4-STAT-Pad4)") (class "Default")
      (node (ref "IC4") (pin "4") (pinfunction "STAT_4") (pintype "passive"))
    )
    (net (code "192") (name "unconnected-(IC9-RB5{slash}T0CKI{slash}T3CKI{slash}CCP5{slash}KBI1-Pad21)") (class "Default")
      (node (ref "IC9") (pin "21") (pinfunction "RB5/T0CKI/T3CKI/CCP5/KBI1_21") (pintype "bidirectional"))
    )
    (net (code "193") (name "unconnected-(IC9-RC0{slash}SOSCO{slash}SCLKI-Pad48)") (class "Default")
      (node (ref "IC9") (pin "48") (pinfunction "RC0/SOSCO/SCLKI_48") (pintype "bidirectional"))
    )
    (net (code "194") (name "unconnected-(IC9-RC4{slash}SDA{slash}SDI-Pad62)") (class "Default")
      (node (ref "IC9") (pin "62") (pinfunction "RC4/SDA/SDI_62") (pintype "bidirectional"))
    )
    (net (code "195") (name "unconnected-(IC9-RC5{slash}SDO-Pad63)") (class "Default")
      (node (ref "IC9") (pin "63") (pinfunction "RC5/SDO_63") (pintype "bidirectional"))
    )
    (net (code "196") (name "unconnected-(IC9-RC6{slash}CCP3-Pad64)") (class "Default")
      (node (ref "IC9") (pin "64") (pinfunction "RC6/CCP3_64") (pintype "bidirectional"))
    )
    (net (code "197") (name "unconnected-(IC9-RD3{slash}C2INB{slash}CTMUI{slash}PSP3-Pad59)") (class "Default")
      (node (ref "IC9") (pin "59") (pinfunction "RD3/C2INB/CTMUI/PSP3_59") (pintype "bidirectional"))
    )
    (net (code "198") (name "unconnected-(IC9-RD5{slash}P1B{slash}PSP5-Pad3)") (class "Default")
      (node (ref "IC9") (pin "3") (pinfunction "RD5/P1B/PSP5_3") (pintype "bidirectional"))
    )
    (net (code "199") (name "unconnected-(IC9-RD6{slash}P1C{slash}PSP6-Pad4)") (class "Default")
      (node (ref "IC9") (pin "4") (pinfunction "RD6/P1C/PSP6_4") (pintype "bidirectional"))
    )
    (net (code "200") (name "unconnected-(IC9-RD7{slash}P1D{slash}PSP7-Pad5)") (class "Default")
      (node (ref "IC9") (pin "5") (pinfunction "RD7/P1D/PSP7_5") (pintype "bidirectional"))
    )
    (net (code "201") (name "unconnected-(IC9-RE4{slash}CANRX-Pad27)") (class "Default")
      (node (ref "IC9") (pin "27") (pinfunction "RE4/CANRX_27") (pintype "bidirectional"))
    )
    (net (code "202") (name "unconnected-(IC9-RE5{slash}CANTX-Pad24)") (class "Default")
      (node (ref "IC9") (pin "24") (pinfunction "RE5/CANTX_24") (pintype "bidirectional"))
    )
    (net (code "203") (name "unconnected-(IC9-RE6{slash}RX2{slash}DT2-Pad60)") (class "Default")
      (node (ref "IC9") (pin "60") (pinfunction "RE6/RX2/DT2_60") (pintype "bidirectional"))
    )
    (net (code "204") (name "unconnected-(IC9-RE7{slash}TX2{slash}CK2-Pad61)") (class "Default")
      (node (ref "IC9") (pin "61") (pinfunction "RE7/TX2/CK2_61") (pintype "bidirectional"))
    )
    (net (code "205") (name "unconnected-(IC9-RF2{slash}MDCIN1-Pad35)") (class "Default")
      (node (ref "IC9") (pin "35") (pinfunction "RF2/MDCIN1_35") (pintype "bidirectional"))
    )
    (net (code "206") (name "unconnected-(IC9-RF3-Pad36)") (class "Default")
      (node (ref "IC9") (pin "36") (pinfunction "RF3_36") (pintype "bidirectional"))
    )
    (net (code "207") (name "unconnected-(IC9-RF4{slash}MDCIN2-Pad44)") (class "Default")
      (node (ref "IC9") (pin "44") (pinfunction "RF4/MDCIN2_44") (pintype "bidirectional"))
    )
    (net (code "208") (name "unconnected-(IC9-RF5-Pad45)") (class "Default")
      (node (ref "IC9") (pin "45") (pinfunction "RF5_45") (pintype "bidirectional"))
    )
    (net (code "209") (name "unconnected-(IC9-RF6{slash}MDOUT-Pad52)") (class "Default")
      (node (ref "IC9") (pin "52") (pinfunction "RF6/MDOUT_52") (pintype "bidirectional"))
    )
    (net (code "210") (name "unconnected-(IC9-RF7-Pad53)") (class "Default")
      (node (ref "IC9") (pin "53") (pinfunction "RF7_53") (pintype "bidirectional"))
    )
    (net (code "211") (name "unconnected-(IC9-RG1{slash}CANTX2-Pad7)") (class "Default")
      (node (ref "IC9") (pin "7") (pinfunction "RG1/CANTX2_7") (pintype "bidirectional"))
    )
    (net (code "212") (name "unconnected-(IC9-RG2{slash}T3CKI-Pad11)") (class "Default")
      (node (ref "IC9") (pin "11") (pinfunction "RG2/T3CKI_11") (pintype "bidirectional"))
    )
    (net (code "213") (name "unconnected-(IC11-VREF-Pad5)") (class "Default")
      (node (ref "IC11") (pin "5") (pinfunction "VREF_5") (pintype "input"))
    )
    (net (code "214") (name "unconnected-(IC12-STAT-Pad4)") (class "Default")
      (node (ref "IC12") (pin "4") (pinfunction "STAT_4") (pintype "passive"))
    )
    (net (code "215") (name "unconnected-(IC14-STAT-Pad4)") (class "Default")
      (node (ref "IC14") (pin "4") (pinfunction "STAT_4") (pintype "passive"))
    )
    (net (code "216") (name "unconnected-(IC15-STAT-Pad4)") (class "Default")
      (node (ref "IC15") (pin "4") (pinfunction "STAT_4") (pintype "passive"))
    )
    (net (code "217") (name "unconnected-(IC16-STAT-Pad4)") (class "Default")
      (node (ref "IC16") (pin "4") (pinfunction "STAT_4") (pintype "passive"))
    )
    (net (code "218") (name "unconnected-(Q4-D-Pad3)") (class "Default")
      (node (ref "Q4") (pin "3") (pinfunction "D_3") (pintype "passive"))
    )
    (net (code "219") (name "unconnected-(Q4-S-Pad2)") (class "Default")
      (node (ref "Q4") (pin "2") (pinfunction "S_2") (pintype "passive"))
    )
    (net (code "220") (name "unconnected-(Q5-D-Pad3)") (class "Default")
      (node (ref "Q5") (pin "3") (pinfunction "D_3") (pintype "passive"))
    )
    (net (code "221") (name "unconnected-(Q5-S-Pad2)") (class "Default")
      (node (ref "Q5") (pin "2") (pinfunction "S_2") (pintype "passive"))
    )
    (net (code "222") (name "unconnected-(Q6-S-Pad2)") (class "Default")
      (node (ref "Q6") (pin "2") (pinfunction "S_2") (pintype "passive"))
    )
    (net (code "223") (name "unconnected-(Q7-D-Pad3)") (class "Default")
      (node (ref "Q7") (pin "3") (pinfunction "D_3") (pintype "passive"))
    )
    (net (code "224") (name "unconnected-(Q7-S-Pad2)") (class "Default")
      (node (ref "Q7") (pin "2") (pinfunction "S_2") (pintype "passive"))
    )
    (net (code "225") (name "unconnected-(T1A-D2-Pad8)") (class "Default")
      (node (ref "T1") (pin "8") (pinfunction "D2_8") (pintype "passive"))
    )
    (net (code "226") (name "unconnected-(T1B-D2-Pad5)") (class "Default")
      (node (ref "T1") (pin "5") (pinfunction "D2_5") (pintype "passive"))
    )
    (net (code "227") (name "unconnected-(T2A-D2-Pad8)") (class "Default")
      (node (ref "T2") (pin "8") (pinfunction "D2_8") (pintype "passive"))
    )
    (net (code "228") (name "unconnected-(T2B-D2-Pad5)") (class "Default")
      (node (ref "T2") (pin "5") (pinfunction "D2_5") (pintype "passive"))
    )
    (net (code "229") (name "unconnected-(T3A-D2-Pad8)") (class "Default")
      (node (ref "T3") (pin "8") (pinfunction "D2_8") (pintype "passive"))
    )
    (net (code "230") (name "unconnected-(T3B-D2-Pad5)") (class "Default")
      (node (ref "T3") (pin "5") (pinfunction "D2_5") (pintype "passive"))
    )
    (net (code "231") (name "unconnected-(T4A-D2-Pad8)") (class "Default")
      (node (ref "T4") (pin "8") (pinfunction "D2_8") (pintype "passive"))
    )
    (net (code "232") (name "unconnected-(T4B-D2-Pad5)") (class "Default")
      (node (ref "T4") (pin "5") (pinfunction "D2_5") (pintype "passive"))
    )
    (net (code "233") (name "unconnected-(T5A-D2-Pad8)") (class "Default")
      (node (ref "T5") (pin "8") (pinfunction "D2_8") (pintype "passive"))
    )
    (net (code "234") (name "unconnected-(T5B-D2-Pad5)") (class "Default")
      (node (ref "T5") (pin "5") (pinfunction "D2_5") (pintype "passive"))
    )
    (net (code "235") (name "unconnected-(T6A-D2-Pad8)") (class "Default")
      (node (ref "T6") (pin "8") (pinfunction "D2_8") (pintype "passive"))
    )
    (net (code "236") (name "unconnected-(T6B-D2-Pad5)") (class "Default")
      (node (ref "T6") (pin "5") (pinfunction "D2_5") (pintype "passive"))
    )
    (net (code "237") (name "unconnected-(U3-NC-Pad20)") (class "Default")
      (node (ref "U3") (pin "20") (pinfunction "NC_20") (pintype "no_connect"))
    )
    (net (code "238") (name "unconnected-(U3-NC_2-Pad1)") (class "Default")
      (node (ref "U3") (pin "1") (pinfunction "NC_2_1") (pintype "no_connect"))
    )
    (net (code "239") (name "unconnected-(U3-NC_3-Pad6)") (class "Default")
      (node (ref "U3") (pin "6") (pinfunction "NC_3_6") (pintype "no_connect"))
    )
    (net (code "240") (name "unconnected-(U3-NC_4-Pad11)") (class "Default")
      (node (ref "U3") (pin "11") (pinfunction "NC_4_11") (pintype "no_connect"))
    )
    (net (code "241") (name "~{MCLR}") (class "Default")
      (node (ref "IC9") (pin "28") (pinfunction "~{MCLR/}RE3_28") (pintype "bidirectional"))
      (node (ref "ICSP") (pin "1") (pinfunction "/MCLR_1") (pintype "passive"))
      (node (ref "R47") (pin "2") (pinfunction "2_2") (pintype "passive"))
    )
  )
)
